# LED_DISPLAY_SCHE.net
KiCad netlist of a schematic drawn in Altium Designer
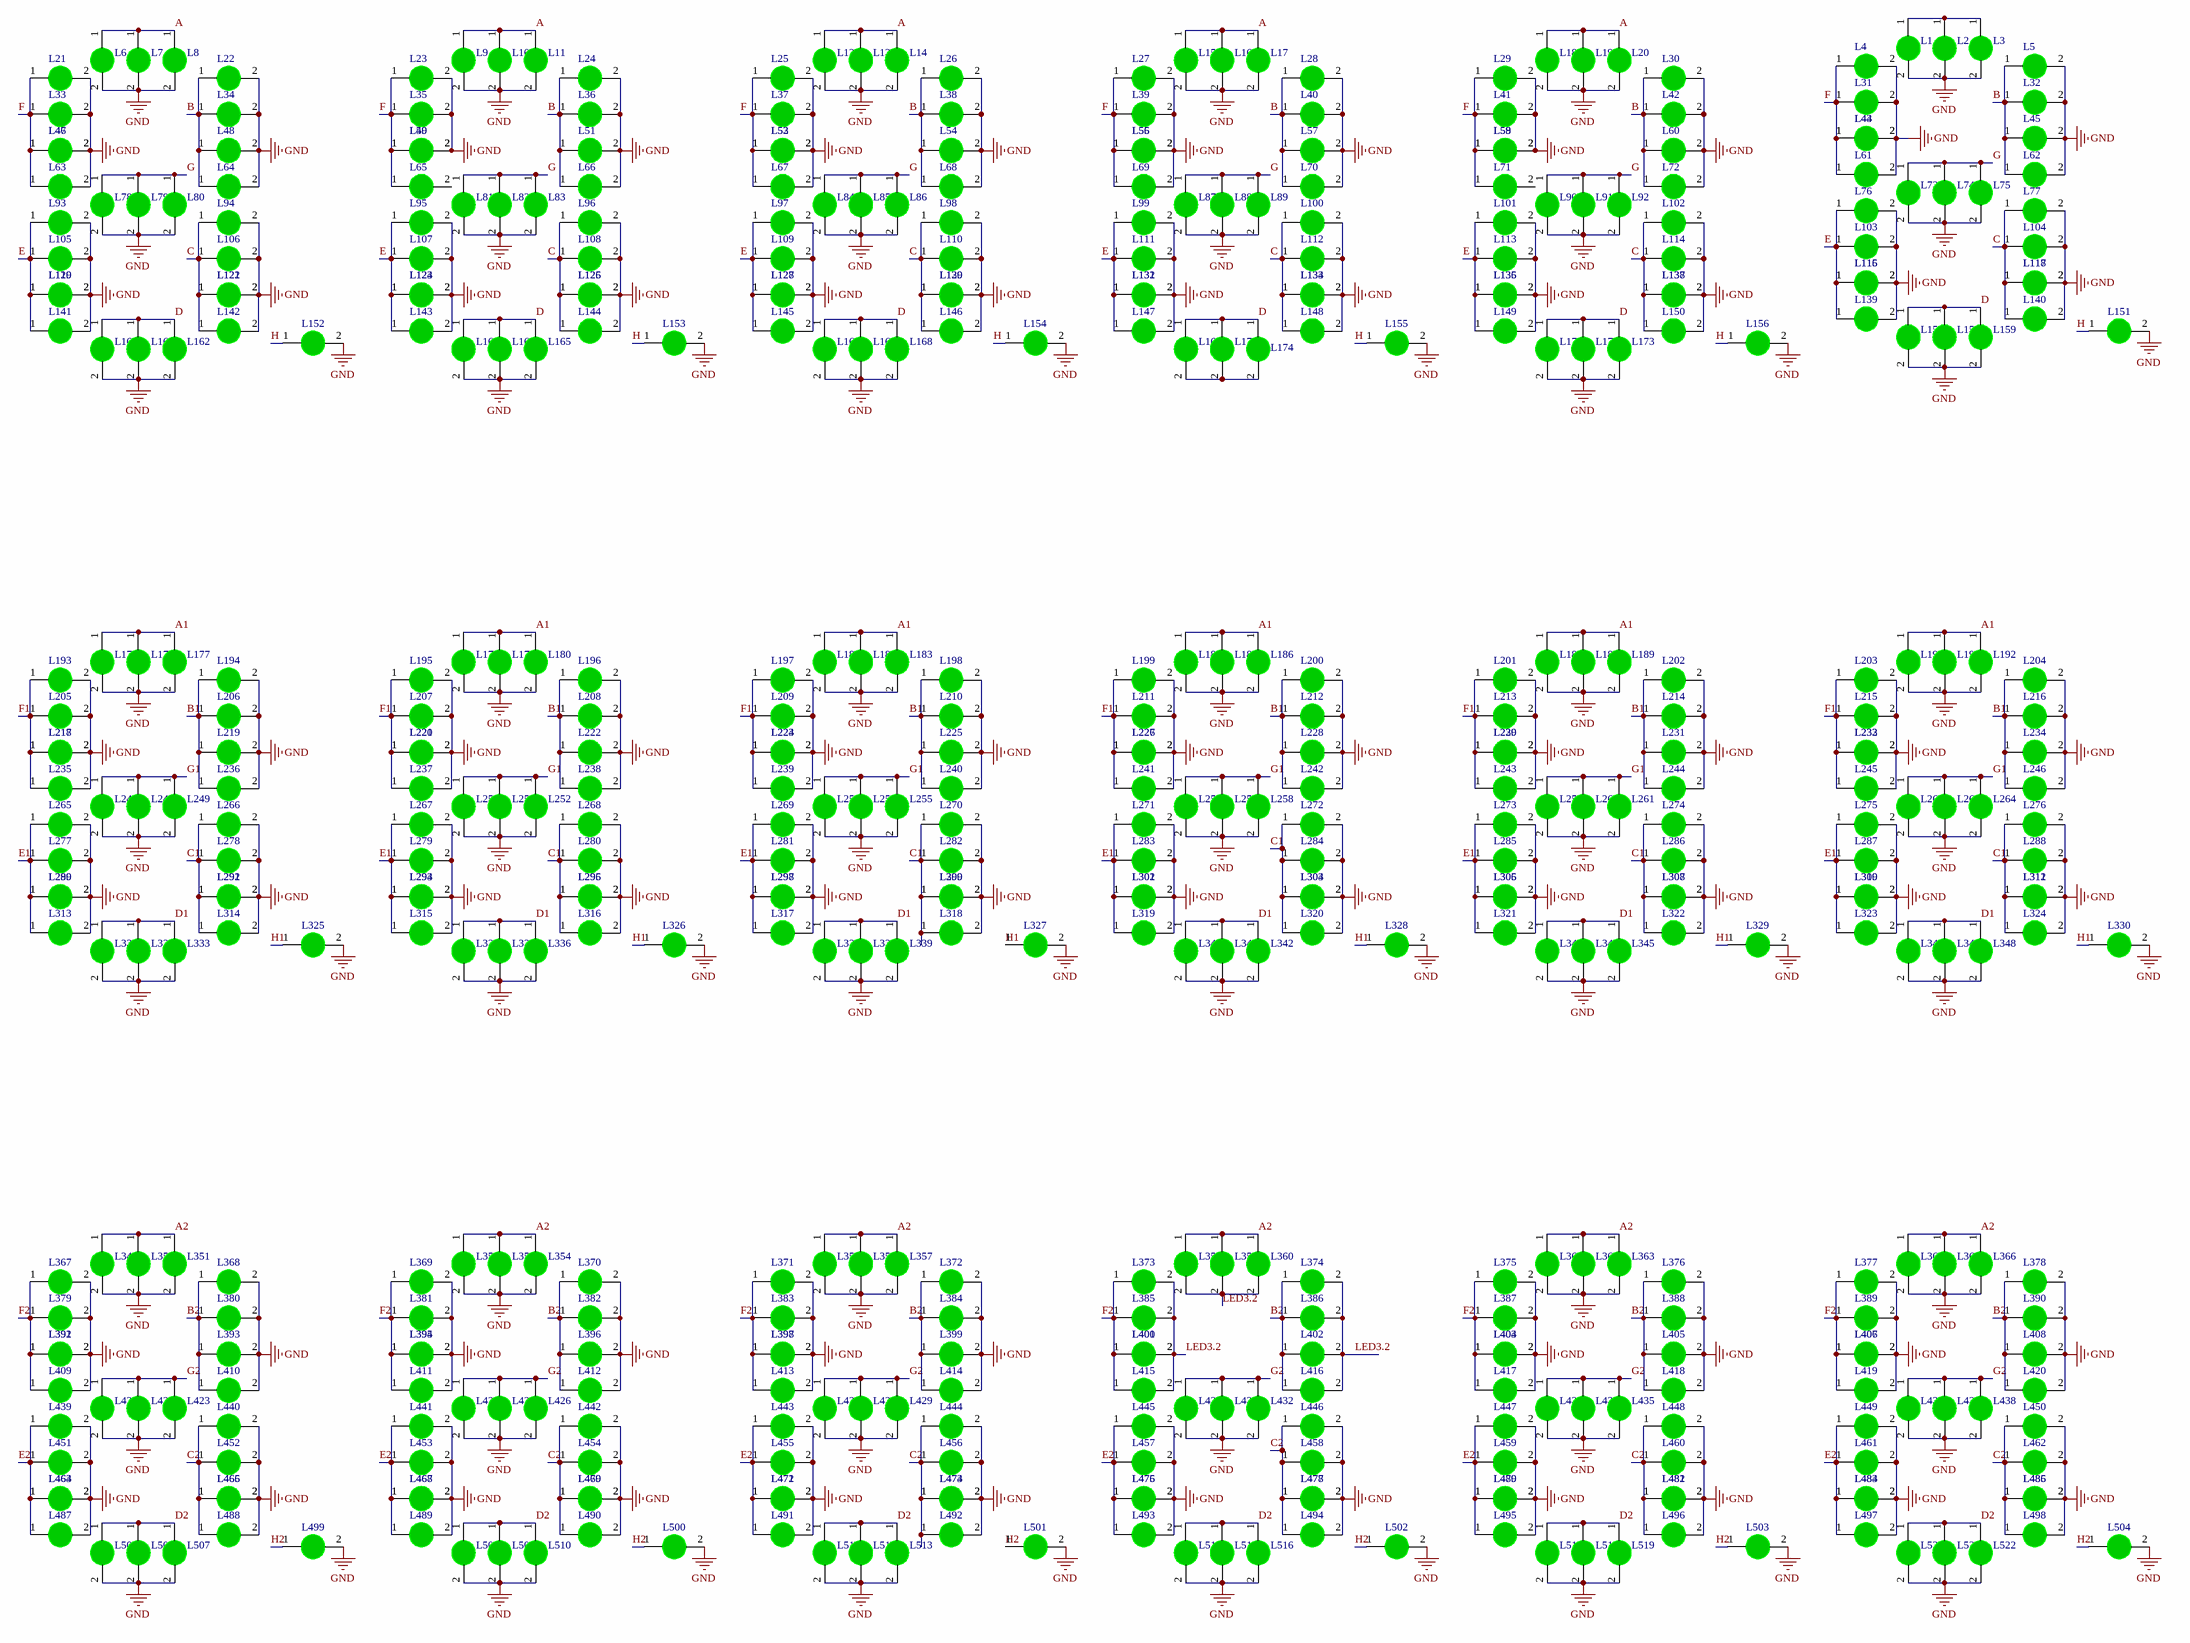
[diagram p0: LED_DISPLAY_SCHE.SchDoc]

(export (version "E")
  (design (tool "Eeschema 10.0.6"))
  (components
    (comp (ref "L1")
      (value "LED 3528")
      (footprint "LED-3528-GREEN")
      (description "Dán")
      (libsource (lib "Altium_Lib_by_KhueNguyenCreator") (part "LED 3528 Xanh La"))
    )
    (comp (ref "L2")
      (value "LED 3528")
      (footprint "LED-3528-GREEN")
      (description "Dán")
      (libsource (lib "Altium_Lib_by_KhueNguyenCreator") (part "LED 3528 Xanh La"))
    )
    (comp (ref "L3")
      (value "LED 3528")
      (footprint "LED-3528-GREEN")
      (description "Dán")
      (libsource (lib "Altium_Lib_by_KhueNguyenCreator") (part "LED 3528 Xanh La"))
    )
    (comp (ref "L4")
      (value "LED 3528")
      (footprint "LED-3528-GREEN")
      (description "Dán")
      (libsource (lib "Altium_Lib_by_KhueNguyenCreator") (part "LED 3528 Xanh La"))
    )
    (comp (ref "L5")
      (value "LED 3528")
      (footprint "LED-3528-GREEN")
      (description "Dán")
      (libsource (lib "Altium_Lib_by_KhueNguyenCreator") (part "LED 3528 Xanh La"))
    )
    (comp (ref "L6")
      (value "LED 3528")
      (footprint "LED-3528-GREEN")
      (description "Dán")
      (libsource (lib "Altium_Lib_by_KhueNguyenCreator") (part "LED 3528 Xanh La"))
    )
    (comp (ref "L7")
      (value "LED 3528")
      (footprint "LED-3528-GREEN")
      (description "Dán")
      (libsource (lib "Altium_Lib_by_KhueNguyenCreator") (part "LED 3528 Xanh La"))
    )
    (comp (ref "L8")
      (value "LED 3528")
      (footprint "LED-3528-GREEN")
      (description "Dán")
      (libsource (lib "Altium_Lib_by_KhueNguyenCreator") (part "LED 3528 Xanh La"))
    )
    (comp (ref "L9")
      (value "LED 3528")
      (footprint "LED-3528-GREEN")
      (description "Dán")
      (libsource (lib "Altium_Lib_by_KhueNguyenCreator") (part "LED 3528 Xanh La"))
    )
    (comp (ref "L10")
      (value "LED 3528")
      (footprint "LED-3528-GREEN")
      (description "Dán")
      (libsource (lib "Altium_Lib_by_KhueNguyenCreator") (part "LED 3528 Xanh La"))
    )
    (comp (ref "L11")
      (value "LED 3528")
      (footprint "LED-3528-GREEN")
      (description "Dán")
      (libsource (lib "Altium_Lib_by_KhueNguyenCreator") (part "LED 3528 Xanh La"))
    )
    (comp (ref "L12")
      (value "LED 3528")
      (footprint "LED-3528-GREEN")
      (description "Dán")
      (libsource (lib "Altium_Lib_by_KhueNguyenCreator") (part "LED 3528 Xanh La"))
    )
    (comp (ref "L13")
      (value "LED 3528")
      (footprint "LED-3528-GREEN")
      (description "Dán")
      (libsource (lib "Altium_Lib_by_KhueNguyenCreator") (part "LED 3528 Xanh La"))
    )
    (comp (ref "L14")
      (value "LED 3528")
      (footprint "LED-3528-GREEN")
      (description "Dán")
      (libsource (lib "Altium_Lib_by_KhueNguyenCreator") (part "LED 3528 Xanh La"))
    )
    (comp (ref "L15")
      (value "LED 3528")
      (footprint "LED-3528-GREEN")
      (description "Dán")
      (libsource (lib "Altium_Lib_by_KhueNguyenCreator") (part "LED 3528 Xanh La"))
    )
    (comp (ref "L16")
      (value "LED 3528")
      (footprint "LED-3528-GREEN")
      (description "Dán")
      (libsource (lib "Altium_Lib_by_KhueNguyenCreator") (part "LED 3528 Xanh La"))
    )
    (comp (ref "L17")
      (value "LED 3528")
      (footprint "LED-3528-GREEN")
      (description "Dán")
      (libsource (lib "Altium_Lib_by_KhueNguyenCreator") (part "LED 3528 Xanh La"))
    )
    (comp (ref "L18")
      (value "LED 3528")
      (footprint "LED-3528-GREEN")
      (description "Dán")
      (libsource (lib "Altium_Lib_by_KhueNguyenCreator") (part "LED 3528 Xanh La"))
    )
    (comp (ref "L19")
      (value "LED 3528")
      (footprint "LED-3528-GREEN")
      (description "Dán")
      (libsource (lib "Altium_Lib_by_KhueNguyenCreator") (part "LED 3528 Xanh La"))
    )
    (comp (ref "L20")
      (value "LED 3528")
      (footprint "LED-3528-GREEN")
      (description "Dán")
      (libsource (lib "Altium_Lib_by_KhueNguyenCreator") (part "LED 3528 Xanh La"))
    )
    (comp (ref "L21")
      (value "LED 3528")
      (footprint "LED-3528-GREEN")
      (description "Dán")
      (libsource (lib "Altium_Lib_by_KhueNguyenCreator") (part "LED 3528 Xanh La"))
    )
    (comp (ref "L22")
      (value "LED 3528")
      (footprint "LED-3528-GREEN")
      (description "Dán")
      (libsource (lib "Altium_Lib_by_KhueNguyenCreator") (part "LED 3528 Xanh La"))
    )
    (comp (ref "L23")
      (value "LED 3528")
      (footprint "LED-3528-GREEN")
      (description "Dán")
      (libsource (lib "Altium_Lib_by_KhueNguyenCreator") (part "LED 3528 Xanh La"))
    )
    (comp (ref "L24")
      (value "LED 3528")
      (footprint "LED-3528-GREEN")
      (description "Dán")
      (libsource (lib "Altium_Lib_by_KhueNguyenCreator") (part "LED 3528 Xanh La"))
    )
    (comp (ref "L25")
      (value "LED 3528")
      (footprint "LED-3528-GREEN")
      (description "Dán")
      (libsource (lib "Altium_Lib_by_KhueNguyenCreator") (part "LED 3528 Xanh La"))
    )
    (comp (ref "L26")
      (value "LED 3528")
      (footprint "LED-3528-GREEN")
      (description "Dán")
      (libsource (lib "Altium_Lib_by_KhueNguyenCreator") (part "LED 3528 Xanh La"))
    )
    (comp (ref "L27")
      (value "LED 3528")
      (footprint "LED-3528-GREEN")
      (description "Dán")
      (libsource (lib "Altium_Lib_by_KhueNguyenCreator") (part "LED 3528 Xanh La"))
    )
    (comp (ref "L28")
      (value "LED 3528")
      (footprint "LED-3528-GREEN")
      (description "Dán")
      (libsource (lib "Altium_Lib_by_KhueNguyenCreator") (part "LED 3528 Xanh La"))
    )
    (comp (ref "L29")
      (value "LED 3528")
      (footprint "LED-3528-GREEN")
      (description "Dán")
      (libsource (lib "Altium_Lib_by_KhueNguyenCreator") (part "LED 3528 Xanh La"))
    )
    (comp (ref "L30")
      (value "LED 3528")
      (footprint "LED-3528-GREEN")
      (description "Dán")
      (libsource (lib "Altium_Lib_by_KhueNguyenCreator") (part "LED 3528 Xanh La"))
    )
    (comp (ref "L31")
      (value "LED 3528")
      (footprint "LED-3528-GREEN")
      (description "Dán")
      (libsource (lib "Altium_Lib_by_KhueNguyenCreator") (part "LED 3528 Xanh La"))
    )
    (comp (ref "L32")
      (value "LED 3528")
      (footprint "LED-3528-GREEN")
      (description "Dán")
      (libsource (lib "Altium_Lib_by_KhueNguyenCreator") (part "LED 3528 Xanh La"))
    )
    (comp (ref "L33")
      (value "LED 3528")
      (footprint "LED-3528-GREEN")
      (description "Dán")
      (libsource (lib "Altium_Lib_by_KhueNguyenCreator") (part "LED 3528 Xanh La"))
    )
    (comp (ref "L34")
      (value "LED 3528")
      (footprint "LED-3528-GREEN")
      (description "Dán")
      (libsource (lib "Altium_Lib_by_KhueNguyenCreator") (part "LED 3528 Xanh La"))
    )
    (comp (ref "L35")
      (value "LED 3528")
      (footprint "LED-3528-GREEN")
      (description "Dán")
      (libsource (lib "Altium_Lib_by_KhueNguyenCreator") (part "LED 3528 Xanh La"))
    )
    (comp (ref "L36")
      (value "LED 3528")
      (footprint "LED-3528-GREEN")
      (description "Dán")
      (libsource (lib "Altium_Lib_by_KhueNguyenCreator") (part "LED 3528 Xanh La"))
    )
    (comp (ref "L37")
      (value "LED 3528")
      (footprint "LED-3528-GREEN")
      (description "Dán")
      (libsource (lib "Altium_Lib_by_KhueNguyenCreator") (part "LED 3528 Xanh La"))
    )
    (comp (ref "L38")
      (value "LED 3528")
      (footprint "LED-3528-GREEN")
      (description "Dán")
      (libsource (lib "Altium_Lib_by_KhueNguyenCreator") (part "LED 3528 Xanh La"))
    )
    (comp (ref "L39")
      (value "LED 3528")
      (footprint "LED-3528-GREEN")
      (description "Dán")
      (libsource (lib "Altium_Lib_by_KhueNguyenCreator") (part "LED 3528 Xanh La"))
    )
    (comp (ref "L40")
      (value "LED 3528")
      (footprint "LED-3528-GREEN")
      (description "Dán")
      (libsource (lib "Altium_Lib_by_KhueNguyenCreator") (part "LED 3528 Xanh La"))
    )
    (comp (ref "L41")
      (value "LED 3528")
      (footprint "LED-3528-GREEN")
      (description "Dán")
      (libsource (lib "Altium_Lib_by_KhueNguyenCreator") (part "LED 3528 Xanh La"))
    )
    (comp (ref "L42")
      (value "LED 3528")
      (footprint "LED-3528-GREEN")
      (description "Dán")
      (libsource (lib "Altium_Lib_by_KhueNguyenCreator") (part "LED 3528 Xanh La"))
    )
    (comp (ref "L43")
      (value "LED 3528")
      (footprint "LED-3528-GREEN")
      (description "Dán")
      (libsource (lib "Altium_Lib_by_KhueNguyenCreator") (part "LED 3528 Xanh La"))
    )
    (comp (ref "L44")
      (value "LED 3528")
      (footprint "LED-3528-GREEN")
      (description "Dán")
      (libsource (lib "Altium_Lib_by_KhueNguyenCreator") (part "LED 3528 Xanh La"))
    )
    (comp (ref "L45")
      (value "LED 3528")
      (footprint "LED-3528-GREEN")
      (description "Dán")
      (libsource (lib "Altium_Lib_by_KhueNguyenCreator") (part "LED 3528 Xanh La"))
    )
    (comp (ref "L46")
      (value "LED 3528")
      (footprint "LED-3528-GREEN")
      (description "Dán")
      (libsource (lib "Altium_Lib_by_KhueNguyenCreator") (part "LED 3528 Xanh La"))
    )
    (comp (ref "L47")
      (value "LED 3528")
      (footprint "LED-3528-GREEN")
      (description "Dán")
      (libsource (lib "Altium_Lib_by_KhueNguyenCreator") (part "LED 3528 Xanh La"))
    )
    (comp (ref "L48")
      (value "LED 3528")
      (footprint "LED-3528-GREEN")
      (description "Dán")
      (libsource (lib "Altium_Lib_by_KhueNguyenCreator") (part "LED 3528 Xanh La"))
    )
    (comp (ref "L49")
      (value "LED 3528")
      (footprint "LED-3528-GREEN")
      (description "Dán")
      (libsource (lib "Altium_Lib_by_KhueNguyenCreator") (part "LED 3528 Xanh La"))
    )
    (comp (ref "L50")
      (value "LED 3528")
      (footprint "LED-3528-GREEN")
      (description "Dán")
      (libsource (lib "Altium_Lib_by_KhueNguyenCreator") (part "LED 3528 Xanh La"))
    )
    (comp (ref "L51")
      (value "LED 3528")
      (footprint "LED-3528-GREEN")
      (description "Dán")
      (libsource (lib "Altium_Lib_by_KhueNguyenCreator") (part "LED 3528 Xanh La"))
    )
    (comp (ref "L52")
      (value "LED 3528")
      (footprint "LED-3528-GREEN")
      (description "Dán")
      (libsource (lib "Altium_Lib_by_KhueNguyenCreator") (part "LED 3528 Xanh La"))
    )
    (comp (ref "L53")
      (value "LED 3528")
      (footprint "LED-3528-GREEN")
      (description "Dán")
      (libsource (lib "Altium_Lib_by_KhueNguyenCreator") (part "LED 3528 Xanh La"))
    )
    (comp (ref "L54")
      (value "LED 3528")
      (footprint "LED-3528-GREEN")
      (description "Dán")
      (libsource (lib "Altium_Lib_by_KhueNguyenCreator") (part "LED 3528 Xanh La"))
    )
    (comp (ref "L55")
      (value "LED 3528")
      (footprint "LED-3528-GREEN")
      (description "Dán")
      (libsource (lib "Altium_Lib_by_KhueNguyenCreator") (part "LED 3528 Xanh La"))
    )
    (comp (ref "L56")
      (value "LED 3528")
      (footprint "LED-3528-GREEN")
      (description "Dán")
      (libsource (lib "Altium_Lib_by_KhueNguyenCreator") (part "LED 3528 Xanh La"))
    )
    (comp (ref "L57")
      (value "LED 3528")
      (footprint "LED-3528-GREEN")
      (description "Dán")
      (libsource (lib "Altium_Lib_by_KhueNguyenCreator") (part "LED 3528 Xanh La"))
    )
    (comp (ref "L58")
      (value "LED 3528")
      (footprint "LED-3528-GREEN")
      (description "Dán")
      (libsource (lib "Altium_Lib_by_KhueNguyenCreator") (part "LED 3528 Xanh La"))
    )
    (comp (ref "L59")
      (value "LED 3528")
      (footprint "LED-3528-GREEN")
      (description "Dán")
      (libsource (lib "Altium_Lib_by_KhueNguyenCreator") (part "LED 3528 Xanh La"))
    )
    (comp (ref "L60")
      (value "LED 3528")
      (footprint "LED-3528-GREEN")
      (description "Dán")
      (libsource (lib "Altium_Lib_by_KhueNguyenCreator") (part "LED 3528 Xanh La"))
    )
    (comp (ref "L61")
      (value "LED 3528")
      (footprint "LED-3528-GREEN")
      (description "Dán")
      (libsource (lib "Altium_Lib_by_KhueNguyenCreator") (part "LED 3528 Xanh La"))
    )
    (comp (ref "L62")
      (value "LED 3528")
      (footprint "LED-3528-GREEN")
      (description "Dán")
      (libsource (lib "Altium_Lib_by_KhueNguyenCreator") (part "LED 3528 Xanh La"))
    )
    (comp (ref "L63")
      (value "LED 3528")
      (footprint "LED-3528-GREEN")
      (description "Dán")
      (libsource (lib "Altium_Lib_by_KhueNguyenCreator") (part "LED 3528 Xanh La"))
    )
    (comp (ref "L64")
      (value "LED 3528")
      (footprint "LED-3528-GREEN")
      (description "Dán")
      (libsource (lib "Altium_Lib_by_KhueNguyenCreator") (part "LED 3528 Xanh La"))
    )
    (comp (ref "L65")
      (value "LED 3528")
      (footprint "LED-3528-GREEN")
      (description "Dán")
      (libsource (lib "Altium_Lib_by_KhueNguyenCreator") (part "LED 3528 Xanh La"))
    )
    (comp (ref "L66")
      (value "LED 3528")
      (footprint "LED-3528-GREEN")
      (description "Dán")
      (libsource (lib "Altium_Lib_by_KhueNguyenCreator") (part "LED 3528 Xanh La"))
    )
    (comp (ref "L67")
      (value "LED 3528")
      (footprint "LED-3528-GREEN")
      (description "Dán")
      (libsource (lib "Altium_Lib_by_KhueNguyenCreator") (part "LED 3528 Xanh La"))
    )
    (comp (ref "L68")
      (value "LED 3528")
      (footprint "LED-3528-GREEN")
      (description "Dán")
      (libsource (lib "Altium_Lib_by_KhueNguyenCreator") (part "LED 3528 Xanh La"))
    )
    (comp (ref "L69")
      (value "LED 3528")
      (footprint "LED-3528-GREEN")
      (description "Dán")
      (libsource (lib "Altium_Lib_by_KhueNguyenCreator") (part "LED 3528 Xanh La"))
    )
    (comp (ref "L70")
      (value "LED 3528")
      (footprint "LED-3528-GREEN")
      (description "Dán")
      (libsource (lib "Altium_Lib_by_KhueNguyenCreator") (part "LED 3528 Xanh La"))
    )
    (comp (ref "L71")
      (value "LED 3528")
      (footprint "LED-3528-GREEN")
      (description "Dán")
      (libsource (lib "Altium_Lib_by_KhueNguyenCreator") (part "LED 3528 Xanh La"))
    )
    (comp (ref "L72")
      (value "LED 3528")
      (footprint "LED-3528-GREEN")
      (description "Dán")
      (libsource (lib "Altium_Lib_by_KhueNguyenCreator") (part "LED 3528 Xanh La"))
    )
    (comp (ref "L73")
      (value "LED 3528")
      (footprint "LED-3528-GREEN")
      (description "Dán")
      (libsource (lib "Altium_Lib_by_KhueNguyenCreator") (part "LED 3528 Xanh La"))
    )
    (comp (ref "L74")
      (value "LED 3528")
      (footprint "LED-3528-GREEN")
      (description "Dán")
      (libsource (lib "Altium_Lib_by_KhueNguyenCreator") (part "LED 3528 Xanh La"))
    )
    (comp (ref "L75")
      (value "LED 3528")
      (footprint "LED-3528-GREEN")
      (description "Dán")
      (libsource (lib "Altium_Lib_by_KhueNguyenCreator") (part "LED 3528 Xanh La"))
    )
    (comp (ref "L76")
      (value "LED 3528")
      (footprint "LED-3528-GREEN")
      (description "Dán")
      (libsource (lib "Altium_Lib_by_KhueNguyenCreator") (part "LED 3528 Xanh La"))
    )
    (comp (ref "L77")
      (value "LED 3528")
      (footprint "LED-3528-GREEN")
      (description "Dán")
      (libsource (lib "Altium_Lib_by_KhueNguyenCreator") (part "LED 3528 Xanh La"))
    )
    (comp (ref "L78")
      (value "LED 3528")
      (footprint "LED-3528-GREEN")
      (description "Dán")
      (libsource (lib "Altium_Lib_by_KhueNguyenCreator") (part "LED 3528 Xanh La"))
    )
    (comp (ref "L79")
      (value "LED 3528")
      (footprint "LED-3528-GREEN")
      (description "Dán")
      (libsource (lib "Altium_Lib_by_KhueNguyenCreator") (part "LED 3528 Xanh La"))
    )
    (comp (ref "L80")
      (value "LED 3528")
      (footprint "LED-3528-GREEN")
      (description "Dán")
      (libsource (lib "Altium_Lib_by_KhueNguyenCreator") (part "LED 3528 Xanh La"))
    )
    (comp (ref "L81")
      (value "LED 3528")
      (footprint "LED-3528-GREEN")
      (description "Dán")
      (libsource (lib "Altium_Lib_by_KhueNguyenCreator") (part "LED 3528 Xanh La"))
    )
    (comp (ref "L82")
      (value "LED 3528")
      (footprint "LED-3528-GREEN")
      (description "Dán")
      (libsource (lib "Altium_Lib_by_KhueNguyenCreator") (part "LED 3528 Xanh La"))
    )
    (comp (ref "L83")
      (value "LED 3528")
      (footprint "LED-3528-GREEN")
      (description "Dán")
      (libsource (lib "Altium_Lib_by_KhueNguyenCreator") (part "LED 3528 Xanh La"))
    )
    (comp (ref "L84")
      (value "LED 3528")
      (footprint "LED-3528-GREEN")
      (description "Dán")
      (libsource (lib "Altium_Lib_by_KhueNguyenCreator") (part "LED 3528 Xanh La"))
    )
    (comp (ref "L85")
      (value "LED 3528")
      (footprint "LED-3528-GREEN")
      (description "Dán")
      (libsource (lib "Altium_Lib_by_KhueNguyenCreator") (part "LED 3528 Xanh La"))
    )
    (comp (ref "L86")
      (value "LED 3528")
      (footprint "LED-3528-GREEN")
      (description "Dán")
      (libsource (lib "Altium_Lib_by_KhueNguyenCreator") (part "LED 3528 Xanh La"))
    )
    (comp (ref "L87")
      (value "LED 3528")
      (footprint "LED-3528-GREEN")
      (description "Dán")
      (libsource (lib "Altium_Lib_by_KhueNguyenCreator") (part "LED 3528 Xanh La"))
    )
    (comp (ref "L88")
      (value "LED 3528")
      (footprint "LED-3528-GREEN")
      (description "Dán")
      (libsource (lib "Altium_Lib_by_KhueNguyenCreator") (part "LED 3528 Xanh La"))
    )
    (comp (ref "L89")
      (value "LED 3528")
      (footprint "LED-3528-GREEN")
      (description "Dán")
      (libsource (lib "Altium_Lib_by_KhueNguyenCreator") (part "LED 3528 Xanh La"))
    )
    (comp (ref "L90")
      (value "LED 3528")
      (footprint "LED-3528-GREEN")
      (description "Dán")
      (libsource (lib "Altium_Lib_by_KhueNguyenCreator") (part "LED 3528 Xanh La"))
    )
    (comp (ref "L91")
      (value "LED 3528")
      (footprint "LED-3528-GREEN")
      (description "Dán")
      (libsource (lib "Altium_Lib_by_KhueNguyenCreator") (part "LED 3528 Xanh La"))
    )
    (comp (ref "L92")
      (value "LED 3528")
      (footprint "LED-3528-GREEN")
      (description "Dán")
      (libsource (lib "Altium_Lib_by_KhueNguyenCreator") (part "LED 3528 Xanh La"))
    )
    (comp (ref "L93")
      (value "LED 3528")
      (footprint "LED-3528-GREEN")
      (description "Dán")
      (libsource (lib "Altium_Lib_by_KhueNguyenCreator") (part "LED 3528 Xanh La"))
    )
    (comp (ref "L94")
      (value "LED 3528")
      (footprint "LED-3528-GREEN")
      (description "Dán")
      (libsource (lib "Altium_Lib_by_KhueNguyenCreator") (part "LED 3528 Xanh La"))
    )
    (comp (ref "L95")
      (value "LED 3528")
      (footprint "LED-3528-GREEN")
      (description "Dán")
      (libsource (lib "Altium_Lib_by_KhueNguyenCreator") (part "LED 3528 Xanh La"))
    )
    (comp (ref "L96")
      (value "LED 3528")
      (footprint "LED-3528-GREEN")
      (description "Dán")
      (libsource (lib "Altium_Lib_by_KhueNguyenCreator") (part "LED 3528 Xanh La"))
    )
    (comp (ref "L97")
      (value "LED 3528")
      (footprint "LED-3528-GREEN")
      (description "Dán")
      (libsource (lib "Altium_Lib_by_KhueNguyenCreator") (part "LED 3528 Xanh La"))
    )
    (comp (ref "L98")
      (value "LED 3528")
      (footprint "LED-3528-GREEN")
      (description "Dán")
      (libsource (lib "Altium_Lib_by_KhueNguyenCreator") (part "LED 3528 Xanh La"))
    )
    (comp (ref "L99")
      (value "LED 3528")
      (footprint "LED-3528-GREEN")
      (description "Dán")
      (libsource (lib "Altium_Lib_by_KhueNguyenCreator") (part "LED 3528 Xanh La"))
    )
    (comp (ref "L100")
      (value "LED 3528")
      (footprint "LED-3528-GREEN")
      (description "Dán")
      (libsource (lib "Altium_Lib_by_KhueNguyenCreator") (part "LED 3528 Xanh La"))
    )
    (comp (ref "L101")
      (value "LED 3528")
      (footprint "LED-3528-GREEN")
      (description "Dán")
      (libsource (lib "Altium_Lib_by_KhueNguyenCreator") (part "LED 3528 Xanh La"))
    )
    (comp (ref "L102")
      (value "LED 3528")
      (footprint "LED-3528-GREEN")
      (description "Dán")
      (libsource (lib "Altium_Lib_by_KhueNguyenCreator") (part "LED 3528 Xanh La"))
    )
    (comp (ref "L103")
      (value "LED 3528")
      (footprint "LED-3528-GREEN")
      (description "Dán")
      (libsource (lib "Altium_Lib_by_KhueNguyenCreator") (part "LED 3528 Xanh La"))
    )
    (comp (ref "L104")
      (value "LED 3528")
      (footprint "LED-3528-GREEN")
      (description "Dán")
      (libsource (lib "Altium_Lib_by_KhueNguyenCreator") (part "LED 3528 Xanh La"))
    )
    (comp (ref "L105")
      (value "LED 3528")
      (footprint "LED-3528-GREEN")
      (description "Dán")
      (libsource (lib "Altium_Lib_by_KhueNguyenCreator") (part "LED 3528 Xanh La"))
    )
    (comp (ref "L106")
      (value "LED 3528")
      (footprint "LED-3528-GREEN")
      (description "Dán")
      (libsource (lib "Altium_Lib_by_KhueNguyenCreator") (part "LED 3528 Xanh La"))
    )
    (comp (ref "L107")
      (value "LED 3528")
      (footprint "LED-3528-GREEN")
      (description "Dán")
      (libsource (lib "Altium_Lib_by_KhueNguyenCreator") (part "LED 3528 Xanh La"))
    )
    (comp (ref "L108")
      (value "LED 3528")
      (footprint "LED-3528-GREEN")
      (description "Dán")
      (libsource (lib "Altium_Lib_by_KhueNguyenCreator") (part "LED 3528 Xanh La"))
    )
    (comp (ref "L109")
      (value "LED 3528")
      (footprint "LED-3528-GREEN")
      (description "Dán")
      (libsource (lib "Altium_Lib_by_KhueNguyenCreator") (part "LED 3528 Xanh La"))
    )
    (comp (ref "L110")
      (value "LED 3528")
      (footprint "LED-3528-GREEN")
      (description "Dán")
      (libsource (lib "Altium_Lib_by_KhueNguyenCreator") (part "LED 3528 Xanh La"))
    )
    (comp (ref "L111")
      (value "LED 3528")
      (footprint "LED-3528-GREEN")
      (description "Dán")
      (libsource (lib "Altium_Lib_by_KhueNguyenCreator") (part "LED 3528 Xanh La"))
    )
    (comp (ref "L112")
      (value "LED 3528")
      (footprint "LED-3528-GREEN")
      (description "Dán")
      (libsource (lib "Altium_Lib_by_KhueNguyenCreator") (part "LED 3528 Xanh La"))
    )
    (comp (ref "L113")
      (value "LED 3528")
      (footprint "LED-3528-GREEN")
      (description "Dán")
      (libsource (lib "Altium_Lib_by_KhueNguyenCreator") (part "LED 3528 Xanh La"))
    )
    (comp (ref "L114")
      (value "LED 3528")
      (footprint "LED-3528-GREEN")
      (description "Dán")
      (libsource (lib "Altium_Lib_by_KhueNguyenCreator") (part "LED 3528 Xanh La"))
    )
    (comp (ref "L115")
      (value "LED 3528")
      (footprint "LED-3528-GREEN")
      (description "Dán")
      (libsource (lib "Altium_Lib_by_KhueNguyenCreator") (part "LED 3528 Xanh La"))
    )
    (comp (ref "L116")
      (value "LED 3528")
      (footprint "LED-3528-GREEN")
      (description "Dán")
      (libsource (lib "Altium_Lib_by_KhueNguyenCreator") (part "LED 3528 Xanh La"))
    )
    (comp (ref "L117")
      (value "LED 3528")
      (footprint "LED-3528-GREEN")
      (description "Dán")
      (libsource (lib "Altium_Lib_by_KhueNguyenCreator") (part "LED 3528 Xanh La"))
    )
    (comp (ref "L118")
      (value "LED 3528")
      (footprint "LED-3528-GREEN")
      (description "Dán")
      (libsource (lib "Altium_Lib_by_KhueNguyenCreator") (part "LED 3528 Xanh La"))
    )
    (comp (ref "L119")
      (value "LED 3528")
      (footprint "LED-3528-GREEN")
      (description "Dán")
      (libsource (lib "Altium_Lib_by_KhueNguyenCreator") (part "LED 3528 Xanh La"))
    )
    (comp (ref "L120")
      (value "LED 3528")
      (footprint "LED-3528-GREEN")
      (description "Dán")
      (libsource (lib "Altium_Lib_by_KhueNguyenCreator") (part "LED 3528 Xanh La"))
    )
    (comp (ref "L121")
      (value "LED 3528")
      (footprint "LED-3528-GREEN")
      (description "Dán")
      (libsource (lib "Altium_Lib_by_KhueNguyenCreator") (part "LED 3528 Xanh La"))
    )
    (comp (ref "L122")
      (value "LED 3528")
      (footprint "LED-3528-GREEN")
      (description "Dán")
      (libsource (lib "Altium_Lib_by_KhueNguyenCreator") (part "LED 3528 Xanh La"))
    )
    (comp (ref "L123")
      (value "LED 3528")
      (footprint "LED-3528-GREEN")
      (description "Dán")
      (libsource (lib "Altium_Lib_by_KhueNguyenCreator") (part "LED 3528 Xanh La"))
    )
    (comp (ref "L124")
      (value "LED 3528")
      (footprint "LED-3528-GREEN")
      (description "Dán")
      (libsource (lib "Altium_Lib_by_KhueNguyenCreator") (part "LED 3528 Xanh La"))
    )
    (comp (ref "L125")
      (value "LED 3528")
      (footprint "LED-3528-GREEN")
      (description "Dán")
      (libsource (lib "Altium_Lib_by_KhueNguyenCreator") (part "LED 3528 Xanh La"))
    )
    (comp (ref "L126")
      (value "LED 3528")
      (footprint "LED-3528-GREEN")
      (description "Dán")
      (libsource (lib "Altium_Lib_by_KhueNguyenCreator") (part "LED 3528 Xanh La"))
    )
    (comp (ref "L127")
      (value "LED 3528")
      (footprint "LED-3528-GREEN")
      (description "Dán")
      (libsource (lib "Altium_Lib_by_KhueNguyenCreator") (part "LED 3528 Xanh La"))
    )
    (comp (ref "L128")
      (value "LED 3528")
      (footprint "LED-3528-GREEN")
      (description "Dán")
      (libsource (lib "Altium_Lib_by_KhueNguyenCreator") (part "LED 3528 Xanh La"))
    )
    (comp (ref "L129")
      (value "LED 3528")
      (footprint "LED-3528-GREEN")
      (description "Dán")
      (libsource (lib "Altium_Lib_by_KhueNguyenCreator") (part "LED 3528 Xanh La"))
    )
    (comp (ref "L130")
      (value "LED 3528")
      (footprint "LED-3528-GREEN")
      (description "Dán")
      (libsource (lib "Altium_Lib_by_KhueNguyenCreator") (part "LED 3528 Xanh La"))
    )
    (comp (ref "L131")
      (value "LED 3528")
      (footprint "LED-3528-GREEN")
      (description "Dán")
      (libsource (lib "Altium_Lib_by_KhueNguyenCreator") (part "LED 3528 Xanh La"))
    )
    (comp (ref "L132")
      (value "LED 3528")
      (footprint "LED-3528-GREEN")
      (description "Dán")
      (libsource (lib "Altium_Lib_by_KhueNguyenCreator") (part "LED 3528 Xanh La"))
    )
    (comp (ref "L133")
      (value "LED 3528")
      (footprint "LED-3528-GREEN")
      (description "Dán")
      (libsource (lib "Altium_Lib_by_KhueNguyenCreator") (part "LED 3528 Xanh La"))
    )
    (comp (ref "L134")
      (value "LED 3528")
      (footprint "LED-3528-GREEN")
      (description "Dán")
      (libsource (lib "Altium_Lib_by_KhueNguyenCreator") (part "LED 3528 Xanh La"))
    )
    (comp (ref "L135")
      (value "LED 3528")
      (footprint "LED-3528-GREEN")
      (description "Dán")
      (libsource (lib "Altium_Lib_by_KhueNguyenCreator") (part "LED 3528 Xanh La"))
    )
    (comp (ref "L136")
      (value "LED 3528")
      (footprint "LED-3528-GREEN")
      (description "Dán")
      (libsource (lib "Altium_Lib_by_KhueNguyenCreator") (part "LED 3528 Xanh La"))
    )
    (comp (ref "L137")
      (value "LED 3528")
      (footprint "LED-3528-GREEN")
      (description "Dán")
      (libsource (lib "Altium_Lib_by_KhueNguyenCreator") (part "LED 3528 Xanh La"))
    )
    (comp (ref "L138")
      (value "LED 3528")
      (footprint "LED-3528-GREEN")
      (description "Dán")
      (libsource (lib "Altium_Lib_by_KhueNguyenCreator") (part "LED 3528 Xanh La"))
    )
    (comp (ref "L139")
      (value "LED 3528")
      (footprint "LED-3528-GREEN")
      (description "Dán")
      (libsource (lib "Altium_Lib_by_KhueNguyenCreator") (part "LED 3528 Xanh La"))
    )
    (comp (ref "L140")
      (value "LED 3528")
      (footprint "LED-3528-GREEN")
      (description "Dán")
      (libsource (lib "Altium_Lib_by_KhueNguyenCreator") (part "LED 3528 Xanh La"))
    )
    (comp (ref "L141")
      (value "LED 3528")
      (footprint "LED-3528-GREEN")
      (description "Dán")
      (libsource (lib "Altium_Lib_by_KhueNguyenCreator") (part "LED 3528 Xanh La"))
    )
    (comp (ref "L142")
      (value "LED 3528")
      (footprint "LED-3528-GREEN")
      (description "Dán")
      (libsource (lib "Altium_Lib_by_KhueNguyenCreator") (part "LED 3528 Xanh La"))
    )
    (comp (ref "L143")
      (value "LED 3528")
      (footprint "LED-3528-GREEN")
      (description "Dán")
      (libsource (lib "Altium_Lib_by_KhueNguyenCreator") (part "LED 3528 Xanh La"))
    )
    (comp (ref "L144")
      (value "LED 3528")
      (footprint "LED-3528-GREEN")
      (description "Dán")
      (libsource (lib "Altium_Lib_by_KhueNguyenCreator") (part "LED 3528 Xanh La"))
    )
    (comp (ref "L145")
      (value "LED 3528")
      (footprint "LED-3528-GREEN")
      (description "Dán")
      (libsource (lib "Altium_Lib_by_KhueNguyenCreator") (part "LED 3528 Xanh La"))
    )
    (comp (ref "L146")
      (value "LED 3528")
      (footprint "LED-3528-GREEN")
      (description "Dán")
      (libsource (lib "Altium_Lib_by_KhueNguyenCreator") (part "LED 3528 Xanh La"))
    )
    (comp (ref "L147")
      (value "LED 3528")
      (footprint "LED-3528-GREEN")
      (description "Dán")
      (libsource (lib "Altium_Lib_by_KhueNguyenCreator") (part "LED 3528 Xanh La"))
    )
    (comp (ref "L148")
      (value "LED 3528")
      (footprint "LED-3528-GREEN")
      (description "Dán")
      (libsource (lib "Altium_Lib_by_KhueNguyenCreator") (part "LED 3528 Xanh La"))
    )
    (comp (ref "L149")
      (value "LED 3528")
      (footprint "LED-3528-GREEN")
      (description "Dán")
      (libsource (lib "Altium_Lib_by_KhueNguyenCreator") (part "LED 3528 Xanh La"))
    )
    (comp (ref "L150")
      (value "LED 3528")
      (footprint "LED-3528-GREEN")
      (description "Dán")
      (libsource (lib "Altium_Lib_by_KhueNguyenCreator") (part "LED 3528 Xanh La"))
    )
    (comp (ref "L151")
      (value "LED 3528")
      (footprint "LED-3528-GREEN")
      (description "Dán")
      (libsource (lib "Altium_Lib_by_KhueNguyenCreator") (part "LED 3528 Xanh La"))
    )
    (comp (ref "L152")
      (value "LED 3528")
      (footprint "LED-3528-GREEN")
      (description "Dán")
      (libsource (lib "Altium_Lib_by_KhueNguyenCreator") (part "LED 3528 Xanh La"))
    )
    (comp (ref "L153")
      (value "LED 3528")
      (footprint "LED-3528-GREEN")
      (description "Dán")
      (libsource (lib "Altium_Lib_by_KhueNguyenCreator") (part "LED 3528 Xanh La"))
    )
    (comp (ref "L154")
      (value "LED 3528")
      (footprint "LED-3528-GREEN")
      (description "Dán")
      (libsource (lib "Altium_Lib_by_KhueNguyenCreator") (part "LED 3528 Xanh La"))
    )
    (comp (ref "L155")
      (value "LED 3528")
      (footprint "LED-3528-GREEN")
      (description "Dán")
      (libsource (lib "Altium_Lib_by_KhueNguyenCreator") (part "LED 3528 Xanh La"))
    )
    (comp (ref "L156")
      (value "LED 3528")
      (footprint "LED-3528-GREEN")
      (description "Dán")
      (libsource (lib "Altium_Lib_by_KhueNguyenCreator") (part "LED 3528 Xanh La"))
    )
    (comp (ref "L157")
      (value "LED 3528")
      (footprint "LED-3528-GREEN")
      (description "Dán")
      (libsource (lib "Altium_Lib_by_KhueNguyenCreator") (part "LED 3528 Xanh La"))
    )
    (comp (ref "L158")
      (value "LED 3528")
      (footprint "LED-3528-GREEN")
      (description "Dán")
      (libsource (lib "Altium_Lib_by_KhueNguyenCreator") (part "LED 3528 Xanh La"))
    )
    (comp (ref "L159")
      (value "LED 3528")
      (footprint "LED-3528-GREEN")
      (description "Dán")
      (libsource (lib "Altium_Lib_by_KhueNguyenCreator") (part "LED 3528 Xanh La"))
    )
    (comp (ref "L160")
      (value "LED 3528")
      (footprint "LED-3528-GREEN")
      (description "Dán")
      (libsource (lib "Altium_Lib_by_KhueNguyenCreator") (part "LED 3528 Xanh La"))
    )
    (comp (ref "L161")
      (value "LED 3528")
      (footprint "LED-3528-GREEN")
      (description "Dán")
      (libsource (lib "Altium_Lib_by_KhueNguyenCreator") (part "LED 3528 Xanh La"))
    )
    (comp (ref "L162")
      (value "LED 3528")
      (footprint "LED-3528-GREEN")
      (description "Dán")
      (libsource (lib "Altium_Lib_by_KhueNguyenCreator") (part "LED 3528 Xanh La"))
    )
    (comp (ref "L163")
      (value "LED 3528")
      (footprint "LED-3528-GREEN")
      (description "Dán")
      (libsource (lib "Altium_Lib_by_KhueNguyenCreator") (part "LED 3528 Xanh La"))
    )
    (comp (ref "L164")
      (value "LED 3528")
      (footprint "LED-3528-GREEN")
      (description "Dán")
      (libsource (lib "Altium_Lib_by_KhueNguyenCreator") (part "LED 3528 Xanh La"))
    )
    (comp (ref "L165")
      (value "LED 3528")
      (footprint "LED-3528-GREEN")
      (description "Dán")
      (libsource (lib "Altium_Lib_by_KhueNguyenCreator") (part "LED 3528 Xanh La"))
    )
    (comp (ref "L166")
      (value "LED 3528")
      (footprint "LED-3528-GREEN")
      (description "Dán")
      (libsource (lib "Altium_Lib_by_KhueNguyenCreator") (part "LED 3528 Xanh La"))
    )
    (comp (ref "L167")
      (value "LED 3528")
      (footprint "LED-3528-GREEN")
      (description "Dán")
      (libsource (lib "Altium_Lib_by_KhueNguyenCreator") (part "LED 3528 Xanh La"))
    )
    (comp (ref "L168")
      (value "LED 3528")
      (footprint "LED-3528-GREEN")
      (description "Dán")
      (libsource (lib "Altium_Lib_by_KhueNguyenCreator") (part "LED 3528 Xanh La"))
    )
    (comp (ref "L169")
      (value "LED 3528")
      (footprint "LED-3528-GREEN")
      (description "Dán")
      (libsource (lib "Altium_Lib_by_KhueNguyenCreator") (part "LED 3528 Xanh La"))
    )
    (comp (ref "L170")
      (value "LED 3528")
      (footprint "LED-3528-GREEN")
      (description "Dán")
      (libsource (lib "Altium_Lib_by_KhueNguyenCreator") (part "LED 3528 Xanh La"))
    )
    (comp (ref "L171")
      (value "LED 3528")
      (footprint "LED-3528-GREEN")
      (description "Dán")
      (libsource (lib "Altium_Lib_by_KhueNguyenCreator") (part "LED 3528 Xanh La"))
    )
    (comp (ref "L172")
      (value "LED 3528")
      (footprint "LED-3528-GREEN")
      (description "Dán")
      (libsource (lib "Altium_Lib_by_KhueNguyenCreator") (part "LED 3528 Xanh La"))
    )
    (comp (ref "L173")
      (value "LED 3528")
      (footprint "LED-3528-GREEN")
      (description "Dán")
      (libsource (lib "Altium_Lib_by_KhueNguyenCreator") (part "LED 3528 Xanh La"))
    )
    (comp (ref "L174")
      (value "LED 3528")
      (footprint "LED-3528-GREEN")
      (description "Dán")
      (libsource (lib "Altium_Lib_by_KhueNguyenCreator") (part "LED 3528 Xanh La"))
    )
    (comp (ref "L175")
      (value "LED 3528")
      (footprint "LED-3528-GREEN")
      (description "Dán")
      (libsource (lib "Altium_Lib_by_KhueNguyenCreator") (part "LED 3528 Xanh La"))
    )
    (comp (ref "L176")
      (value "LED 3528")
      (footprint "LED-3528-GREEN")
      (description "Dán")
      (libsource (lib "Altium_Lib_by_KhueNguyenCreator") (part "LED 3528 Xanh La"))
    )
    (comp (ref "L177")
      (value "LED 3528")
      (footprint "LED-3528-GREEN")
      (description "Dán")
      (libsource (lib "Altium_Lib_by_KhueNguyenCreator") (part "LED 3528 Xanh La"))
    )
    (comp (ref "L178")
      (value "LED 3528")
      (footprint "LED-3528-GREEN")
      (description "Dán")
      (libsource (lib "Altium_Lib_by_KhueNguyenCreator") (part "LED 3528 Xanh La"))
    )
    (comp (ref "L179")
      (value "LED 3528")
      (footprint "LED-3528-GREEN")
      (description "Dán")
      (libsource (lib "Altium_Lib_by_KhueNguyenCreator") (part "LED 3528 Xanh La"))
    )
    (comp (ref "L180")
      (value "LED 3528")
      (footprint "LED-3528-GREEN")
      (description "Dán")
      (libsource (lib "Altium_Lib_by_KhueNguyenCreator") (part "LED 3528 Xanh La"))
    )
    (comp (ref "L181")
      (value "LED 3528")
      (footprint "LED-3528-GREEN")
      (description "Dán")
      (libsource (lib "Altium_Lib_by_KhueNguyenCreator") (part "LED 3528 Xanh La"))
    )
    (comp (ref "L182")
      (value "LED 3528")
      (footprint "LED-3528-GREEN")
      (description "Dán")
      (libsource (lib "Altium_Lib_by_KhueNguyenCreator") (part "LED 3528 Xanh La"))
    )
    (comp (ref "L183")
      (value "LED 3528")
      (footprint "LED-3528-GREEN")
      (description "Dán")
      (libsource (lib "Altium_Lib_by_KhueNguyenCreator") (part "LED 3528 Xanh La"))
    )
    (comp (ref "L184")
      (value "LED 3528")
      (footprint "LED-3528-GREEN")
      (description "Dán")
      (libsource (lib "Altium_Lib_by_KhueNguyenCreator") (part "LED 3528 Xanh La"))
    )
    (comp (ref "L185")
      (value "LED 3528")
      (footprint "LED-3528-GREEN")
      (description "Dán")
      (libsource (lib "Altium_Lib_by_KhueNguyenCreator") (part "LED 3528 Xanh La"))
    )
    (comp (ref "L186")
      (value "LED 3528")
      (footprint "LED-3528-GREEN")
      (description "Dán")
      (libsource (lib "Altium_Lib_by_KhueNguyenCreator") (part "LED 3528 Xanh La"))
    )
    (comp (ref "L187")
      (value "LED 3528")
      (footprint "LED-3528-GREEN")
      (description "Dán")
      (libsource (lib "Altium_Lib_by_KhueNguyenCreator") (part "LED 3528 Xanh La"))
    )
    (comp (ref "L188")
      (value "LED 3528")
      (footprint "LED-3528-GREEN")
      (description "Dán")
      (libsource (lib "Altium_Lib_by_KhueNguyenCreator") (part "LED 3528 Xanh La"))
    )
    (comp (ref "L189")
      (value "LED 3528")
      (footprint "LED-3528-GREEN")
      (description "Dán")
      (libsource (lib "Altium_Lib_by_KhueNguyenCreator") (part "LED 3528 Xanh La"))
    )
    (comp (ref "L190")
      (value "LED 3528")
      (footprint "LED-3528-GREEN")
      (description "Dán")
      (libsource (lib "Altium_Lib_by_KhueNguyenCreator") (part "LED 3528 Xanh La"))
    )
    (comp (ref "L191")
      (value "LED 3528")
      (footprint "LED-3528-GREEN")
      (description "Dán")
      (libsource (lib "Altium_Lib_by_KhueNguyenCreator") (part "LED 3528 Xanh La"))
    )
    (comp (ref "L192")
      (value "LED 3528")
      (footprint "LED-3528-GREEN")
      (description "Dán")
      (libsource (lib "Altium_Lib_by_KhueNguyenCreator") (part "LED 3528 Xanh La"))
    )
    (comp (ref "L193")
      (value "LED 3528")
      (footprint "LED-3528-GREEN")
      (description "Dán")
      (libsource (lib "Altium_Lib_by_KhueNguyenCreator") (part "LED 3528 Xanh La"))
    )
    (comp (ref "L194")
      (value "LED 3528")
      (footprint "LED-3528-GREEN")
      (description "Dán")
      (libsource (lib "Altium_Lib_by_KhueNguyenCreator") (part "LED 3528 Xanh La"))
    )
    (comp (ref "L195")
      (value "LED 3528")
      (footprint "LED-3528-GREEN")
      (description "Dán")
      (libsource (lib "Altium_Lib_by_KhueNguyenCreator") (part "LED 3528 Xanh La"))
    )
    (comp (ref "L196")
      (value "LED 3528")
      (footprint "LED-3528-GREEN")
      (description "Dán")
      (libsource (lib "Altium_Lib_by_KhueNguyenCreator") (part "LED 3528 Xanh La"))
    )
    (comp (ref "L197")
      (value "LED 3528")
      (footprint "LED-3528-GREEN")
      (description "Dán")
      (libsource (lib "Altium_Lib_by_KhueNguyenCreator") (part "LED 3528 Xanh La"))
    )
    (comp (ref "L198")
      (value "LED 3528")
      (footprint "LED-3528-GREEN")
      (description "Dán")
      (libsource (lib "Altium_Lib_by_KhueNguyenCreator") (part "LED 3528 Xanh La"))
    )
    (comp (ref "L199")
      (value "LED 3528")
      (footprint "LED-3528-GREEN")
      (description "Dán")
      (libsource (lib "Altium_Lib_by_KhueNguyenCreator") (part "LED 3528 Xanh La"))
    )
    (comp (ref "L200")
      (value "LED 3528")
      (footprint "LED-3528-GREEN")
      (description "Dán")
      (libsource (lib "Altium_Lib_by_KhueNguyenCreator") (part "LED 3528 Xanh La"))
    )
    (comp (ref "L201")
      (value "LED 3528")
      (footprint "LED-3528-GREEN")
      (description "Dán")
      (libsource (lib "Altium_Lib_by_KhueNguyenCreator") (part "LED 3528 Xanh La"))
    )
    (comp (ref "L202")
      (value "LED 3528")
      (footprint "LED-3528-GREEN")
      (description "Dán")
      (libsource (lib "Altium_Lib_by_KhueNguyenCreator") (part "LED 3528 Xanh La"))
    )
    (comp (ref "L203")
      (value "LED 3528")
      (footprint "LED-3528-GREEN")
      (description "Dán")
      (libsource (lib "Altium_Lib_by_KhueNguyenCreator") (part "LED 3528 Xanh La"))
    )
    (comp (ref "L204")
      (value "LED 3528")
      (footprint "LED-3528-GREEN")
      (description "Dán")
      (libsource (lib "Altium_Lib_by_KhueNguyenCreator") (part "LED 3528 Xanh La"))
    )
    (comp (ref "L205")
      (value "LED 3528")
      (footprint "LED-3528-GREEN")
      (description "Dán")
      (libsource (lib "Altium_Lib_by_KhueNguyenCreator") (part "LED 3528 Xanh La"))
    )
    (comp (ref "L206")
      (value "LED 3528")
      (footprint "LED-3528-GREEN")
      (description "Dán")
      (libsource (lib "Altium_Lib_by_KhueNguyenCreator") (part "LED 3528 Xanh La"))
    )
    (comp (ref "L207")
      (value "LED 3528")
      (footprint "LED-3528-GREEN")
      (description "Dán")
      (libsource (lib "Altium_Lib_by_KhueNguyenCreator") (part "LED 3528 Xanh La"))
    )
    (comp (ref "L208")
      (value "LED 3528")
      (footprint "LED-3528-GREEN")
      (description "Dán")
      (libsource (lib "Altium_Lib_by_KhueNguyenCreator") (part "LED 3528 Xanh La"))
    )
    (comp (ref "L209")
      (value "LED 3528")
      (footprint "LED-3528-GREEN")
      (description "Dán")
      (libsource (lib "Altium_Lib_by_KhueNguyenCreator") (part "LED 3528 Xanh La"))
    )
    (comp (ref "L210")
      (value "LED 3528")
      (footprint "LED-3528-GREEN")
      (description "Dán")
      (libsource (lib "Altium_Lib_by_KhueNguyenCreator") (part "LED 3528 Xanh La"))
    )
    (comp (ref "L211")
      (value "LED 3528")
      (footprint "LED-3528-GREEN")
      (description "Dán")
      (libsource (lib "Altium_Lib_by_KhueNguyenCreator") (part "LED 3528 Xanh La"))
    )
    (comp (ref "L212")
      (value "LED 3528")
      (footprint "LED-3528-GREEN")
      (description "Dán")
      (libsource (lib "Altium_Lib_by_KhueNguyenCreator") (part "LED 3528 Xanh La"))
    )
    (comp (ref "L213")
      (value "LED 3528")
      (footprint "LED-3528-GREEN")
      (description "Dán")
      (libsource (lib "Altium_Lib_by_KhueNguyenCreator") (part "LED 3528 Xanh La"))
    )
    (comp (ref "L214")
      (value "LED 3528")
      (footprint "LED-3528-GREEN")
      (description "Dán")
      (libsource (lib "Altium_Lib_by_KhueNguyenCreator") (part "LED 3528 Xanh La"))
    )
    (comp (ref "L215")
      (value "LED 3528")
      (footprint "LED-3528-GREEN")
      (description "Dán")
      (libsource (lib "Altium_Lib_by_KhueNguyenCreator") (part "LED 3528 Xanh La"))
    )
    (comp (ref "L216")
      (value "LED 3528")
      (footprint "LED-3528-GREEN")
      (description "Dán")
      (libsource (lib "Altium_Lib_by_KhueNguyenCreator") (part "LED 3528 Xanh La"))
    )
    (comp (ref "L217")
      (value "LED 3528")
      (footprint "LED-3528-GREEN")
      (description "Dán")
      (libsource (lib "Altium_Lib_by_KhueNguyenCreator") (part "LED 3528 Xanh La"))
    )
    (comp (ref "L218")
      (value "LED 3528")
      (footprint "LED-3528-GREEN")
      (description "Dán")
      (libsource (lib "Altium_Lib_by_KhueNguyenCreator") (part "LED 3528 Xanh La"))
    )
    (comp (ref "L219")
      (value "LED 3528")
      (footprint "LED-3528-GREEN")
      (description "Dán")
      (libsource (lib "Altium_Lib_by_KhueNguyenCreator") (part "LED 3528 Xanh La"))
    )
    (comp (ref "L220")
      (value "LED 3528")
      (footprint "LED-3528-GREEN")
      (description "Dán")
      (libsource (lib "Altium_Lib_by_KhueNguyenCreator") (part "LED 3528 Xanh La"))
    )
    (comp (ref "L221")
      (value "LED 3528")
      (footprint "LED-3528-GREEN")
      (description "Dán")
      (libsource (lib "Altium_Lib_by_KhueNguyenCreator") (part "LED 3528 Xanh La"))
    )
    (comp (ref "L222")
      (value "LED 3528")
      (footprint "LED-3528-GREEN")
      (description "Dán")
      (libsource (lib "Altium_Lib_by_KhueNguyenCreator") (part "LED 3528 Xanh La"))
    )
    (comp (ref "L223")
      (value "LED 3528")
      (footprint "LED-3528-GREEN")
      (description "Dán")
      (libsource (lib "Altium_Lib_by_KhueNguyenCreator") (part "LED 3528 Xanh La"))
    )
    (comp (ref "L224")
      (value "LED 3528")
      (footprint "LED-3528-GREEN")
      (description "Dán")
      (libsource (lib "Altium_Lib_by_KhueNguyenCreator") (part "LED 3528 Xanh La"))
    )
    (comp (ref "L225")
      (value "LED 3528")
      (footprint "LED-3528-GREEN")
      (description "Dán")
      (libsource (lib "Altium_Lib_by_KhueNguyenCreator") (part "LED 3528 Xanh La"))
    )
    (comp (ref "L226")
      (value "LED 3528")
      (footprint "LED-3528-GREEN")
      (description "Dán")
      (libsource (lib "Altium_Lib_by_KhueNguyenCreator") (part "LED 3528 Xanh La"))
    )
    (comp (ref "L227")
      (value "LED 3528")
      (footprint "LED-3528-GREEN")
      (description "Dán")
      (libsource (lib "Altium_Lib_by_KhueNguyenCreator") (part "LED 3528 Xanh La"))
    )
    (comp (ref "L228")
      (value "LED 3528")
      (footprint "LED-3528-GREEN")
      (description "Dán")
      (libsource (lib "Altium_Lib_by_KhueNguyenCreator") (part "LED 3528 Xanh La"))
    )
    (comp (ref "L229")
      (value "LED 3528")
      (footprint "LED-3528-GREEN")
      (description "Dán")
      (libsource (lib "Altium_Lib_by_KhueNguyenCreator") (part "LED 3528 Xanh La"))
    )
    (comp (ref "L230")
      (value "LED 3528")
      (footprint "LED-3528-GREEN")
      (description "Dán")
      (libsource (lib "Altium_Lib_by_KhueNguyenCreator") (part "LED 3528 Xanh La"))
    )
    (comp (ref "L231")
      (value "LED 3528")
      (footprint "LED-3528-GREEN")
      (description "Dán")
      (libsource (lib "Altium_Lib_by_KhueNguyenCreator") (part "LED 3528 Xanh La"))
    )
    (comp (ref "L232")
      (value "LED 3528")
      (footprint "LED-3528-GREEN")
      (description "Dán")
      (libsource (lib "Altium_Lib_by_KhueNguyenCreator") (part "LED 3528 Xanh La"))
    )
    (comp (ref "L233")
      (value "LED 3528")
      (footprint "LED-3528-GREEN")
      (description "Dán")
      (libsource (lib "Altium_Lib_by_KhueNguyenCreator") (part "LED 3528 Xanh La"))
    )
    (comp (ref "L234")
      (value "LED 3528")
      (footprint "LED-3528-GREEN")
      (description "Dán")
      (libsource (lib "Altium_Lib_by_KhueNguyenCreator") (part "LED 3528 Xanh La"))
    )
    (comp (ref "L235")
      (value "LED 3528")
      (footprint "LED-3528-GREEN")
      (description "Dán")
      (libsource (lib "Altium_Lib_by_KhueNguyenCreator") (part "LED 3528 Xanh La"))
    )
    (comp (ref "L236")
      (value "LED 3528")
      (footprint "LED-3528-GREEN")
      (description "Dán")
      (libsource (lib "Altium_Lib_by_KhueNguyenCreator") (part "LED 3528 Xanh La"))
    )
    (comp (ref "L237")
      (value "LED 3528")
      (footprint "LED-3528-GREEN")
      (description "Dán")
      (libsource (lib "Altium_Lib_by_KhueNguyenCreator") (part "LED 3528 Xanh La"))
    )
    (comp (ref "L238")
      (value "LED 3528")
      (footprint "LED-3528-GREEN")
      (description "Dán")
      (libsource (lib "Altium_Lib_by_KhueNguyenCreator") (part "LED 3528 Xanh La"))
    )
    (comp (ref "L239")
      (value "LED 3528")
      (footprint "LED-3528-GREEN")
      (description "Dán")
      (libsource (lib "Altium_Lib_by_KhueNguyenCreator") (part "LED 3528 Xanh La"))
    )
    (comp (ref "L240")
      (value "LED 3528")
      (footprint "LED-3528-GREEN")
      (description "Dán")
      (libsource (lib "Altium_Lib_by_KhueNguyenCreator") (part "LED 3528 Xanh La"))
    )
    (comp (ref "L241")
      (value "LED 3528")
      (footprint "LED-3528-GREEN")
      (description "Dán")
      (libsource (lib "Altium_Lib_by_KhueNguyenCreator") (part "LED 3528 Xanh La"))
    )
    (comp (ref "L242")
      (value "LED 3528")
      (footprint "LED-3528-GREEN")
      (description "Dán")
      (libsource (lib "Altium_Lib_by_KhueNguyenCreator") (part "LED 3528 Xanh La"))
    )
    (comp (ref "L243")
      (value "LED 3528")
      (footprint "LED-3528-GREEN")
      (description "Dán")
      (libsource (lib "Altium_Lib_by_KhueNguyenCreator") (part "LED 3528 Xanh La"))
    )
    (comp (ref "L244")
      (value "LED 3528")
      (footprint "LED-3528-GREEN")
      (description "Dán")
      (libsource (lib "Altium_Lib_by_KhueNguyenCreator") (part "LED 3528 Xanh La"))
    )
    (comp (ref "L245")
      (value "LED 3528")
      (footprint "LED-3528-GREEN")
      (description "Dán")
      (libsource (lib "Altium_Lib_by_KhueNguyenCreator") (part "LED 3528 Xanh La"))
    )
    (comp (ref "L246")
      (value "LED 3528")
      (footprint "LED-3528-GREEN")
      (description "Dán")
      (libsource (lib "Altium_Lib_by_KhueNguyenCreator") (part "LED 3528 Xanh La"))
    )
    (comp (ref "L247")
      (value "LED 3528")
      (footprint "LED-3528-GREEN")
      (description "Dán")
      (libsource (lib "Altium_Lib_by_KhueNguyenCreator") (part "LED 3528 Xanh La"))
    )
    (comp (ref "L248")
      (value "LED 3528")
      (footprint "LED-3528-GREEN")
      (description "Dán")
      (libsource (lib "Altium_Lib_by_KhueNguyenCreator") (part "LED 3528 Xanh La"))
    )
    (comp (ref "L249")
      (value "LED 3528")
      (footprint "LED-3528-GREEN")
      (description "Dán")
      (libsource (lib "Altium_Lib_by_KhueNguyenCreator") (part "LED 3528 Xanh La"))
    )
    (comp (ref "L250")
      (value "LED 3528")
      (footprint "LED-3528-GREEN")
      (description "Dán")
      (libsource (lib "Altium_Lib_by_KhueNguyenCreator") (part "LED 3528 Xanh La"))
    )
    (comp (ref "L251")
      (value "LED 3528")
      (footprint "LED-3528-GREEN")
      (description "Dán")
      (libsource (lib "Altium_Lib_by_KhueNguyenCreator") (part "LED 3528 Xanh La"))
    )
    (comp (ref "L252")
      (value "LED 3528")
      (footprint "LED-3528-GREEN")
      (description "Dán")
      (libsource (lib "Altium_Lib_by_KhueNguyenCreator") (part "LED 3528 Xanh La"))
    )
    (comp (ref "L253")
      (value "LED 3528")
      (footprint "LED-3528-GREEN")
      (description "Dán")
      (libsource (lib "Altium_Lib_by_KhueNguyenCreator") (part "LED 3528 Xanh La"))
    )
    (comp (ref "L254")
      (value "LED 3528")
      (footprint "LED-3528-GREEN")
      (description "Dán")
      (libsource (lib "Altium_Lib_by_KhueNguyenCreator") (part "LED 3528 Xanh La"))
    )
    (comp (ref "L255")
      (value "LED 3528")
      (footprint "LED-3528-GREEN")
      (description "Dán")
      (libsource (lib "Altium_Lib_by_KhueNguyenCreator") (part "LED 3528 Xanh La"))
    )
    (comp (ref "L256")
      (value "LED 3528")
      (footprint "LED-3528-GREEN")
      (description "Dán")
      (libsource (lib "Altium_Lib_by_KhueNguyenCreator") (part "LED 3528 Xanh La"))
    )
    (comp (ref "L257")
      (value "LED 3528")
      (footprint "LED-3528-GREEN")
      (description "Dán")
      (libsource (lib "Altium_Lib_by_KhueNguyenCreator") (part "LED 3528 Xanh La"))
    )
    (comp (ref "L258")
      (value "LED 3528")
      (footprint "LED-3528-GREEN")
      (description "Dán")
      (libsource (lib "Altium_Lib_by_KhueNguyenCreator") (part "LED 3528 Xanh La"))
    )
    (comp (ref "L259")
      (value "LED 3528")
      (footprint "LED-3528-GREEN")
      (description "Dán")
      (libsource (lib "Altium_Lib_by_KhueNguyenCreator") (part "LED 3528 Xanh La"))
    )
    (comp (ref "L260")
      (value "LED 3528")
      (footprint "LED-3528-GREEN")
      (description "Dán")
      (libsource (lib "Altium_Lib_by_KhueNguyenCreator") (part "LED 3528 Xanh La"))
    )
    (comp (ref "L261")
      (value "LED 3528")
      (footprint "LED-3528-GREEN")
      (description "Dán")
      (libsource (lib "Altium_Lib_by_KhueNguyenCreator") (part "LED 3528 Xanh La"))
    )
    (comp (ref "L262")
      (value "LED 3528")
      (footprint "LED-3528-GREEN")
      (description "Dán")
      (libsource (lib "Altium_Lib_by_KhueNguyenCreator") (part "LED 3528 Xanh La"))
    )
    (comp (ref "L263")
      (value "LED 3528")
      (footprint "LED-3528-GREEN")
      (description "Dán")
      (libsource (lib "Altium_Lib_by_KhueNguyenCreator") (part "LED 3528 Xanh La"))
    )
    (comp (ref "L264")
      (value "LED 3528")
      (footprint "LED-3528-GREEN")
      (description "Dán")
      (libsource (lib "Altium_Lib_by_KhueNguyenCreator") (part "LED 3528 Xanh La"))
    )
    (comp (ref "L265")
      (value "LED 3528")
      (footprint "LED-3528-GREEN")
      (description "Dán")
      (libsource (lib "Altium_Lib_by_KhueNguyenCreator") (part "LED 3528 Xanh La"))
    )
    (comp (ref "L266")
      (value "LED 3528")
      (footprint "LED-3528-GREEN")
      (description "Dán")
      (libsource (lib "Altium_Lib_by_KhueNguyenCreator") (part "LED 3528 Xanh La"))
    )
    (comp (ref "L267")
      (value "LED 3528")
      (footprint "LED-3528-GREEN")
      (description "Dán")
      (libsource (lib "Altium_Lib_by_KhueNguyenCreator") (part "LED 3528 Xanh La"))
    )
    (comp (ref "L268")
      (value "LED 3528")
      (footprint "LED-3528-GREEN")
      (description "Dán")
      (libsource (lib "Altium_Lib_by_KhueNguyenCreator") (part "LED 3528 Xanh La"))
    )
    (comp (ref "L269")
      (value "LED 3528")
      (footprint "LED-3528-GREEN")
      (description "Dán")
      (libsource (lib "Altium_Lib_by_KhueNguyenCreator") (part "LED 3528 Xanh La"))
    )
    (comp (ref "L270")
      (value "LED 3528")
      (footprint "LED-3528-GREEN")
      (description "Dán")
      (libsource (lib "Altium_Lib_by_KhueNguyenCreator") (part "LED 3528 Xanh La"))
    )
    (comp (ref "L271")
      (value "LED 3528")
      (footprint "LED-3528-GREEN")
      (description "Dán")
      (libsource (lib "Altium_Lib_by_KhueNguyenCreator") (part "LED 3528 Xanh La"))
    )
    (comp (ref "L272")
      (value "LED 3528")
      (footprint "LED-3528-GREEN")
      (description "Dán")
      (libsource (lib "Altium_Lib_by_KhueNguyenCreator") (part "LED 3528 Xanh La"))
    )
    (comp (ref "L273")
      (value "LED 3528")
      (footprint "LED-3528-GREEN")
      (description "Dán")
      (libsource (lib "Altium_Lib_by_KhueNguyenCreator") (part "LED 3528 Xanh La"))
    )
    (comp (ref "L274")
      (value "LED 3528")
      (footprint "LED-3528-GREEN")
      (description "Dán")
      (libsource (lib "Altium_Lib_by_KhueNguyenCreator") (part "LED 3528 Xanh La"))
    )
    (comp (ref "L275")
      (value "LED 3528")
      (footprint "LED-3528-GREEN")
      (description "Dán")
      (libsource (lib "Altium_Lib_by_KhueNguyenCreator") (part "LED 3528 Xanh La"))
    )
    (comp (ref "L276")
      (value "LED 3528")
      (footprint "LED-3528-GREEN")
      (description "Dán")
      (libsource (lib "Altium_Lib_by_KhueNguyenCreator") (part "LED 3528 Xanh La"))
    )
    (comp (ref "L277")
      (value "LED 3528")
      (footprint "LED-3528-GREEN")
      (description "Dán")
      (libsource (lib "Altium_Lib_by_KhueNguyenCreator") (part "LED 3528 Xanh La"))
    )
    (comp (ref "L278")
      (value "LED 3528")
      (footprint "LED-3528-GREEN")
      (description "Dán")
      (libsource (lib "Altium_Lib_by_KhueNguyenCreator") (part "LED 3528 Xanh La"))
    )
    (comp (ref "L279")
      (value "LED 3528")
      (footprint "LED-3528-GREEN")
      (description "Dán")
      (libsource (lib "Altium_Lib_by_KhueNguyenCreator") (part "LED 3528 Xanh La"))
    )
    (comp (ref "L280")
      (value "LED 3528")
      (footprint "LED-3528-GREEN")
      (description "Dán")
      (libsource (lib "Altium_Lib_by_KhueNguyenCreator") (part "LED 3528 Xanh La"))
    )
    (comp (ref "L281")
      (value "LED 3528")
      (footprint "LED-3528-GREEN")
      (description "Dán")
      (libsource (lib "Altium_Lib_by_KhueNguyenCreator") (part "LED 3528 Xanh La"))
    )
    (comp (ref "L282")
      (value "LED 3528")
      (footprint "LED-3528-GREEN")
      (description "Dán")
      (libsource (lib "Altium_Lib_by_KhueNguyenCreator") (part "LED 3528 Xanh La"))
    )
    (comp (ref "L283")
      (value "LED 3528")
      (footprint "LED-3528-GREEN")
      (description "Dán")
      (libsource (lib "Altium_Lib_by_KhueNguyenCreator") (part "LED 3528 Xanh La"))
    )
    (comp (ref "L284")
      (value "LED 3528")
      (footprint "LED-3528-GREEN")
      (description "Dán")
      (libsource (lib "Altium_Lib_by_KhueNguyenCreator") (part "LED 3528 Xanh La"))
    )
    (comp (ref "L285")
      (value "LED 3528")
      (footprint "LED-3528-GREEN")
      (description "Dán")
      (libsource (lib "Altium_Lib_by_KhueNguyenCreator") (part "LED 3528 Xanh La"))
    )
    (comp (ref "L286")
      (value "LED 3528")
      (footprint "LED-3528-GREEN")
      (description "Dán")
      (libsource (lib "Altium_Lib_by_KhueNguyenCreator") (part "LED 3528 Xanh La"))
    )
    (comp (ref "L287")
      (value "LED 3528")
      (footprint "LED-3528-GREEN")
      (description "Dán")
      (libsource (lib "Altium_Lib_by_KhueNguyenCreator") (part "LED 3528 Xanh La"))
    )
    (comp (ref "L288")
      (value "LED 3528")
      (footprint "LED-3528-GREEN")
      (description "Dán")
      (libsource (lib "Altium_Lib_by_KhueNguyenCreator") (part "LED 3528 Xanh La"))
    )
    (comp (ref "L289")
      (value "LED 3528")
      (footprint "LED-3528-GREEN")
      (description "Dán")
      (libsource (lib "Altium_Lib_by_KhueNguyenCreator") (part "LED 3528 Xanh La"))
    )
    (comp (ref "L290")
      (value "LED 3528")
      (footprint "LED-3528-GREEN")
      (description "Dán")
      (libsource (lib "Altium_Lib_by_KhueNguyenCreator") (part "LED 3528 Xanh La"))
    )
    (comp (ref "L291")
      (value "LED 3528")
      (footprint "LED-3528-GREEN")
      (description "Dán")
      (libsource (lib "Altium_Lib_by_KhueNguyenCreator") (part "LED 3528 Xanh La"))
    )
    (comp (ref "L292")
      (value "LED 3528")
      (footprint "LED-3528-GREEN")
      (description "Dán")
      (libsource (lib "Altium_Lib_by_KhueNguyenCreator") (part "LED 3528 Xanh La"))
    )
    (comp (ref "L293")
      (value "LED 3528")
      (footprint "LED-3528-GREEN")
      (description "Dán")
      (libsource (lib "Altium_Lib_by_KhueNguyenCreator") (part "LED 3528 Xanh La"))
    )
    (comp (ref "L294")
      (value "LED 3528")
      (footprint "LED-3528-GREEN")
      (description "Dán")
      (libsource (lib "Altium_Lib_by_KhueNguyenCreator") (part "LED 3528 Xanh La"))
    )
    (comp (ref "L295")
      (value "LED 3528")
      (footprint "LED-3528-GREEN")
      (description "Dán")
      (libsource (lib "Altium_Lib_by_KhueNguyenCreator") (part "LED 3528 Xanh La"))
    )
    (comp (ref "L296")
      (value "LED 3528")
      (footprint "LED-3528-GREEN")
      (description "Dán")
      (libsource (lib "Altium_Lib_by_KhueNguyenCreator") (part "LED 3528 Xanh La"))
    )
    (comp (ref "L297")
      (value "LED 3528")
      (footprint "LED-3528-GREEN")
      (description "Dán")
      (libsource (lib "Altium_Lib_by_KhueNguyenCreator") (part "LED 3528 Xanh La"))
    )
    (comp (ref "L298")
      (value "LED 3528")
      (footprint "LED-3528-GREEN")
      (description "Dán")
      (libsource (lib "Altium_Lib_by_KhueNguyenCreator") (part "LED 3528 Xanh La"))
    )
    (comp (ref "L299")
      (value "LED 3528")
      (footprint "LED-3528-GREEN")
      (description "Dán")
      (libsource (lib "Altium_Lib_by_KhueNguyenCreator") (part "LED 3528 Xanh La"))
    )
    (comp (ref "L300")
      (value "LED 3528")
      (footprint "LED-3528-GREEN")
      (description "Dán")
      (libsource (lib "Altium_Lib_by_KhueNguyenCreator") (part "LED 3528 Xanh La"))
    )
    (comp (ref "L301")
      (value "LED 3528")
      (footprint "LED-3528-GREEN")
      (description "Dán")
      (libsource (lib "Altium_Lib_by_KhueNguyenCreator") (part "LED 3528 Xanh La"))
    )
    (comp (ref "L302")
      (value "LED 3528")
      (footprint "LED-3528-GREEN")
      (description "Dán")
      (libsource (lib "Altium_Lib_by_KhueNguyenCreator") (part "LED 3528 Xanh La"))
    )
    (comp (ref "L303")
      (value "LED 3528")
      (footprint "LED-3528-GREEN")
      (description "Dán")
      (libsource (lib "Altium_Lib_by_KhueNguyenCreator") (part "LED 3528 Xanh La"))
    )
    (comp (ref "L304")
      (value "LED 3528")
      (footprint "LED-3528-GREEN")
      (description "Dán")
      (libsource (lib "Altium_Lib_by_KhueNguyenCreator") (part "LED 3528 Xanh La"))
    )
    (comp (ref "L305")
      (value "LED 3528")
      (footprint "LED-3528-GREEN")
      (description "Dán")
      (libsource (lib "Altium_Lib_by_KhueNguyenCreator") (part "LED 3528 Xanh La"))
    )
    (comp (ref "L306")
      (value "LED 3528")
      (footprint "LED-3528-GREEN")
      (description "Dán")
      (libsource (lib "Altium_Lib_by_KhueNguyenCreator") (part "LED 3528 Xanh La"))
    )
    (comp (ref "L307")
      (value "LED 3528")
      (footprint "LED-3528-GREEN")
      (description "Dán")
      (libsource (lib "Altium_Lib_by_KhueNguyenCreator") (part "LED 3528 Xanh La"))
    )
    (comp (ref "L308")
      (value "LED 3528")
      (footprint "LED-3528-GREEN")
      (description "Dán")
      (libsource (lib "Altium_Lib_by_KhueNguyenCreator") (part "LED 3528 Xanh La"))
    )
    (comp (ref "L309")
      (value "LED 3528")
      (footprint "LED-3528-GREEN")
      (description "Dán")
      (libsource (lib "Altium_Lib_by_KhueNguyenCreator") (part "LED 3528 Xanh La"))
    )
    (comp (ref "L310")
      (value "LED 3528")
      (footprint "LED-3528-GREEN")
      (description "Dán")
      (libsource (lib "Altium_Lib_by_KhueNguyenCreator") (part "LED 3528 Xanh La"))
    )
    (comp (ref "L311")
      (value "LED 3528")
      (footprint "LED-3528-GREEN")
      (description "Dán")
      (libsource (lib "Altium_Lib_by_KhueNguyenCreator") (part "LED 3528 Xanh La"))
    )
    (comp (ref "L312")
      (value "LED 3528")
      (footprint "LED-3528-GREEN")
      (description "Dán")
      (libsource (lib "Altium_Lib_by_KhueNguyenCreator") (part "LED 3528 Xanh La"))
    )
    (comp (ref "L313")
      (value "LED 3528")
      (footprint "LED-3528-GREEN")
      (description "Dán")
      (libsource (lib "Altium_Lib_by_KhueNguyenCreator") (part "LED 3528 Xanh La"))
    )
    (comp (ref "L314")
      (value "LED 3528")
      (footprint "LED-3528-GREEN")
      (description "Dán")
      (libsource (lib "Altium_Lib_by_KhueNguyenCreator") (part "LED 3528 Xanh La"))
    )
    (comp (ref "L315")
      (value "LED 3528")
      (footprint "LED-3528-GREEN")
      (description "Dán")
      (libsource (lib "Altium_Lib_by_KhueNguyenCreator") (part "LED 3528 Xanh La"))
    )
    (comp (ref "L316")
      (value "LED 3528")
      (footprint "LED-3528-GREEN")
      (description "Dán")
      (libsource (lib "Altium_Lib_by_KhueNguyenCreator") (part "LED 3528 Xanh La"))
    )
    (comp (ref "L317")
      (value "LED 3528")
      (footprint "LED-3528-GREEN")
      (description "Dán")
      (libsource (lib "Altium_Lib_by_KhueNguyenCreator") (part "LED 3528 Xanh La"))
    )
    (comp (ref "L318")
      (value "LED 3528")
      (footprint "LED-3528-GREEN")
      (description "Dán")
      (libsource (lib "Altium_Lib_by_KhueNguyenCreator") (part "LED 3528 Xanh La"))
    )
    (comp (ref "L319")
      (value "LED 3528")
      (footprint "LED-3528-GREEN")
      (description "Dán")
      (libsource (lib "Altium_Lib_by_KhueNguyenCreator") (part "LED 3528 Xanh La"))
    )
    (comp (ref "L320")
      (value "LED 3528")
      (footprint "LED-3528-GREEN")
      (description "Dán")
      (libsource (lib "Altium_Lib_by_KhueNguyenCreator") (part "LED 3528 Xanh La"))
    )
    (comp (ref "L321")
      (value "LED 3528")
      (footprint "LED-3528-GREEN")
      (description "Dán")
      (libsource (lib "Altium_Lib_by_KhueNguyenCreator") (part "LED 3528 Xanh La"))
    )
    (comp (ref "L322")
      (value "LED 3528")
      (footprint "LED-3528-GREEN")
      (description "Dán")
      (libsource (lib "Altium_Lib_by_KhueNguyenCreator") (part "LED 3528 Xanh La"))
    )
    (comp (ref "L323")
      (value "LED 3528")
      (footprint "LED-3528-GREEN")
      (description "Dán")
      (libsource (lib "Altium_Lib_by_KhueNguyenCreator") (part "LED 3528 Xanh La"))
    )
    (comp (ref "L324")
      (value "LED 3528")
      (footprint "LED-3528-GREEN")
      (description "Dán")
      (libsource (lib "Altium_Lib_by_KhueNguyenCreator") (part "LED 3528 Xanh La"))
    )
    (comp (ref "L325")
      (value "LED 3528")
      (footprint "LED-3528-GREEN")
      (description "Dán")
      (libsource (lib "Altium_Lib_by_KhueNguyenCreator") (part "LED 3528 Xanh La"))
    )
    (comp (ref "L326")
      (value "LED 3528")
      (footprint "LED-3528-GREEN")
      (description "Dán")
      (libsource (lib "Altium_Lib_by_KhueNguyenCreator") (part "LED 3528 Xanh La"))
    )
    (comp (ref "L327")
      (value "LED 3528")
      (footprint "LED-3528-GREEN")
      (description "Dán")
      (libsource (lib "Altium_Lib_by_KhueNguyenCreator") (part "LED 3528 Xanh La"))
    )
    (comp (ref "L328")
      (value "LED 3528")
      (footprint "LED-3528-GREEN")
      (description "Dán")
      (libsource (lib "Altium_Lib_by_KhueNguyenCreator") (part "LED 3528 Xanh La"))
    )
    (comp (ref "L329")
      (value "LED 3528")
      (footprint "LED-3528-GREEN")
      (description "Dán")
      (libsource (lib "Altium_Lib_by_KhueNguyenCreator") (part "LED 3528 Xanh La"))
    )
    (comp (ref "L330")
      (value "LED 3528")
      (footprint "LED-3528-GREEN")
      (description "Dán")
      (libsource (lib "Altium_Lib_by_KhueNguyenCreator") (part "LED 3528 Xanh La"))
    )
    (comp (ref "L331")
      (value "LED 3528")
      (footprint "LED-3528-GREEN")
      (description "Dán")
      (libsource (lib "Altium_Lib_by_KhueNguyenCreator") (part "LED 3528 Xanh La"))
    )
    (comp (ref "L332")
      (value "LED 3528")
      (footprint "LED-3528-GREEN")
      (description "Dán")
      (libsource (lib "Altium_Lib_by_KhueNguyenCreator") (part "LED 3528 Xanh La"))
    )
    (comp (ref "L333")
      (value "LED 3528")
      (footprint "LED-3528-GREEN")
      (description "Dán")
      (libsource (lib "Altium_Lib_by_KhueNguyenCreator") (part "LED 3528 Xanh La"))
    )
    (comp (ref "L334")
      (value "LED 3528")
      (footprint "LED-3528-GREEN")
      (description "Dán")
      (libsource (lib "Altium_Lib_by_KhueNguyenCreator") (part "LED 3528 Xanh La"))
    )
    (comp (ref "L335")
      (value "LED 3528")
      (footprint "LED-3528-GREEN")
      (description "Dán")
      (libsource (lib "Altium_Lib_by_KhueNguyenCreator") (part "LED 3528 Xanh La"))
    )
    (comp (ref "L336")
      (value "LED 3528")
      (footprint "LED-3528-GREEN")
      (description "Dán")
      (libsource (lib "Altium_Lib_by_KhueNguyenCreator") (part "LED 3528 Xanh La"))
    )
    (comp (ref "L337")
      (value "LED 3528")
      (footprint "LED-3528-GREEN")
      (description "Dán")
      (libsource (lib "Altium_Lib_by_KhueNguyenCreator") (part "LED 3528 Xanh La"))
    )
    (comp (ref "L338")
      (value "LED 3528")
      (footprint "LED-3528-GREEN")
      (description "Dán")
      (libsource (lib "Altium_Lib_by_KhueNguyenCreator") (part "LED 3528 Xanh La"))
    )
    (comp (ref "L339")
      (value "LED 3528")
      (footprint "LED-3528-GREEN")
      (description "Dán")
      (libsource (lib "Altium_Lib_by_KhueNguyenCreator") (part "LED 3528 Xanh La"))
    )
    (comp (ref "L340")
      (value "LED 3528")
      (footprint "LED-3528-GREEN")
      (description "Dán")
      (libsource (lib "Altium_Lib_by_KhueNguyenCreator") (part "LED 3528 Xanh La"))
    )
    (comp (ref "L341")
      (value "LED 3528")
      (footprint "LED-3528-GREEN")
      (description "Dán")
      (libsource (lib "Altium_Lib_by_KhueNguyenCreator") (part "LED 3528 Xanh La"))
    )
    (comp (ref "L342")
      (value "LED 3528")
      (footprint "LED-3528-GREEN")
      (description "Dán")
      (libsource (lib "Altium_Lib_by_KhueNguyenCreator") (part "LED 3528 Xanh La"))
    )
    (comp (ref "L343")
      (value "LED 3528")
      (footprint "LED-3528-GREEN")
      (description "Dán")
      (libsource (lib "Altium_Lib_by_KhueNguyenCreator") (part "LED 3528 Xanh La"))
    )
    (comp (ref "L344")
      (value "LED 3528")
      (footprint "LED-3528-GREEN")
      (description "Dán")
      (libsource (lib "Altium_Lib_by_KhueNguyenCreator") (part "LED 3528 Xanh La"))
    )
    (comp (ref "L345")
      (value "LED 3528")
      (footprint "LED-3528-GREEN")
      (description "Dán")
      (libsource (lib "Altium_Lib_by_KhueNguyenCreator") (part "LED 3528 Xanh La"))
    )
    (comp (ref "L346")
      (value "LED 3528")
      (footprint "LED-3528-GREEN")
      (description "Dán")
      (libsource (lib "Altium_Lib_by_KhueNguyenCreator") (part "LED 3528 Xanh La"))
    )
    (comp (ref "L347")
      (value "LED 3528")
      (footprint "LED-3528-GREEN")
      (description "Dán")
      (libsource (lib "Altium_Lib_by_KhueNguyenCreator") (part "LED 3528 Xanh La"))
    )
    (comp (ref "L348")
      (value "LED 3528")
      (footprint "LED-3528-GREEN")
      (description "Dán")
      (libsource (lib "Altium_Lib_by_KhueNguyenCreator") (part "LED 3528 Xanh La"))
    )
    (comp (ref "L349")
      (value "LED 3528")
      (footprint "LED-3528-GREEN")
      (description "Dán")
      (libsource (lib "Altium_Lib_by_KhueNguyenCreator") (part "LED 3528 Xanh La"))
    )
    (comp (ref "L350")
      (value "LED 3528")
      (footprint "LED-3528-GREEN")
      (description "Dán")
      (libsource (lib "Altium_Lib_by_KhueNguyenCreator") (part "LED 3528 Xanh La"))
    )
    (comp (ref "L351")
      (value "LED 3528")
      (footprint "LED-3528-GREEN")
      (description "Dán")
      (libsource (lib "Altium_Lib_by_KhueNguyenCreator") (part "LED 3528 Xanh La"))
    )
    (comp (ref "L352")
      (value "LED 3528")
      (footprint "LED-3528-GREEN")
      (description "Dán")
      (libsource (lib "Altium_Lib_by_KhueNguyenCreator") (part "LED 3528 Xanh La"))
    )
    (comp (ref "L353")
      (value "LED 3528")
      (footprint "LED-3528-GREEN")
      (description "Dán")
      (libsource (lib "Altium_Lib_by_KhueNguyenCreator") (part "LED 3528 Xanh La"))
    )
    (comp (ref "L354")
      (value "LED 3528")
      (footprint "LED-3528-GREEN")
      (description "Dán")
      (libsource (lib "Altium_Lib_by_KhueNguyenCreator") (part "LED 3528 Xanh La"))
    )
    (comp (ref "L355")
      (value "LED 3528")
      (footprint "LED-3528-GREEN")
      (description "Dán")
      (libsource (lib "Altium_Lib_by_KhueNguyenCreator") (part "LED 3528 Xanh La"))
    )
    (comp (ref "L356")
      (value "LED 3528")
      (footprint "LED-3528-GREEN")
      (description "Dán")
      (libsource (lib "Altium_Lib_by_KhueNguyenCreator") (part "LED 3528 Xanh La"))
    )
    (comp (ref "L357")
      (value "LED 3528")
      (footprint "LED-3528-GREEN")
      (description "Dán")
      (libsource (lib "Altium_Lib_by_KhueNguyenCreator") (part "LED 3528 Xanh La"))
    )
    (comp (ref "L358")
      (value "LED 3528")
      (footprint "LED-3528-GREEN")
      (description "Dán")
      (libsource (lib "Altium_Lib_by_KhueNguyenCreator") (part "LED 3528 Xanh La"))
    )
    (comp (ref "L359")
      (value "LED 3528")
      (footprint "LED-3528-GREEN")
      (description "Dán")
      (libsource (lib "Altium_Lib_by_KhueNguyenCreator") (part "LED 3528 Xanh La"))
    )
    (comp (ref "L360")
      (value "LED 3528")
      (footprint "LED-3528-GREEN")
      (description "Dán")
      (libsource (lib "Altium_Lib_by_KhueNguyenCreator") (part "LED 3528 Xanh La"))
    )
    (comp (ref "L361")
      (value "LED 3528")
      (footprint "LED-3528-GREEN")
      (description "Dán")
      (libsource (lib "Altium_Lib_by_KhueNguyenCreator") (part "LED 3528 Xanh La"))
    )
    (comp (ref "L362")
      (value "LED 3528")
      (footprint "LED-3528-GREEN")
      (description "Dán")
      (libsource (lib "Altium_Lib_by_KhueNguyenCreator") (part "LED 3528 Xanh La"))
    )
    (comp (ref "L363")
      (value "LED 3528")
      (footprint "LED-3528-GREEN")
      (description "Dán")
      (libsource (lib "Altium_Lib_by_KhueNguyenCreator") (part "LED 3528 Xanh La"))
    )
    (comp (ref "L364")
      (value "LED 3528")
      (footprint "LED-3528-GREEN")
      (description "Dán")
      (libsource (lib "Altium_Lib_by_KhueNguyenCreator") (part "LED 3528 Xanh La"))
    )
    (comp (ref "L365")
      (value "LED 3528")
      (footprint "LED-3528-GREEN")
      (description "Dán")
      (libsource (lib "Altium_Lib_by_KhueNguyenCreator") (part "LED 3528 Xanh La"))
    )
    (comp (ref "L366")
      (value "LED 3528")
      (footprint "LED-3528-GREEN")
      (description "Dán")
      (libsource (lib "Altium_Lib_by_KhueNguyenCreator") (part "LED 3528 Xanh La"))
    )
    (comp (ref "L367")
      (value "LED 3528")
      (footprint "LED-3528-GREEN")
      (description "Dán")
      (libsource (lib "Altium_Lib_by_KhueNguyenCreator") (part "LED 3528 Xanh La"))
    )
    (comp (ref "L368")
      (value "LED 3528")
      (footprint "LED-3528-GREEN")
      (description "Dán")
      (libsource (lib "Altium_Lib_by_KhueNguyenCreator") (part "LED 3528 Xanh La"))
    )
    (comp (ref "L369")
      (value "LED 3528")
      (footprint "LED-3528-GREEN")
      (description "Dán")
      (libsource (lib "Altium_Lib_by_KhueNguyenCreator") (part "LED 3528 Xanh La"))
    )
    (comp (ref "L370")
      (value "LED 3528")
      (footprint "LED-3528-GREEN")
      (description "Dán")
      (libsource (lib "Altium_Lib_by_KhueNguyenCreator") (part "LED 3528 Xanh La"))
    )
    (comp (ref "L371")
      (value "LED 3528")
      (footprint "LED-3528-GREEN")
      (description "Dán")
      (libsource (lib "Altium_Lib_by_KhueNguyenCreator") (part "LED 3528 Xanh La"))
    )
    (comp (ref "L372")
      (value "LED 3528")
      (footprint "LED-3528-GREEN")
      (description "Dán")
      (libsource (lib "Altium_Lib_by_KhueNguyenCreator") (part "LED 3528 Xanh La"))
    )
    (comp (ref "L373")
      (value "LED 3528")
      (footprint "LED-3528-GREEN")
      (description "Dán")
      (libsource (lib "Altium_Lib_by_KhueNguyenCreator") (part "LED 3528 Xanh La"))
    )
    (comp (ref "L374")
      (value "LED 3528")
      (footprint "LED-3528-GREEN")
      (description "Dán")
      (libsource (lib "Altium_Lib_by_KhueNguyenCreator") (part "LED 3528 Xanh La"))
    )
    (comp (ref "L375")
      (value "LED 3528")
      (footprint "LED-3528-GREEN")
      (description "Dán")
      (libsource (lib "Altium_Lib_by_KhueNguyenCreator") (part "LED 3528 Xanh La"))
    )
    (comp (ref "L376")
      (value "LED 3528")
      (footprint "LED-3528-GREEN")
      (description "Dán")
      (libsource (lib "Altium_Lib_by_KhueNguyenCreator") (part "LED 3528 Xanh La"))
    )
    (comp (ref "L377")
      (value "LED 3528")
      (footprint "LED-3528-GREEN")
      (description "Dán")
      (libsource (lib "Altium_Lib_by_KhueNguyenCreator") (part "LED 3528 Xanh La"))
    )
    (comp (ref "L378")
      (value "LED 3528")
      (footprint "LED-3528-GREEN")
      (description "Dán")
      (libsource (lib "Altium_Lib_by_KhueNguyenCreator") (part "LED 3528 Xanh La"))
    )
    (comp (ref "L379")
      (value "LED 3528")
      (footprint "LED-3528-GREEN")
      (description "Dán")
      (libsource (lib "Altium_Lib_by_KhueNguyenCreator") (part "LED 3528 Xanh La"))
    )
    (comp (ref "L380")
      (value "LED 3528")
      (footprint "LED-3528-GREEN")
      (description "Dán")
      (libsource (lib "Altium_Lib_by_KhueNguyenCreator") (part "LED 3528 Xanh La"))
    )
    (comp (ref "L381")
      (value "LED 3528")
      (footprint "LED-3528-GREEN")
      (description "Dán")
      (libsource (lib "Altium_Lib_by_KhueNguyenCreator") (part "LED 3528 Xanh La"))
    )
    (comp (ref "L382")
      (value "LED 3528")
      (footprint "LED-3528-GREEN")
      (description "Dán")
      (libsource (lib "Altium_Lib_by_KhueNguyenCreator") (part "LED 3528 Xanh La"))
    )
    (comp (ref "L383")
      (value "LED 3528")
      (footprint "LED-3528-GREEN")
      (description "Dán")
      (libsource (lib "Altium_Lib_by_KhueNguyenCreator") (part "LED 3528 Xanh La"))
    )
    (comp (ref "L384")
      (value "LED 3528")
      (footprint "LED-3528-GREEN")
      (description "Dán")
      (libsource (lib "Altium_Lib_by_KhueNguyenCreator") (part "LED 3528 Xanh La"))
    )
    (comp (ref "L385")
      (value "LED 3528")
      (footprint "LED-3528-GREEN")
      (description "Dán")
      (libsource (lib "Altium_Lib_by_KhueNguyenCreator") (part "LED 3528 Xanh La"))
    )
    (comp (ref "L386")
      (value "LED 3528")
      (footprint "LED-3528-GREEN")
      (description "Dán")
      (libsource (lib "Altium_Lib_by_KhueNguyenCreator") (part "LED 3528 Xanh La"))
    )
    (comp (ref "L387")
      (value "LED 3528")
      (footprint "LED-3528-GREEN")
      (description "Dán")
      (libsource (lib "Altium_Lib_by_KhueNguyenCreator") (part "LED 3528 Xanh La"))
    )
    (comp (ref "L388")
      (value "LED 3528")
      (footprint "LED-3528-GREEN")
      (description "Dán")
      (libsource (lib "Altium_Lib_by_KhueNguyenCreator") (part "LED 3528 Xanh La"))
    )
    (comp (ref "L389")
      (value "LED 3528")
      (footprint "LED-3528-GREEN")
      (description "Dán")
      (libsource (lib "Altium_Lib_by_KhueNguyenCreator") (part "LED 3528 Xanh La"))
    )
    (comp (ref "L390")
      (value "LED 3528")
      (footprint "LED-3528-GREEN")
      (description "Dán")
      (libsource (lib "Altium_Lib_by_KhueNguyenCreator") (part "LED 3528 Xanh La"))
    )
    (comp (ref "L391")
      (value "LED 3528")
      (footprint "LED-3528-GREEN")
      (description "Dán")
      (libsource (lib "Altium_Lib_by_KhueNguyenCreator") (part "LED 3528 Xanh La"))
    )
    (comp (ref "L392")
      (value "LED 3528")
      (footprint "LED-3528-GREEN")
      (description "Dán")
      (libsource (lib "Altium_Lib_by_KhueNguyenCreator") (part "LED 3528 Xanh La"))
    )
    (comp (ref "L393")
      (value "LED 3528")
      (footprint "LED-3528-GREEN")
      (description "Dán")
      (libsource (lib "Altium_Lib_by_KhueNguyenCreator") (part "LED 3528 Xanh La"))
    )
    (comp (ref "L394")
      (value "LED 3528")
      (footprint "LED-3528-GREEN")
      (description "Dán")
      (libsource (lib "Altium_Lib_by_KhueNguyenCreator") (part "LED 3528 Xanh La"))
    )
    (comp (ref "L395")
      (value "LED 3528")
      (footprint "LED-3528-GREEN")
      (description "Dán")
      (libsource (lib "Altium_Lib_by_KhueNguyenCreator") (part "LED 3528 Xanh La"))
    )
    (comp (ref "L396")
      (value "LED 3528")
      (footprint "LED-3528-GREEN")
      (description "Dán")
      (libsource (lib "Altium_Lib_by_KhueNguyenCreator") (part "LED 3528 Xanh La"))
    )
    (comp (ref "L397")
      (value "LED 3528")
      (footprint "LED-3528-GREEN")
      (description "Dán")
      (libsource (lib "Altium_Lib_by_KhueNguyenCreator") (part "LED 3528 Xanh La"))
    )
    (comp (ref "L398")
      (value "LED 3528")
      (footprint "LED-3528-GREEN")
      (description "Dán")
      (libsource (lib "Altium_Lib_by_KhueNguyenCreator") (part "LED 3528 Xanh La"))
    )
    (comp (ref "L399")
      (value "LED 3528")
      (footprint "LED-3528-GREEN")
      (description "Dán")
      (libsource (lib "Altium_Lib_by_KhueNguyenCreator") (part "LED 3528 Xanh La"))
    )
    (comp (ref "L400")
      (value "LED 3528")
      (footprint "LED-3528-GREEN")
      (description "Dán")
      (libsource (lib "Altium_Lib_by_KhueNguyenCreator") (part "LED 3528 Xanh La"))
    )
    (comp (ref "L401")
      (value "LED 3528")
      (footprint "LED-3528-GREEN")
      (description "Dán")
      (libsource (lib "Altium_Lib_by_KhueNguyenCreator") (part "LED 3528 Xanh La"))
    )
    (comp (ref "L402")
      (value "LED 3528")
      (footprint "LED-3528-GREEN")
      (description "Dán")
      (libsource (lib "Altium_Lib_by_KhueNguyenCreator") (part "LED 3528 Xanh La"))
    )
    (comp (ref "L403")
      (value "LED 3528")
      (footprint "LED-3528-GREEN")
      (description "Dán")
      (libsource (lib "Altium_Lib_by_KhueNguyenCreator") (part "LED 3528 Xanh La"))
    )
    (comp (ref "L404")
      (value "LED 3528")
      (footprint "LED-3528-GREEN")
      (description "Dán")
      (libsource (lib "Altium_Lib_by_KhueNguyenCreator") (part "LED 3528 Xanh La"))
    )
    (comp (ref "L405")
      (value "LED 3528")
      (footprint "LED-3528-GREEN")
      (description "Dán")
      (libsource (lib "Altium_Lib_by_KhueNguyenCreator") (part "LED 3528 Xanh La"))
    )
    (comp (ref "L406")
      (value "LED 3528")
      (footprint "LED-3528-GREEN")
      (description "Dán")
      (libsource (lib "Altium_Lib_by_KhueNguyenCreator") (part "LED 3528 Xanh La"))
    )
    (comp (ref "L407")
      (value "LED 3528")
      (footprint "LED-3528-GREEN")
      (description "Dán")
      (libsource (lib "Altium_Lib_by_KhueNguyenCreator") (part "LED 3528 Xanh La"))
    )
    (comp (ref "L408")
      (value "LED 3528")
      (footprint "LED-3528-GREEN")
      (description "Dán")
      (libsource (lib "Altium_Lib_by_KhueNguyenCreator") (part "LED 3528 Xanh La"))
    )
    (comp (ref "L409")
      (value "LED 3528")
      (footprint "LED-3528-GREEN")
      (description "Dán")
      (libsource (lib "Altium_Lib_by_KhueNguyenCreator") (part "LED 3528 Xanh La"))
    )
    (comp (ref "L410")
      (value "LED 3528")
      (footprint "LED-3528-GREEN")
      (description "Dán")
      (libsource (lib "Altium_Lib_by_KhueNguyenCreator") (part "LED 3528 Xanh La"))
    )
    (comp (ref "L411")
      (value "LED 3528")
      (footprint "LED-3528-GREEN")
      (description "Dán")
      (libsource (lib "Altium_Lib_by_KhueNguyenCreator") (part "LED 3528 Xanh La"))
    )
    (comp (ref "L412")
      (value "LED 3528")
      (footprint "LED-3528-GREEN")
      (description "Dán")
      (libsource (lib "Altium_Lib_by_KhueNguyenCreator") (part "LED 3528 Xanh La"))
    )
    (comp (ref "L413")
      (value "LED 3528")
      (footprint "LED-3528-GREEN")
      (description "Dán")
      (libsource (lib "Altium_Lib_by_KhueNguyenCreator") (part "LED 3528 Xanh La"))
    )
    (comp (ref "L414")
      (value "LED 3528")
      (footprint "LED-3528-GREEN")
      (description "Dán")
      (libsource (lib "Altium_Lib_by_KhueNguyenCreator") (part "LED 3528 Xanh La"))
    )
    (comp (ref "L415")
      (value "LED 3528")
      (footprint "LED-3528-GREEN")
      (description "Dán")
      (libsource (lib "Altium_Lib_by_KhueNguyenCreator") (part "LED 3528 Xanh La"))
    )
    (comp (ref "L416")
      (value "LED 3528")
      (footprint "LED-3528-GREEN")
      (description "Dán")
      (libsource (lib "Altium_Lib_by_KhueNguyenCreator") (part "LED 3528 Xanh La"))
    )
    (comp (ref "L417")
      (value "LED 3528")
      (footprint "LED-3528-GREEN")
      (description "Dán")
      (libsource (lib "Altium_Lib_by_KhueNguyenCreator") (part "LED 3528 Xanh La"))
    )
    (comp (ref "L418")
      (value "LED 3528")
      (footprint "LED-3528-GREEN")
      (description "Dán")
      (libsource (lib "Altium_Lib_by_KhueNguyenCreator") (part "LED 3528 Xanh La"))
    )
    (comp (ref "L419")
      (value "LED 3528")
      (footprint "LED-3528-GREEN")
      (description "Dán")
      (libsource (lib "Altium_Lib_by_KhueNguyenCreator") (part "LED 3528 Xanh La"))
    )
    (comp (ref "L420")
      (value "LED 3528")
      (footprint "LED-3528-GREEN")
      (description "Dán")
      (libsource (lib "Altium_Lib_by_KhueNguyenCreator") (part "LED 3528 Xanh La"))
    )
    (comp (ref "L421")
      (value "LED 3528")
      (footprint "LED-3528-GREEN")
      (description "Dán")
      (libsource (lib "Altium_Lib_by_KhueNguyenCreator") (part "LED 3528 Xanh La"))
    )
    (comp (ref "L422")
      (value "LED 3528")
      (footprint "LED-3528-GREEN")
      (description "Dán")
      (libsource (lib "Altium_Lib_by_KhueNguyenCreator") (part "LED 3528 Xanh La"))
    )
    (comp (ref "L423")
      (value "LED 3528")
      (footprint "LED-3528-GREEN")
      (description "Dán")
      (libsource (lib "Altium_Lib_by_KhueNguyenCreator") (part "LED 3528 Xanh La"))
    )
    (comp (ref "L424")
      (value "LED 3528")
      (footprint "LED-3528-GREEN")
      (description "Dán")
      (libsource (lib "Altium_Lib_by_KhueNguyenCreator") (part "LED 3528 Xanh La"))
    )
    (comp (ref "L425")
      (value "LED 3528")
      (footprint "LED-3528-GREEN")
      (description "Dán")
      (libsource (lib "Altium_Lib_by_KhueNguyenCreator") (part "LED 3528 Xanh La"))
    )
    (comp (ref "L426")
      (value "LED 3528")
      (footprint "LED-3528-GREEN")
      (description "Dán")
      (libsource (lib "Altium_Lib_by_KhueNguyenCreator") (part "LED 3528 Xanh La"))
    )
    (comp (ref "L427")
      (value "LED 3528")
      (footprint "LED-3528-GREEN")
      (description "Dán")
      (libsource (lib "Altium_Lib_by_KhueNguyenCreator") (part "LED 3528 Xanh La"))
    )
    (comp (ref "L428")
      (value "LED 3528")
      (footprint "LED-3528-GREEN")
      (description "Dán")
      (libsource (lib "Altium_Lib_by_KhueNguyenCreator") (part "LED 3528 Xanh La"))
    )
    (comp (ref "L429")
      (value "LED 3528")
      (footprint "LED-3528-GREEN")
      (description "Dán")
      (libsource (lib "Altium_Lib_by_KhueNguyenCreator") (part "LED 3528 Xanh La"))
    )
    (comp (ref "L430")
      (value "LED 3528")
      (footprint "LED-3528-GREEN")
      (description "Dán")
      (libsource (lib "Altium_Lib_by_KhueNguyenCreator") (part "LED 3528 Xanh La"))
    )
    (comp (ref "L431")
      (value "LED 3528")
      (footprint "LED-3528-GREEN")
      (description "Dán")
      (libsource (lib "Altium_Lib_by_KhueNguyenCreator") (part "LED 3528 Xanh La"))
    )
    (comp (ref "L432")
      (value "LED 3528")
      (footprint "LED-3528-GREEN")
      (description "Dán")
      (libsource (lib "Altium_Lib_by_KhueNguyenCreator") (part "LED 3528 Xanh La"))
    )
    (comp (ref "L433")
      (value "LED 3528")
      (footprint "LED-3528-GREEN")
      (description "Dán")
      (libsource (lib "Altium_Lib_by_KhueNguyenCreator") (part "LED 3528 Xanh La"))
    )
    (comp (ref "L434")
      (value "LED 3528")
      (footprint "LED-3528-GREEN")
      (description "Dán")
      (libsource (lib "Altium_Lib_by_KhueNguyenCreator") (part "LED 3528 Xanh La"))
    )
    (comp (ref "L435")
      (value "LED 3528")
      (footprint "LED-3528-GREEN")
      (description "Dán")
      (libsource (lib "Altium_Lib_by_KhueNguyenCreator") (part "LED 3528 Xanh La"))
    )
    (comp (ref "L436")
      (value "LED 3528")
      (footprint "LED-3528-GREEN")
      (description "Dán")
      (libsource (lib "Altium_Lib_by_KhueNguyenCreator") (part "LED 3528 Xanh La"))
    )
    (comp (ref "L437")
      (value "LED 3528")
      (footprint "LED-3528-GREEN")
      (description "Dán")
      (libsource (lib "Altium_Lib_by_KhueNguyenCreator") (part "LED 3528 Xanh La"))
    )
    (comp (ref "L438")
      (value "LED 3528")
      (footprint "LED-3528-GREEN")
      (description "Dán")
      (libsource (lib "Altium_Lib_by_KhueNguyenCreator") (part "LED 3528 Xanh La"))
    )
    (comp (ref "L439")
      (value "LED 3528")
      (footprint "LED-3528-GREEN")
      (description "Dán")
      (libsource (lib "Altium_Lib_by_KhueNguyenCreator") (part "LED 3528 Xanh La"))
    )
    (comp (ref "L440")
      (value "LED 3528")
      (footprint "LED-3528-GREEN")
      (description "Dán")
      (libsource (lib "Altium_Lib_by_KhueNguyenCreator") (part "LED 3528 Xanh La"))
    )
    (comp (ref "L441")
      (value "LED 3528")
      (footprint "LED-3528-GREEN")
      (description "Dán")
      (libsource (lib "Altium_Lib_by_KhueNguyenCreator") (part "LED 3528 Xanh La"))
    )
    (comp (ref "L442")
      (value "LED 3528")
      (footprint "LED-3528-GREEN")
      (description "Dán")
      (libsource (lib "Altium_Lib_by_KhueNguyenCreator") (part "LED 3528 Xanh La"))
    )
    (comp (ref "L443")
      (value "LED 3528")
      (footprint "LED-3528-GREEN")
      (description "Dán")
      (libsource (lib "Altium_Lib_by_KhueNguyenCreator") (part "LED 3528 Xanh La"))
    )
    (comp (ref "L444")
      (value "LED 3528")
      (footprint "LED-3528-GREEN")
      (description "Dán")
      (libsource (lib "Altium_Lib_by_KhueNguyenCreator") (part "LED 3528 Xanh La"))
    )
    (comp (ref "L445")
      (value "LED 3528")
      (footprint "LED-3528-GREEN")
      (description "Dán")
      (libsource (lib "Altium_Lib_by_KhueNguyenCreator") (part "LED 3528 Xanh La"))
    )
    (comp (ref "L446")
      (value "LED 3528")
      (footprint "LED-3528-GREEN")
      (description "Dán")
      (libsource (lib "Altium_Lib_by_KhueNguyenCreator") (part "LED 3528 Xanh La"))
    )
    (comp (ref "L447")
      (value "LED 3528")
      (footprint "LED-3528-GREEN")
      (description "Dán")
      (libsource (lib "Altium_Lib_by_KhueNguyenCreator") (part "LED 3528 Xanh La"))
    )
    (comp (ref "L448")
      (value "LED 3528")
      (footprint "LED-3528-GREEN")
      (description "Dán")
      (libsource (lib "Altium_Lib_by_KhueNguyenCreator") (part "LED 3528 Xanh La"))
    )
    (comp (ref "L449")
      (value "LED 3528")
      (footprint "LED-3528-GREEN")
      (description "Dán")
      (libsource (lib "Altium_Lib_by_KhueNguyenCreator") (part "LED 3528 Xanh La"))
    )
    (comp (ref "L450")
      (value "LED 3528")
      (footprint "LED-3528-GREEN")
      (description "Dán")
      (libsource (lib "Altium_Lib_by_KhueNguyenCreator") (part "LED 3528 Xanh La"))
    )
    (comp (ref "L451")
      (value "LED 3528")
      (footprint "LED-3528-GREEN")
      (description "Dán")
      (libsource (lib "Altium_Lib_by_KhueNguyenCreator") (part "LED 3528 Xanh La"))
    )
    (comp (ref "L452")
      (value "LED 3528")
      (footprint "LED-3528-GREEN")
      (description "Dán")
      (libsource (lib "Altium_Lib_by_KhueNguyenCreator") (part "LED 3528 Xanh La"))
    )
    (comp (ref "L453")
      (value "LED 3528")
      (footprint "LED-3528-GREEN")
      (description "Dán")
      (libsource (lib "Altium_Lib_by_KhueNguyenCreator") (part "LED 3528 Xanh La"))
    )
    (comp (ref "L454")
      (value "LED 3528")
      (footprint "LED-3528-GREEN")
      (description "Dán")
      (libsource (lib "Altium_Lib_by_KhueNguyenCreator") (part "LED 3528 Xanh La"))
    )
    (comp (ref "L455")
      (value "LED 3528")
      (footprint "LED-3528-GREEN")
      (description "Dán")
      (libsource (lib "Altium_Lib_by_KhueNguyenCreator") (part "LED 3528 Xanh La"))
    )
    (comp (ref "L456")
      (value "LED 3528")
      (footprint "LED-3528-GREEN")
      (description "Dán")
      (libsource (lib "Altium_Lib_by_KhueNguyenCreator") (part "LED 3528 Xanh La"))
    )
    (comp (ref "L457")
      (value "LED 3528")
      (footprint "LED-3528-GREEN")
      (description "Dán")
      (libsource (lib "Altium_Lib_by_KhueNguyenCreator") (part "LED 3528 Xanh La"))
    )
    (comp (ref "L458")
      (value "LED 3528")
      (footprint "LED-3528-GREEN")
      (description "Dán")
      (libsource (lib "Altium_Lib_by_KhueNguyenCreator") (part "LED 3528 Xanh La"))
    )
    (comp (ref "L459")
      (value "LED 3528")
      (footprint "LED-3528-GREEN")
      (description "Dán")
      (libsource (lib "Altium_Lib_by_KhueNguyenCreator") (part "LED 3528 Xanh La"))
    )
    (comp (ref "L460")
      (value "LED 3528")
      (footprint "LED-3528-GREEN")
      (description "Dán")
      (libsource (lib "Altium_Lib_by_KhueNguyenCreator") (part "LED 3528 Xanh La"))
    )
    (comp (ref "L461")
      (value "LED 3528")
      (footprint "LED-3528-GREEN")
      (description "Dán")
      (libsource (lib "Altium_Lib_by_KhueNguyenCreator") (part "LED 3528 Xanh La"))
    )
    (comp (ref "L462")
      (value "LED 3528")
      (footprint "LED-3528-GREEN")
      (description "Dán")
      (libsource (lib "Altium_Lib_by_KhueNguyenCreator") (part "LED 3528 Xanh La"))
    )
    (comp (ref "L463")
      (value "LED 3528")
      (footprint "LED-3528-GREEN")
      (description "Dán")
      (libsource (lib "Altium_Lib_by_KhueNguyenCreator") (part "LED 3528 Xanh La"))
    )
    (comp (ref "L464")
      (value "LED 3528")
      (footprint "LED-3528-GREEN")
      (description "Dán")
      (libsource (lib "Altium_Lib_by_KhueNguyenCreator") (part "LED 3528 Xanh La"))
    )
    (comp (ref "L465")
      (value "LED 3528")
      (footprint "LED-3528-GREEN")
      (description "Dán")
      (libsource (lib "Altium_Lib_by_KhueNguyenCreator") (part "LED 3528 Xanh La"))
    )
    (comp (ref "L466")
      (value "LED 3528")
      (footprint "LED-3528-GREEN")
      (description "Dán")
      (libsource (lib "Altium_Lib_by_KhueNguyenCreator") (part "LED 3528 Xanh La"))
    )
    (comp (ref "L467")
      (value "LED 3528")
      (footprint "LED-3528-GREEN")
      (description "Dán")
      (libsource (lib "Altium_Lib_by_KhueNguyenCreator") (part "LED 3528 Xanh La"))
    )
    (comp (ref "L468")
      (value "LED 3528")
      (footprint "LED-3528-GREEN")
      (description "Dán")
      (libsource (lib "Altium_Lib_by_KhueNguyenCreator") (part "LED 3528 Xanh La"))
    )
    (comp (ref "L469")
      (value "LED 3528")
      (footprint "LED-3528-GREEN")
      (description "Dán")
      (libsource (lib "Altium_Lib_by_KhueNguyenCreator") (part "LED 3528 Xanh La"))
    )
    (comp (ref "L470")
      (value "LED 3528")
      (footprint "LED-3528-GREEN")
      (description "Dán")
      (libsource (lib "Altium_Lib_by_KhueNguyenCreator") (part "LED 3528 Xanh La"))
    )
    (comp (ref "L471")
      (value "LED 3528")
      (footprint "LED-3528-GREEN")
      (description "Dán")
      (libsource (lib "Altium_Lib_by_KhueNguyenCreator") (part "LED 3528 Xanh La"))
    )
    (comp (ref "L472")
      (value "LED 3528")
      (footprint "LED-3528-GREEN")
      (description "Dán")
      (libsource (lib "Altium_Lib_by_KhueNguyenCreator") (part "LED 3528 Xanh La"))
    )
    (comp (ref "L473")
      (value "LED 3528")
      (footprint "LED-3528-GREEN")
      (description "Dán")
      (libsource (lib "Altium_Lib_by_KhueNguyenCreator") (part "LED 3528 Xanh La"))
    )
    (comp (ref "L474")
      (value "LED 3528")
      (footprint "LED-3528-GREEN")
      (description "Dán")
      (libsource (lib "Altium_Lib_by_KhueNguyenCreator") (part "LED 3528 Xanh La"))
    )
    (comp (ref "L475")
      (value "LED 3528")
      (footprint "LED-3528-GREEN")
      (description "Dán")
      (libsource (lib "Altium_Lib_by_KhueNguyenCreator") (part "LED 3528 Xanh La"))
    )
    (comp (ref "L476")
      (value "LED 3528")
      (footprint "LED-3528-GREEN")
      (description "Dán")
      (libsource (lib "Altium_Lib_by_KhueNguyenCreator") (part "LED 3528 Xanh La"))
    )
    (comp (ref "L477")
      (value "LED 3528")
      (footprint "LED-3528-GREEN")
      (description "Dán")
      (libsource (lib "Altium_Lib_by_KhueNguyenCreator") (part "LED 3528 Xanh La"))
    )
    (comp (ref "L478")
      (value "LED 3528")
      (footprint "LED-3528-GREEN")
      (description "Dán")
      (libsource (lib "Altium_Lib_by_KhueNguyenCreator") (part "LED 3528 Xanh La"))
    )
    (comp (ref "L479")
      (value "LED 3528")
      (footprint "LED-3528-GREEN")
      (description "Dán")
      (libsource (lib "Altium_Lib_by_KhueNguyenCreator") (part "LED 3528 Xanh La"))
    )
    (comp (ref "L480")
      (value "LED 3528")
      (footprint "LED-3528-GREEN")
      (description "Dán")
      (libsource (lib "Altium_Lib_by_KhueNguyenCreator") (part "LED 3528 Xanh La"))
    )
    (comp (ref "L481")
      (value "LED 3528")
      (footprint "LED-3528-GREEN")
      (description "Dán")
      (libsource (lib "Altium_Lib_by_KhueNguyenCreator") (part "LED 3528 Xanh La"))
    )
    (comp (ref "L482")
      (value "LED 3528")
      (footprint "LED-3528-GREEN")
      (description "Dán")
      (libsource (lib "Altium_Lib_by_KhueNguyenCreator") (part "LED 3528 Xanh La"))
    )
    (comp (ref "L483")
      (value "LED 3528")
      (footprint "LED-3528-GREEN")
      (description "Dán")
      (libsource (lib "Altium_Lib_by_KhueNguyenCreator") (part "LED 3528 Xanh La"))
    )
    (comp (ref "L484")
      (value "LED 3528")
      (footprint "LED-3528-GREEN")
      (description "Dán")
      (libsource (lib "Altium_Lib_by_KhueNguyenCreator") (part "LED 3528 Xanh La"))
    )
    (comp (ref "L485")
      (value "LED 3528")
      (footprint "LED-3528-GREEN")
      (description "Dán")
      (libsource (lib "Altium_Lib_by_KhueNguyenCreator") (part "LED 3528 Xanh La"))
    )
    (comp (ref "L486")
      (value "LED 3528")
      (footprint "LED-3528-GREEN")
      (description "Dán")
      (libsource (lib "Altium_Lib_by_KhueNguyenCreator") (part "LED 3528 Xanh La"))
    )
    (comp (ref "L487")
      (value "LED 3528")
      (footprint "LED-3528-GREEN")
      (description "Dán")
      (libsource (lib "Altium_Lib_by_KhueNguyenCreator") (part "LED 3528 Xanh La"))
    )
    (comp (ref "L488")
      (value "LED 3528")
      (footprint "LED-3528-GREEN")
      (description "Dán")
      (libsource (lib "Altium_Lib_by_KhueNguyenCreator") (part "LED 3528 Xanh La"))
    )
    (comp (ref "L489")
      (value "LED 3528")
      (footprint "LED-3528-GREEN")
      (description "Dán")
      (libsource (lib "Altium_Lib_by_KhueNguyenCreator") (part "LED 3528 Xanh La"))
    )
    (comp (ref "L490")
      (value "LED 3528")
      (footprint "LED-3528-GREEN")
      (description "Dán")
      (libsource (lib "Altium_Lib_by_KhueNguyenCreator") (part "LED 3528 Xanh La"))
    )
    (comp (ref "L491")
      (value "LED 3528")
      (footprint "LED-3528-GREEN")
      (description "Dán")
      (libsource (lib "Altium_Lib_by_KhueNguyenCreator") (part "LED 3528 Xanh La"))
    )
    (comp (ref "L492")
      (value "LED 3528")
      (footprint "LED-3528-GREEN")
      (description "Dán")
      (libsource (lib "Altium_Lib_by_KhueNguyenCreator") (part "LED 3528 Xanh La"))
    )
    (comp (ref "L493")
      (value "LED 3528")
      (footprint "LED-3528-GREEN")
      (description "Dán")
      (libsource (lib "Altium_Lib_by_KhueNguyenCreator") (part "LED 3528 Xanh La"))
    )
    (comp (ref "L494")
      (value "LED 3528")
      (footprint "LED-3528-GREEN")
      (description "Dán")
      (libsource (lib "Altium_Lib_by_KhueNguyenCreator") (part "LED 3528 Xanh La"))
    )
    (comp (ref "L495")
      (value "LED 3528")
      (footprint "LED-3528-GREEN")
      (description "Dán")
      (libsource (lib "Altium_Lib_by_KhueNguyenCreator") (part "LED 3528 Xanh La"))
    )
    (comp (ref "L496")
      (value "LED 3528")
      (footprint "LED-3528-GREEN")
      (description "Dán")
      (libsource (lib "Altium_Lib_by_KhueNguyenCreator") (part "LED 3528 Xanh La"))
    )
    (comp (ref "L497")
      (value "LED 3528")
      (footprint "LED-3528-GREEN")
      (description "Dán")
      (libsource (lib "Altium_Lib_by_KhueNguyenCreator") (part "LED 3528 Xanh La"))
    )
    (comp (ref "L498")
      (value "LED 3528")
      (footprint "LED-3528-GREEN")
      (description "Dán")
      (libsource (lib "Altium_Lib_by_KhueNguyenCreator") (part "LED 3528 Xanh La"))
    )
    (comp (ref "L499")
      (value "LED 3528")
      (footprint "LED-3528-GREEN")
      (description "Dán")
      (libsource (lib "Altium_Lib_by_KhueNguyenCreator") (part "LED 3528 Xanh La"))
    )
    (comp (ref "L500")
      (value "LED 3528")
      (footprint "LED-3528-GREEN")
      (description "Dán")
      (libsource (lib "Altium_Lib_by_KhueNguyenCreator") (part "LED 3528 Xanh La"))
    )
    (comp (ref "L501")
      (value "LED 3528")
      (footprint "LED-3528-GREEN")
      (description "Dán")
      (libsource (lib "Altium_Lib_by_KhueNguyenCreator") (part "LED 3528 Xanh La"))
    )
    (comp (ref "L502")
      (value "LED 3528")
      (footprint "LED-3528-GREEN")
      (description "Dán")
      (libsource (lib "Altium_Lib_by_KhueNguyenCreator") (part "LED 3528 Xanh La"))
    )
    (comp (ref "L503")
      (value "LED 3528")
      (footprint "LED-3528-GREEN")
      (description "Dán")
      (libsource (lib "Altium_Lib_by_KhueNguyenCreator") (part "LED 3528 Xanh La"))
    )
    (comp (ref "L504")
      (value "LED 3528")
      (footprint "LED-3528-GREEN")
      (description "Dán")
      (libsource (lib "Altium_Lib_by_KhueNguyenCreator") (part "LED 3528 Xanh La"))
    )
    (comp (ref "L505")
      (value "LED 3528")
      (footprint "LED-3528-GREEN")
      (description "Dán")
      (libsource (lib "Altium_Lib_by_KhueNguyenCreator") (part "LED 3528 Xanh La"))
    )
    (comp (ref "L506")
      (value "LED 3528")
      (footprint "LED-3528-GREEN")
      (description "Dán")
      (libsource (lib "Altium_Lib_by_KhueNguyenCreator") (part "LED 3528 Xanh La"))
    )
    (comp (ref "L507")
      (value "LED 3528")
      (footprint "LED-3528-GREEN")
      (description "Dán")
      (libsource (lib "Altium_Lib_by_KhueNguyenCreator") (part "LED 3528 Xanh La"))
    )
    (comp (ref "L508")
      (value "LED 3528")
      (footprint "LED-3528-GREEN")
      (description "Dán")
      (libsource (lib "Altium_Lib_by_KhueNguyenCreator") (part "LED 3528 Xanh La"))
    )
    (comp (ref "L509")
      (value "LED 3528")
      (footprint "LED-3528-GREEN")
      (description "Dán")
      (libsource (lib "Altium_Lib_by_KhueNguyenCreator") (part "LED 3528 Xanh La"))
    )
    (comp (ref "L510")
      (value "LED 3528")
      (footprint "LED-3528-GREEN")
      (description "Dán")
      (libsource (lib "Altium_Lib_by_KhueNguyenCreator") (part "LED 3528 Xanh La"))
    )
    (comp (ref "L511")
      (value "LED 3528")
      (footprint "LED-3528-GREEN")
      (description "Dán")
      (libsource (lib "Altium_Lib_by_KhueNguyenCreator") (part "LED 3528 Xanh La"))
    )
    (comp (ref "L512")
      (value "LED 3528")
      (footprint "LED-3528-GREEN")
      (description "Dán")
      (libsource (lib "Altium_Lib_by_KhueNguyenCreator") (part "LED 3528 Xanh La"))
    )
    (comp (ref "L513")
      (value "LED 3528")
      (footprint "LED-3528-GREEN")
      (description "Dán")
      (libsource (lib "Altium_Lib_by_KhueNguyenCreator") (part "LED 3528 Xanh La"))
    )
    (comp (ref "L514")
      (value "LED 3528")
      (footprint "LED-3528-GREEN")
      (description "Dán")
      (libsource (lib "Altium_Lib_by_KhueNguyenCreator") (part "LED 3528 Xanh La"))
    )
    (comp (ref "L515")
      (value "LED 3528")
      (footprint "LED-3528-GREEN")
      (description "Dán")
      (libsource (lib "Altium_Lib_by_KhueNguyenCreator") (part "LED 3528 Xanh La"))
    )
    (comp (ref "L516")
      (value "LED 3528")
      (footprint "LED-3528-GREEN")
      (description "Dán")
      (libsource (lib "Altium_Lib_by_KhueNguyenCreator") (part "LED 3528 Xanh La"))
    )
    (comp (ref "L517")
      (value "LED 3528")
      (footprint "LED-3528-GREEN")
      (description "Dán")
      (libsource (lib "Altium_Lib_by_KhueNguyenCreator") (part "LED 3528 Xanh La"))
    )
    (comp (ref "L518")
      (value "LED 3528")
      (footprint "LED-3528-GREEN")
      (description "Dán")
      (libsource (lib "Altium_Lib_by_KhueNguyenCreator") (part "LED 3528 Xanh La"))
    )
    (comp (ref "L519")
      (value "LED 3528")
      (footprint "LED-3528-GREEN")
      (description "Dán")
      (libsource (lib "Altium_Lib_by_KhueNguyenCreator") (part "LED 3528 Xanh La"))
    )
    (comp (ref "L520")
      (value "LED 3528")
      (footprint "LED-3528-GREEN")
      (description "Dán")
      (libsource (lib "Altium_Lib_by_KhueNguyenCreator") (part "LED 3528 Xanh La"))
    )
    (comp (ref "L521")
      (value "LED 3528")
      (footprint "LED-3528-GREEN")
      (description "Dán")
      (libsource (lib "Altium_Lib_by_KhueNguyenCreator") (part "LED 3528 Xanh La"))
    )
    (comp (ref "L522")
      (value "LED 3528")
      (footprint "LED-3528-GREEN")
      (description "Dán")
      (libsource (lib "Altium_Lib_by_KhueNguyenCreator") (part "LED 3528 Xanh La"))
    )
  )
  (nets
    (net (code "1") (name "/A") (class "Default")
      (node (ref "L10") (pin "1") (pinfunction "A_1") (pintype "passive"))
      (node (ref "L11") (pin "1") (pinfunction "A_1") (pintype "passive"))
      (node (ref "L12") (pin "1") (pinfunction "A_1") (pintype "passive"))
      (node (ref "L13") (pin "1") (pinfunction "A_1") (pintype "passive"))
      (node (ref "L14") (pin "1") (pinfunction "A_1") (pintype "passive"))
      (node (ref "L15") (pin "1") (pinfunction "A_1") (pintype "passive"))
      (node (ref "L16") (pin "1") (pinfunction "A_1") (pintype "passive"))
      (node (ref "L17") (pin "1") (pinfunction "A_1") (pintype "passive"))
      (node (ref "L18") (pin "1") (pinfunction "A_1") (pintype "passive"))
      (node (ref "L19") (pin "1") (pinfunction "A_1") (pintype "passive"))
      (node (ref "L20") (pin "1") (pinfunction "A_1") (pintype "passive"))
      (node (ref "L6") (pin "1") (pinfunction "A_1") (pintype "passive"))
      (node (ref "L7") (pin "1") (pinfunction "A_1") (pintype "passive"))
      (node (ref "L8") (pin "1") (pinfunction "A_1") (pintype "passive"))
      (node (ref "L9") (pin "1") (pinfunction "A_1") (pintype "passive"))
    )
    (net (code "2") (name "/A1") (class "Default")
      (node (ref "L175") (pin "1") (pinfunction "A_1") (pintype "passive"))
      (node (ref "L176") (pin "1") (pinfunction "A_1") (pintype "passive"))
      (node (ref "L177") (pin "1") (pinfunction "A_1") (pintype "passive"))
      (node (ref "L178") (pin "1") (pinfunction "A_1") (pintype "passive"))
      (node (ref "L179") (pin "1") (pinfunction "A_1") (pintype "passive"))
      (node (ref "L180") (pin "1") (pinfunction "A_1") (pintype "passive"))
      (node (ref "L181") (pin "1") (pinfunction "A_1") (pintype "passive"))
      (node (ref "L182") (pin "1") (pinfunction "A_1") (pintype "passive"))
      (node (ref "L183") (pin "1") (pinfunction "A_1") (pintype "passive"))
      (node (ref "L184") (pin "1") (pinfunction "A_1") (pintype "passive"))
      (node (ref "L185") (pin "1") (pinfunction "A_1") (pintype "passive"))
      (node (ref "L186") (pin "1") (pinfunction "A_1") (pintype "passive"))
      (node (ref "L187") (pin "1") (pinfunction "A_1") (pintype "passive"))
      (node (ref "L188") (pin "1") (pinfunction "A_1") (pintype "passive"))
      (node (ref "L189") (pin "1") (pinfunction "A_1") (pintype "passive"))
      (node (ref "L190") (pin "1") (pinfunction "A_1") (pintype "passive"))
      (node (ref "L191") (pin "1") (pinfunction "A_1") (pintype "passive"))
      (node (ref "L192") (pin "1") (pinfunction "A_1") (pintype "passive"))
    )
    (net (code "3") (name "/A2") (class "Default")
      (node (ref "L349") (pin "1") (pinfunction "A_1") (pintype "passive"))
      (node (ref "L350") (pin "1") (pinfunction "A_1") (pintype "passive"))
      (node (ref "L351") (pin "1") (pinfunction "A_1") (pintype "passive"))
      (node (ref "L352") (pin "1") (pinfunction "A_1") (pintype "passive"))
      (node (ref "L353") (pin "1") (pinfunction "A_1") (pintype "passive"))
      (node (ref "L354") (pin "1") (pinfunction "A_1") (pintype "passive"))
      (node (ref "L355") (pin "1") (pinfunction "A_1") (pintype "passive"))
      (node (ref "L356") (pin "1") (pinfunction "A_1") (pintype "passive"))
      (node (ref "L357") (pin "1") (pinfunction "A_1") (pintype "passive"))
      (node (ref "L358") (pin "1") (pinfunction "A_1") (pintype "passive"))
      (node (ref "L359") (pin "1") (pinfunction "A_1") (pintype "passive"))
      (node (ref "L360") (pin "1") (pinfunction "A_1") (pintype "passive"))
      (node (ref "L361") (pin "1") (pinfunction "A_1") (pintype "passive"))
      (node (ref "L362") (pin "1") (pinfunction "A_1") (pintype "passive"))
      (node (ref "L363") (pin "1") (pinfunction "A_1") (pintype "passive"))
      (node (ref "L364") (pin "1") (pinfunction "A_1") (pintype "passive"))
      (node (ref "L365") (pin "1") (pinfunction "A_1") (pintype "passive"))
      (node (ref "L366") (pin "1") (pinfunction "A_1") (pintype "passive"))
    )
    (net (code "4") (name "/B") (class "Default")
      (node (ref "L22") (pin "1") (pinfunction "A_1") (pintype "passive"))
      (node (ref "L24") (pin "1") (pinfunction "A_1") (pintype "passive"))
      (node (ref "L26") (pin "1") (pinfunction "A_1") (pintype "passive"))
      (node (ref "L28") (pin "1") (pinfunction "A_1") (pintype "passive"))
      (node (ref "L30") (pin "1") (pinfunction "A_1") (pintype "passive"))
      (node (ref "L32") (pin "1") (pinfunction "A_1") (pintype "passive"))
      (node (ref "L34") (pin "1") (pinfunction "A_1") (pintype "passive"))
      (node (ref "L36") (pin "1") (pinfunction "A_1") (pintype "passive"))
      (node (ref "L38") (pin "1") (pinfunction "A_1") (pintype "passive"))
      (node (ref "L40") (pin "1") (pinfunction "A_1") (pintype "passive"))
      (node (ref "L42") (pin "1") (pinfunction "A_1") (pintype "passive"))
      (node (ref "L45") (pin "1") (pinfunction "A_1") (pintype "passive"))
      (node (ref "L48") (pin "1") (pinfunction "A_1") (pintype "passive"))
      (node (ref "L5") (pin "1") (pinfunction "A_1") (pintype "passive"))
      (node (ref "L51") (pin "1") (pinfunction "A_1") (pintype "passive"))
      (node (ref "L54") (pin "1") (pinfunction "A_1") (pintype "passive"))
      (node (ref "L57") (pin "1") (pinfunction "A_1") (pintype "passive"))
      (node (ref "L60") (pin "1") (pinfunction "A_1") (pintype "passive"))
      (node (ref "L62") (pin "1") (pinfunction "A_1") (pintype "passive"))
      (node (ref "L64") (pin "1") (pinfunction "A_1") (pintype "passive"))
      (node (ref "L66") (pin "1") (pinfunction "A_1") (pintype "passive"))
      (node (ref "L68") (pin "1") (pinfunction "A_1") (pintype "passive"))
      (node (ref "L70") (pin "1") (pinfunction "A_1") (pintype "passive"))
      (node (ref "L72") (pin "1") (pinfunction "A_1") (pintype "passive"))
    )
    (net (code "5") (name "/B1") (class "Default")
      (node (ref "L194") (pin "1") (pinfunction "A_1") (pintype "passive"))
      (node (ref "L196") (pin "1") (pinfunction "A_1") (pintype "passive"))
      (node (ref "L198") (pin "1") (pinfunction "A_1") (pintype "passive"))
      (node (ref "L200") (pin "1") (pinfunction "A_1") (pintype "passive"))
      (node (ref "L202") (pin "1") (pinfunction "A_1") (pintype "passive"))
      (node (ref "L204") (pin "1") (pinfunction "A_1") (pintype "passive"))
      (node (ref "L206") (pin "1") (pinfunction "A_1") (pintype "passive"))
      (node (ref "L208") (pin "1") (pinfunction "A_1") (pintype "passive"))
      (node (ref "L210") (pin "1") (pinfunction "A_1") (pintype "passive"))
      (node (ref "L212") (pin "1") (pinfunction "A_1") (pintype "passive"))
      (node (ref "L214") (pin "1") (pinfunction "A_1") (pintype "passive"))
      (node (ref "L216") (pin "1") (pinfunction "A_1") (pintype "passive"))
      (node (ref "L219") (pin "1") (pinfunction "A_1") (pintype "passive"))
      (node (ref "L222") (pin "1") (pinfunction "A_1") (pintype "passive"))
      (node (ref "L225") (pin "1") (pinfunction "A_1") (pintype "passive"))
      (node (ref "L228") (pin "1") (pinfunction "A_1") (pintype "passive"))
      (node (ref "L231") (pin "1") (pinfunction "A_1") (pintype "passive"))
      (node (ref "L234") (pin "1") (pinfunction "A_1") (pintype "passive"))
      (node (ref "L236") (pin "1") (pinfunction "A_1") (pintype "passive"))
      (node (ref "L238") (pin "1") (pinfunction "A_1") (pintype "passive"))
      (node (ref "L240") (pin "1") (pinfunction "A_1") (pintype "passive"))
      (node (ref "L242") (pin "1") (pinfunction "A_1") (pintype "passive"))
      (node (ref "L244") (pin "1") (pinfunction "A_1") (pintype "passive"))
      (node (ref "L246") (pin "1") (pinfunction "A_1") (pintype "passive"))
    )
    (net (code "6") (name "/B2") (class "Default")
      (node (ref "L368") (pin "1") (pinfunction "A_1") (pintype "passive"))
      (node (ref "L370") (pin "1") (pinfunction "A_1") (pintype "passive"))
      (node (ref "L372") (pin "1") (pinfunction "A_1") (pintype "passive"))
      (node (ref "L374") (pin "1") (pinfunction "A_1") (pintype "passive"))
      (node (ref "L376") (pin "1") (pinfunction "A_1") (pintype "passive"))
      (node (ref "L378") (pin "1") (pinfunction "A_1") (pintype "passive"))
      (node (ref "L380") (pin "1") (pinfunction "A_1") (pintype "passive"))
      (node (ref "L382") (pin "1") (pinfunction "A_1") (pintype "passive"))
      (node (ref "L384") (pin "1") (pinfunction "A_1") (pintype "passive"))
      (node (ref "L386") (pin "1") (pinfunction "A_1") (pintype "passive"))
      (node (ref "L388") (pin "1") (pinfunction "A_1") (pintype "passive"))
      (node (ref "L390") (pin "1") (pinfunction "A_1") (pintype "passive"))
      (node (ref "L393") (pin "1") (pinfunction "A_1") (pintype "passive"))
      (node (ref "L396") (pin "1") (pinfunction "A_1") (pintype "passive"))
      (node (ref "L399") (pin "1") (pinfunction "A_1") (pintype "passive"))
      (node (ref "L402") (pin "1") (pinfunction "A_1") (pintype "passive"))
      (node (ref "L405") (pin "1") (pinfunction "A_1") (pintype "passive"))
      (node (ref "L408") (pin "1") (pinfunction "A_1") (pintype "passive"))
      (node (ref "L410") (pin "1") (pinfunction "A_1") (pintype "passive"))
      (node (ref "L412") (pin "1") (pinfunction "A_1") (pintype "passive"))
      (node (ref "L414") (pin "1") (pinfunction "A_1") (pintype "passive"))
      (node (ref "L416") (pin "1") (pinfunction "A_1") (pintype "passive"))
      (node (ref "L418") (pin "1") (pinfunction "A_1") (pintype "passive"))
      (node (ref "L420") (pin "1") (pinfunction "A_1") (pintype "passive"))
    )
    (net (code "7") (name "/C") (class "Default")
      (node (ref "L100") (pin "1") (pinfunction "A_1") (pintype "passive"))
      (node (ref "L102") (pin "1") (pinfunction "A_1") (pintype "passive"))
      (node (ref "L104") (pin "1") (pinfunction "A_1") (pintype "passive"))
      (node (ref "L106") (pin "1") (pinfunction "A_1") (pintype "passive"))
      (node (ref "L108") (pin "1") (pinfunction "A_1") (pintype "passive"))
      (node (ref "L110") (pin "1") (pinfunction "A_1") (pintype "passive"))
      (node (ref "L112") (pin "1") (pinfunction "A_1") (pintype "passive"))
      (node (ref "L114") (pin "1") (pinfunction "A_1") (pintype "passive"))
      (node (ref "L117") (pin "1") (pinfunction "A_1") (pintype "passive"))
      (node (ref "L118") (pin "1") (pinfunction "A_1") (pintype "passive"))
      (node (ref "L121") (pin "1") (pinfunction "A_1") (pintype "passive"))
      (node (ref "L122") (pin "1") (pinfunction "A_1") (pintype "passive"))
      (node (ref "L125") (pin "1") (pinfunction "A_1") (pintype "passive"))
      (node (ref "L126") (pin "1") (pinfunction "A_1") (pintype "passive"))
      (node (ref "L129") (pin "1") (pinfunction "A_1") (pintype "passive"))
      (node (ref "L130") (pin "1") (pinfunction "A_1") (pintype "passive"))
      (node (ref "L133") (pin "1") (pinfunction "A_1") (pintype "passive"))
      (node (ref "L134") (pin "1") (pinfunction "A_1") (pintype "passive"))
      (node (ref "L137") (pin "1") (pinfunction "A_1") (pintype "passive"))
      (node (ref "L138") (pin "1") (pinfunction "A_1") (pintype "passive"))
      (node (ref "L140") (pin "1") (pinfunction "A_1") (pintype "passive"))
      (node (ref "L142") (pin "1") (pinfunction "A_1") (pintype "passive"))
      (node (ref "L144") (pin "1") (pinfunction "A_1") (pintype "passive"))
      (node (ref "L146") (pin "1") (pinfunction "A_1") (pintype "passive"))
      (node (ref "L148") (pin "1") (pinfunction "A_1") (pintype "passive"))
      (node (ref "L150") (pin "1") (pinfunction "A_1") (pintype "passive"))
      (node (ref "L77") (pin "1") (pinfunction "A_1") (pintype "passive"))
      (node (ref "L94") (pin "1") (pinfunction "A_1") (pintype "passive"))
      (node (ref "L96") (pin "1") (pinfunction "A_1") (pintype "passive"))
      (node (ref "L98") (pin "1") (pinfunction "A_1") (pintype "passive"))
    )
    (net (code "8") (name "/C1") (class "Default")
      (node (ref "L266") (pin "1") (pinfunction "A_1") (pintype "passive"))
      (node (ref "L268") (pin "1") (pinfunction "A_1") (pintype "passive"))
      (node (ref "L270") (pin "1") (pinfunction "A_1") (pintype "passive"))
      (node (ref "L272") (pin "1") (pinfunction "A_1") (pintype "passive"))
      (node (ref "L274") (pin "1") (pinfunction "A_1") (pintype "passive"))
      (node (ref "L276") (pin "1") (pinfunction "A_1") (pintype "passive"))
      (node (ref "L278") (pin "1") (pinfunction "A_1") (pintype "passive"))
      (node (ref "L280") (pin "1") (pinfunction "A_1") (pintype "passive"))
      (node (ref "L282") (pin "1") (pinfunction "A_1") (pintype "passive"))
      (node (ref "L284") (pin "1") (pinfunction "A_1") (pintype "passive"))
      (node (ref "L286") (pin "1") (pinfunction "A_1") (pintype "passive"))
      (node (ref "L288") (pin "1") (pinfunction "A_1") (pintype "passive"))
      (node (ref "L291") (pin "1") (pinfunction "A_1") (pintype "passive"))
      (node (ref "L292") (pin "1") (pinfunction "A_1") (pintype "passive"))
      (node (ref "L295") (pin "1") (pinfunction "A_1") (pintype "passive"))
      (node (ref "L296") (pin "1") (pinfunction "A_1") (pintype "passive"))
      (node (ref "L299") (pin "1") (pinfunction "A_1") (pintype "passive"))
      (node (ref "L300") (pin "1") (pinfunction "A_1") (pintype "passive"))
      (node (ref "L303") (pin "1") (pinfunction "A_1") (pintype "passive"))
      (node (ref "L304") (pin "1") (pinfunction "A_1") (pintype "passive"))
      (node (ref "L307") (pin "1") (pinfunction "A_1") (pintype "passive"))
      (node (ref "L308") (pin "1") (pinfunction "A_1") (pintype "passive"))
      (node (ref "L311") (pin "1") (pinfunction "A_1") (pintype "passive"))
      (node (ref "L312") (pin "1") (pinfunction "A_1") (pintype "passive"))
      (node (ref "L314") (pin "1") (pinfunction "A_1") (pintype "passive"))
      (node (ref "L316") (pin "1") (pinfunction "A_1") (pintype "passive"))
      (node (ref "L318") (pin "1") (pinfunction "A_1") (pintype "passive"))
      (node (ref "L320") (pin "1") (pinfunction "A_1") (pintype "passive"))
      (node (ref "L322") (pin "1") (pinfunction "A_1") (pintype "passive"))
      (node (ref "L324") (pin "1") (pinfunction "A_1") (pintype "passive"))
    )
    (net (code "9") (name "/C2") (class "Default")
      (node (ref "L440") (pin "1") (pinfunction "A_1") (pintype "passive"))
      (node (ref "L442") (pin "1") (pinfunction "A_1") (pintype "passive"))
      (node (ref "L444") (pin "1") (pinfunction "A_1") (pintype "passive"))
      (node (ref "L446") (pin "1") (pinfunction "A_1") (pintype "passive"))
      (node (ref "L448") (pin "1") (pinfunction "A_1") (pintype "passive"))
      (node (ref "L450") (pin "1") (pinfunction "A_1") (pintype "passive"))
      (node (ref "L452") (pin "1") (pinfunction "A_1") (pintype "passive"))
      (node (ref "L454") (pin "1") (pinfunction "A_1") (pintype "passive"))
      (node (ref "L456") (pin "1") (pinfunction "A_1") (pintype "passive"))
      (node (ref "L458") (pin "1") (pinfunction "A_1") (pintype "passive"))
      (node (ref "L460") (pin "1") (pinfunction "A_1") (pintype "passive"))
      (node (ref "L462") (pin "1") (pinfunction "A_1") (pintype "passive"))
      (node (ref "L465") (pin "1") (pinfunction "A_1") (pintype "passive"))
      (node (ref "L466") (pin "1") (pinfunction "A_1") (pintype "passive"))
      (node (ref "L469") (pin "1") (pinfunction "A_1") (pintype "passive"))
      (node (ref "L470") (pin "1") (pinfunction "A_1") (pintype "passive"))
      (node (ref "L473") (pin "1") (pinfunction "A_1") (pintype "passive"))
      (node (ref "L474") (pin "1") (pinfunction "A_1") (pintype "passive"))
      (node (ref "L477") (pin "1") (pinfunction "A_1") (pintype "passive"))
      (node (ref "L478") (pin "1") (pinfunction "A_1") (pintype "passive"))
      (node (ref "L481") (pin "1") (pinfunction "A_1") (pintype "passive"))
      (node (ref "L482") (pin "1") (pinfunction "A_1") (pintype "passive"))
      (node (ref "L485") (pin "1") (pinfunction "A_1") (pintype "passive"))
      (node (ref "L486") (pin "1") (pinfunction "A_1") (pintype "passive"))
      (node (ref "L488") (pin "1") (pinfunction "A_1") (pintype "passive"))
      (node (ref "L490") (pin "1") (pinfunction "A_1") (pintype "passive"))
      (node (ref "L492") (pin "1") (pinfunction "A_1") (pintype "passive"))
      (node (ref "L494") (pin "1") (pinfunction "A_1") (pintype "passive"))
      (node (ref "L496") (pin "1") (pinfunction "A_1") (pintype "passive"))
      (node (ref "L498") (pin "1") (pinfunction "A_1") (pintype "passive"))
    )
    (net (code "10") (name "/D") (class "Default")
      (node (ref "L157") (pin "1") (pinfunction "A_1") (pintype "passive"))
      (node (ref "L158") (pin "1") (pinfunction "A_1") (pintype "passive"))
      (node (ref "L159") (pin "1") (pinfunction "A_1") (pintype "passive"))
      (node (ref "L160") (pin "1") (pinfunction "A_1") (pintype "passive"))
      (node (ref "L161") (pin "1") (pinfunction "A_1") (pintype "passive"))
      (node (ref "L162") (pin "1") (pinfunction "A_1") (pintype "passive"))
      (node (ref "L163") (pin "1") (pinfunction "A_1") (pintype "passive"))
      (node (ref "L164") (pin "1") (pinfunction "A_1") (pintype "passive"))
      (node (ref "L165") (pin "1") (pinfunction "A_1") (pintype "passive"))
      (node (ref "L166") (pin "1") (pinfunction "A_1") (pintype "passive"))
      (node (ref "L167") (pin "1") (pinfunction "A_1") (pintype "passive"))
      (node (ref "L168") (pin "1") (pinfunction "A_1") (pintype "passive"))
      (node (ref "L169") (pin "1") (pinfunction "A_1") (pintype "passive"))
      (node (ref "L170") (pin "1") (pinfunction "A_1") (pintype "passive"))
      (node (ref "L171") (pin "1") (pinfunction "A_1") (pintype "passive"))
      (node (ref "L172") (pin "1") (pinfunction "A_1") (pintype "passive"))
      (node (ref "L173") (pin "1") (pinfunction "A_1") (pintype "passive"))
      (node (ref "L174") (pin "1") (pinfunction "A_1") (pintype "passive"))
    )
    (net (code "11") (name "/D1") (class "Default")
      (node (ref "L331") (pin "1") (pinfunction "A_1") (pintype "passive"))
      (node (ref "L332") (pin "1") (pinfunction "A_1") (pintype "passive"))
      (node (ref "L333") (pin "1") (pinfunction "A_1") (pintype "passive"))
      (node (ref "L334") (pin "1") (pinfunction "A_1") (pintype "passive"))
      (node (ref "L335") (pin "1") (pinfunction "A_1") (pintype "passive"))
      (node (ref "L336") (pin "1") (pinfunction "A_1") (pintype "passive"))
      (node (ref "L337") (pin "1") (pinfunction "A_1") (pintype "passive"))
      (node (ref "L338") (pin "1") (pinfunction "A_1") (pintype "passive"))
      (node (ref "L339") (pin "1") (pinfunction "A_1") (pintype "passive"))
      (node (ref "L340") (pin "1") (pinfunction "A_1") (pintype "passive"))
      (node (ref "L341") (pin "1") (pinfunction "A_1") (pintype "passive"))
      (node (ref "L342") (pin "1") (pinfunction "A_1") (pintype "passive"))
      (node (ref "L343") (pin "1") (pinfunction "A_1") (pintype "passive"))
      (node (ref "L344") (pin "1") (pinfunction "A_1") (pintype "passive"))
      (node (ref "L345") (pin "1") (pinfunction "A_1") (pintype "passive"))
      (node (ref "L346") (pin "1") (pinfunction "A_1") (pintype "passive"))
      (node (ref "L347") (pin "1") (pinfunction "A_1") (pintype "passive"))
      (node (ref "L348") (pin "1") (pinfunction "A_1") (pintype "passive"))
    )
    (net (code "12") (name "/D2") (class "Default")
      (node (ref "L505") (pin "1") (pinfunction "A_1") (pintype "passive"))
      (node (ref "L506") (pin "1") (pinfunction "A_1") (pintype "passive"))
      (node (ref "L507") (pin "1") (pinfunction "A_1") (pintype "passive"))
      (node (ref "L508") (pin "1") (pinfunction "A_1") (pintype "passive"))
      (node (ref "L509") (pin "1") (pinfunction "A_1") (pintype "passive"))
      (node (ref "L510") (pin "1") (pinfunction "A_1") (pintype "passive"))
      (node (ref "L511") (pin "1") (pinfunction "A_1") (pintype "passive"))
      (node (ref "L512") (pin "1") (pinfunction "A_1") (pintype "passive"))
      (node (ref "L513") (pin "1") (pinfunction "A_1") (pintype "passive"))
      (node (ref "L514") (pin "1") (pinfunction "A_1") (pintype "passive"))
      (node (ref "L515") (pin "1") (pinfunction "A_1") (pintype "passive"))
      (node (ref "L516") (pin "1") (pinfunction "A_1") (pintype "passive"))
      (node (ref "L517") (pin "1") (pinfunction "A_1") (pintype "passive"))
      (node (ref "L518") (pin "1") (pinfunction "A_1") (pintype "passive"))
      (node (ref "L519") (pin "1") (pinfunction "A_1") (pintype "passive"))
      (node (ref "L520") (pin "1") (pinfunction "A_1") (pintype "passive"))
      (node (ref "L521") (pin "1") (pinfunction "A_1") (pintype "passive"))
      (node (ref "L522") (pin "1") (pinfunction "A_1") (pintype "passive"))
    )
    (net (code "13") (name "/E") (class "Default")
      (node (ref "L101") (pin "1") (pinfunction "A_1") (pintype "passive"))
      (node (ref "L103") (pin "1") (pinfunction "A_1") (pintype "passive"))
      (node (ref "L105") (pin "1") (pinfunction "A_1") (pintype "passive"))
      (node (ref "L107") (pin "1") (pinfunction "A_1") (pintype "passive"))
      (node (ref "L109") (pin "1") (pinfunction "A_1") (pintype "passive"))
      (node (ref "L111") (pin "1") (pinfunction "A_1") (pintype "passive"))
      (node (ref "L113") (pin "1") (pinfunction "A_1") (pintype "passive"))
      (node (ref "L115") (pin "1") (pinfunction "A_1") (pintype "passive"))
      (node (ref "L116") (pin "1") (pinfunction "A_1") (pintype "passive"))
      (node (ref "L119") (pin "1") (pinfunction "A_1") (pintype "passive"))
      (node (ref "L120") (pin "1") (pinfunction "A_1") (pintype "passive"))
      (node (ref "L123") (pin "1") (pinfunction "A_1") (pintype "passive"))
      (node (ref "L124") (pin "1") (pinfunction "A_1") (pintype "passive"))
      (node (ref "L127") (pin "1") (pinfunction "A_1") (pintype "passive"))
      (node (ref "L128") (pin "1") (pinfunction "A_1") (pintype "passive"))
      (node (ref "L131") (pin "1") (pinfunction "A_1") (pintype "passive"))
      (node (ref "L132") (pin "1") (pinfunction "A_1") (pintype "passive"))
      (node (ref "L135") (pin "1") (pinfunction "A_1") (pintype "passive"))
      (node (ref "L136") (pin "1") (pinfunction "A_1") (pintype "passive"))
      (node (ref "L139") (pin "1") (pinfunction "A_1") (pintype "passive"))
      (node (ref "L141") (pin "1") (pinfunction "A_1") (pintype "passive"))
      (node (ref "L143") (pin "1") (pinfunction "A_1") (pintype "passive"))
      (node (ref "L145") (pin "1") (pinfunction "A_1") (pintype "passive"))
      (node (ref "L147") (pin "1") (pinfunction "A_1") (pintype "passive"))
      (node (ref "L149") (pin "1") (pinfunction "A_1") (pintype "passive"))
      (node (ref "L76") (pin "1") (pinfunction "A_1") (pintype "passive"))
      (node (ref "L93") (pin "1") (pinfunction "A_1") (pintype "passive"))
      (node (ref "L95") (pin "1") (pinfunction "A_1") (pintype "passive"))
      (node (ref "L97") (pin "1") (pinfunction "A_1") (pintype "passive"))
      (node (ref "L99") (pin "1") (pinfunction "A_1") (pintype "passive"))
    )
    (net (code "14") (name "/E1") (class "Default")
      (node (ref "L265") (pin "1") (pinfunction "A_1") (pintype "passive"))
      (node (ref "L267") (pin "1") (pinfunction "A_1") (pintype "passive"))
      (node (ref "L269") (pin "1") (pinfunction "A_1") (pintype "passive"))
      (node (ref "L271") (pin "1") (pinfunction "A_1") (pintype "passive"))
      (node (ref "L273") (pin "1") (pinfunction "A_1") (pintype "passive"))
      (node (ref "L275") (pin "1") (pinfunction "A_1") (pintype "passive"))
      (node (ref "L277") (pin "1") (pinfunction "A_1") (pintype "passive"))
      (node (ref "L279") (pin "1") (pinfunction "A_1") (pintype "passive"))
      (node (ref "L281") (pin "1") (pinfunction "A_1") (pintype "passive"))
      (node (ref "L283") (pin "1") (pinfunction "A_1") (pintype "passive"))
      (node (ref "L285") (pin "1") (pinfunction "A_1") (pintype "passive"))
      (node (ref "L287") (pin "1") (pinfunction "A_1") (pintype "passive"))
      (node (ref "L289") (pin "1") (pinfunction "A_1") (pintype "passive"))
      (node (ref "L290") (pin "1") (pinfunction "A_1") (pintype "passive"))
      (node (ref "L293") (pin "1") (pinfunction "A_1") (pintype "passive"))
      (node (ref "L294") (pin "1") (pinfunction "A_1") (pintype "passive"))
      (node (ref "L297") (pin "1") (pinfunction "A_1") (pintype "passive"))
      (node (ref "L298") (pin "1") (pinfunction "A_1") (pintype "passive"))
      (node (ref "L301") (pin "1") (pinfunction "A_1") (pintype "passive"))
      (node (ref "L302") (pin "1") (pinfunction "A_1") (pintype "passive"))
      (node (ref "L305") (pin "1") (pinfunction "A_1") (pintype "passive"))
      (node (ref "L306") (pin "1") (pinfunction "A_1") (pintype "passive"))
      (node (ref "L309") (pin "1") (pinfunction "A_1") (pintype "passive"))
      (node (ref "L310") (pin "1") (pinfunction "A_1") (pintype "passive"))
      (node (ref "L313") (pin "1") (pinfunction "A_1") (pintype "passive"))
      (node (ref "L315") (pin "1") (pinfunction "A_1") (pintype "passive"))
      (node (ref "L317") (pin "1") (pinfunction "A_1") (pintype "passive"))
      (node (ref "L319") (pin "1") (pinfunction "A_1") (pintype "passive"))
      (node (ref "L321") (pin "1") (pinfunction "A_1") (pintype "passive"))
      (node (ref "L323") (pin "1") (pinfunction "A_1") (pintype "passive"))
    )
    (net (code "15") (name "/E2") (class "Default")
      (node (ref "L439") (pin "1") (pinfunction "A_1") (pintype "passive"))
      (node (ref "L441") (pin "1") (pinfunction "A_1") (pintype "passive"))
      (node (ref "L443") (pin "1") (pinfunction "A_1") (pintype "passive"))
      (node (ref "L445") (pin "1") (pinfunction "A_1") (pintype "passive"))
      (node (ref "L447") (pin "1") (pinfunction "A_1") (pintype "passive"))
      (node (ref "L449") (pin "1") (pinfunction "A_1") (pintype "passive"))
      (node (ref "L451") (pin "1") (pinfunction "A_1") (pintype "passive"))
      (node (ref "L453") (pin "1") (pinfunction "A_1") (pintype "passive"))
      (node (ref "L455") (pin "1") (pinfunction "A_1") (pintype "passive"))
      (node (ref "L457") (pin "1") (pinfunction "A_1") (pintype "passive"))
      (node (ref "L459") (pin "1") (pinfunction "A_1") (pintype "passive"))
      (node (ref "L461") (pin "1") (pinfunction "A_1") (pintype "passive"))
      (node (ref "L463") (pin "1") (pinfunction "A_1") (pintype "passive"))
      (node (ref "L464") (pin "1") (pinfunction "A_1") (pintype "passive"))
      (node (ref "L467") (pin "1") (pinfunction "A_1") (pintype "passive"))
      (node (ref "L468") (pin "1") (pinfunction "A_1") (pintype "passive"))
      (node (ref "L471") (pin "1") (pinfunction "A_1") (pintype "passive"))
      (node (ref "L472") (pin "1") (pinfunction "A_1") (pintype "passive"))
      (node (ref "L475") (pin "1") (pinfunction "A_1") (pintype "passive"))
      (node (ref "L476") (pin "1") (pinfunction "A_1") (pintype "passive"))
      (node (ref "L479") (pin "1") (pinfunction "A_1") (pintype "passive"))
      (node (ref "L480") (pin "1") (pinfunction "A_1") (pintype "passive"))
      (node (ref "L483") (pin "1") (pinfunction "A_1") (pintype "passive"))
      (node (ref "L484") (pin "1") (pinfunction "A_1") (pintype "passive"))
      (node (ref "L487") (pin "1") (pinfunction "A_1") (pintype "passive"))
      (node (ref "L489") (pin "1") (pinfunction "A_1") (pintype "passive"))
      (node (ref "L491") (pin "1") (pinfunction "A_1") (pintype "passive"))
      (node (ref "L493") (pin "1") (pinfunction "A_1") (pintype "passive"))
      (node (ref "L495") (pin "1") (pinfunction "A_1") (pintype "passive"))
      (node (ref "L497") (pin "1") (pinfunction "A_1") (pintype "passive"))
    )
    (net (code "16") (name "/F") (class "Default")
      (node (ref "L21") (pin "1") (pinfunction "A_1") (pintype "passive"))
      (node (ref "L23") (pin "1") (pinfunction "A_1") (pintype "passive"))
      (node (ref "L25") (pin "1") (pinfunction "A_1") (pintype "passive"))
      (node (ref "L27") (pin "1") (pinfunction "A_1") (pintype "passive"))
      (node (ref "L29") (pin "1") (pinfunction "A_1") (pintype "passive"))
      (node (ref "L31") (pin "1") (pinfunction "A_1") (pintype "passive"))
      (node (ref "L33") (pin "1") (pinfunction "A_1") (pintype "passive"))
      (node (ref "L35") (pin "1") (pinfunction "A_1") (pintype "passive"))
      (node (ref "L37") (pin "1") (pinfunction "A_1") (pintype "passive"))
      (node (ref "L39") (pin "1") (pinfunction "A_1") (pintype "passive"))
      (node (ref "L4") (pin "1") (pinfunction "A_1") (pintype "passive"))
      (node (ref "L41") (pin "1") (pinfunction "A_1") (pintype "passive"))
      (node (ref "L43") (pin "1") (pinfunction "A_1") (pintype "passive"))
      (node (ref "L44") (pin "1") (pinfunction "A_1") (pintype "passive"))
      (node (ref "L46") (pin "1") (pinfunction "A_1") (pintype "passive"))
      (node (ref "L47") (pin "1") (pinfunction "A_1") (pintype "passive"))
      (node (ref "L49") (pin "1") (pinfunction "A_1") (pintype "passive"))
      (node (ref "L50") (pin "1") (pinfunction "A_1") (pintype "passive"))
      (node (ref "L52") (pin "1") (pinfunction "A_1") (pintype "passive"))
      (node (ref "L53") (pin "1") (pinfunction "A_1") (pintype "passive"))
      (node (ref "L55") (pin "1") (pinfunction "A_1") (pintype "passive"))
      (node (ref "L56") (pin "1") (pinfunction "A_1") (pintype "passive"))
      (node (ref "L58") (pin "1") (pinfunction "A_1") (pintype "passive"))
      (node (ref "L59") (pin "1") (pinfunction "A_1") (pintype "passive"))
      (node (ref "L61") (pin "1") (pinfunction "A_1") (pintype "passive"))
      (node (ref "L63") (pin "1") (pinfunction "A_1") (pintype "passive"))
      (node (ref "L65") (pin "1") (pinfunction "A_1") (pintype "passive"))
      (node (ref "L67") (pin "1") (pinfunction "A_1") (pintype "passive"))
      (node (ref "L69") (pin "1") (pinfunction "A_1") (pintype "passive"))
      (node (ref "L71") (pin "1") (pinfunction "A_1") (pintype "passive"))
    )
    (net (code "17") (name "/F1") (class "Default")
      (node (ref "L193") (pin "1") (pinfunction "A_1") (pintype "passive"))
      (node (ref "L195") (pin "1") (pinfunction "A_1") (pintype "passive"))
      (node (ref "L197") (pin "1") (pinfunction "A_1") (pintype "passive"))
      (node (ref "L199") (pin "1") (pinfunction "A_1") (pintype "passive"))
      (node (ref "L201") (pin "1") (pinfunction "A_1") (pintype "passive"))
      (node (ref "L203") (pin "1") (pinfunction "A_1") (pintype "passive"))
      (node (ref "L205") (pin "1") (pinfunction "A_1") (pintype "passive"))
      (node (ref "L207") (pin "1") (pinfunction "A_1") (pintype "passive"))
      (node (ref "L209") (pin "1") (pinfunction "A_1") (pintype "passive"))
      (node (ref "L211") (pin "1") (pinfunction "A_1") (pintype "passive"))
      (node (ref "L213") (pin "1") (pinfunction "A_1") (pintype "passive"))
      (node (ref "L215") (pin "1") (pinfunction "A_1") (pintype "passive"))
      (node (ref "L217") (pin "1") (pinfunction "A_1") (pintype "passive"))
      (node (ref "L218") (pin "1") (pinfunction "A_1") (pintype "passive"))
      (node (ref "L220") (pin "1") (pinfunction "A_1") (pintype "passive"))
      (node (ref "L221") (pin "1") (pinfunction "A_1") (pintype "passive"))
      (node (ref "L223") (pin "1") (pinfunction "A_1") (pintype "passive"))
      (node (ref "L224") (pin "1") (pinfunction "A_1") (pintype "passive"))
      (node (ref "L226") (pin "1") (pinfunction "A_1") (pintype "passive"))
      (node (ref "L227") (pin "1") (pinfunction "A_1") (pintype "passive"))
      (node (ref "L229") (pin "1") (pinfunction "A_1") (pintype "passive"))
      (node (ref "L230") (pin "1") (pinfunction "A_1") (pintype "passive"))
      (node (ref "L232") (pin "1") (pinfunction "A_1") (pintype "passive"))
      (node (ref "L233") (pin "1") (pinfunction "A_1") (pintype "passive"))
      (node (ref "L235") (pin "1") (pinfunction "A_1") (pintype "passive"))
      (node (ref "L237") (pin "1") (pinfunction "A_1") (pintype "passive"))
      (node (ref "L239") (pin "1") (pinfunction "A_1") (pintype "passive"))
      (node (ref "L241") (pin "1") (pinfunction "A_1") (pintype "passive"))
      (node (ref "L243") (pin "1") (pinfunction "A_1") (pintype "passive"))
      (node (ref "L245") (pin "1") (pinfunction "A_1") (pintype "passive"))
    )
    (net (code "18") (name "/F2") (class "Default")
      (node (ref "L367") (pin "1") (pinfunction "A_1") (pintype "passive"))
      (node (ref "L369") (pin "1") (pinfunction "A_1") (pintype "passive"))
      (node (ref "L371") (pin "1") (pinfunction "A_1") (pintype "passive"))
      (node (ref "L373") (pin "1") (pinfunction "A_1") (pintype "passive"))
      (node (ref "L375") (pin "1") (pinfunction "A_1") (pintype "passive"))
      (node (ref "L377") (pin "1") (pinfunction "A_1") (pintype "passive"))
      (node (ref "L379") (pin "1") (pinfunction "A_1") (pintype "passive"))
      (node (ref "L381") (pin "1") (pinfunction "A_1") (pintype "passive"))
      (node (ref "L383") (pin "1") (pinfunction "A_1") (pintype "passive"))
      (node (ref "L385") (pin "1") (pinfunction "A_1") (pintype "passive"))
      (node (ref "L387") (pin "1") (pinfunction "A_1") (pintype "passive"))
      (node (ref "L389") (pin "1") (pinfunction "A_1") (pintype "passive"))
      (node (ref "L391") (pin "1") (pinfunction "A_1") (pintype "passive"))
      (node (ref "L392") (pin "1") (pinfunction "A_1") (pintype "passive"))
      (node (ref "L394") (pin "1") (pinfunction "A_1") (pintype "passive"))
      (node (ref "L395") (pin "1") (pinfunction "A_1") (pintype "passive"))
      (node (ref "L397") (pin "1") (pinfunction "A_1") (pintype "passive"))
      (node (ref "L398") (pin "1") (pinfunction "A_1") (pintype "passive"))
      (node (ref "L400") (pin "1") (pinfunction "A_1") (pintype "passive"))
      (node (ref "L401") (pin "1") (pinfunction "A_1") (pintype "passive"))
      (node (ref "L403") (pin "1") (pinfunction "A_1") (pintype "passive"))
      (node (ref "L404") (pin "1") (pinfunction "A_1") (pintype "passive"))
      (node (ref "L406") (pin "1") (pinfunction "A_1") (pintype "passive"))
      (node (ref "L407") (pin "1") (pinfunction "A_1") (pintype "passive"))
      (node (ref "L409") (pin "1") (pinfunction "A_1") (pintype "passive"))
      (node (ref "L411") (pin "1") (pinfunction "A_1") (pintype "passive"))
      (node (ref "L413") (pin "1") (pinfunction "A_1") (pintype "passive"))
      (node (ref "L415") (pin "1") (pinfunction "A_1") (pintype "passive"))
      (node (ref "L417") (pin "1") (pinfunction "A_1") (pintype "passive"))
      (node (ref "L419") (pin "1") (pinfunction "A_1") (pintype "passive"))
    )
    (net (code "19") (name "/G") (class "Default")
      (node (ref "L73") (pin "1") (pinfunction "A_1") (pintype "passive"))
      (node (ref "L74") (pin "1") (pinfunction "A_1") (pintype "passive"))
      (node (ref "L75") (pin "1") (pinfunction "A_1") (pintype "passive"))
      (node (ref "L78") (pin "1") (pinfunction "A_1") (pintype "passive"))
      (node (ref "L79") (pin "1") (pinfunction "A_1") (pintype "passive"))
      (node (ref "L80") (pin "1") (pinfunction "A_1") (pintype "passive"))
      (node (ref "L81") (pin "1") (pinfunction "A_1") (pintype "passive"))
      (node (ref "L82") (pin "1") (pinfunction "A_1") (pintype "passive"))
      (node (ref "L83") (pin "1") (pinfunction "A_1") (pintype "passive"))
      (node (ref "L84") (pin "1") (pinfunction "A_1") (pintype "passive"))
      (node (ref "L85") (pin "1") (pinfunction "A_1") (pintype "passive"))
      (node (ref "L86") (pin "1") (pinfunction "A_1") (pintype "passive"))
      (node (ref "L87") (pin "1") (pinfunction "A_1") (pintype "passive"))
      (node (ref "L88") (pin "1") (pinfunction "A_1") (pintype "passive"))
      (node (ref "L89") (pin "1") (pinfunction "A_1") (pintype "passive"))
      (node (ref "L90") (pin "1") (pinfunction "A_1") (pintype "passive"))
      (node (ref "L91") (pin "1") (pinfunction "A_1") (pintype "passive"))
      (node (ref "L92") (pin "1") (pinfunction "A_1") (pintype "passive"))
    )
    (net (code "20") (name "/G1") (class "Default")
      (node (ref "L247") (pin "1") (pinfunction "A_1") (pintype "passive"))
      (node (ref "L248") (pin "1") (pinfunction "A_1") (pintype "passive"))
      (node (ref "L249") (pin "1") (pinfunction "A_1") (pintype "passive"))
      (node (ref "L250") (pin "1") (pinfunction "A_1") (pintype "passive"))
      (node (ref "L251") (pin "1") (pinfunction "A_1") (pintype "passive"))
      (node (ref "L252") (pin "1") (pinfunction "A_1") (pintype "passive"))
      (node (ref "L253") (pin "1") (pinfunction "A_1") (pintype "passive"))
      (node (ref "L254") (pin "1") (pinfunction "A_1") (pintype "passive"))
      (node (ref "L255") (pin "1") (pinfunction "A_1") (pintype "passive"))
      (node (ref "L256") (pin "1") (pinfunction "A_1") (pintype "passive"))
      (node (ref "L257") (pin "1") (pinfunction "A_1") (pintype "passive"))
      (node (ref "L258") (pin "1") (pinfunction "A_1") (pintype "passive"))
      (node (ref "L259") (pin "1") (pinfunction "A_1") (pintype "passive"))
      (node (ref "L260") (pin "1") (pinfunction "A_1") (pintype "passive"))
      (node (ref "L261") (pin "1") (pinfunction "A_1") (pintype "passive"))
      (node (ref "L262") (pin "1") (pinfunction "A_1") (pintype "passive"))
      (node (ref "L263") (pin "1") (pinfunction "A_1") (pintype "passive"))
      (node (ref "L264") (pin "1") (pinfunction "A_1") (pintype "passive"))
    )
    (net (code "21") (name "/G2") (class "Default")
      (node (ref "L421") (pin "1") (pinfunction "A_1") (pintype "passive"))
      (node (ref "L422") (pin "1") (pinfunction "A_1") (pintype "passive"))
      (node (ref "L423") (pin "1") (pinfunction "A_1") (pintype "passive"))
      (node (ref "L424") (pin "1") (pinfunction "A_1") (pintype "passive"))
      (node (ref "L425") (pin "1") (pinfunction "A_1") (pintype "passive"))
      (node (ref "L426") (pin "1") (pinfunction "A_1") (pintype "passive"))
      (node (ref "L427") (pin "1") (pinfunction "A_1") (pintype "passive"))
      (node (ref "L428") (pin "1") (pinfunction "A_1") (pintype "passive"))
      (node (ref "L429") (pin "1") (pinfunction "A_1") (pintype "passive"))
      (node (ref "L430") (pin "1") (pinfunction "A_1") (pintype "passive"))
      (node (ref "L431") (pin "1") (pinfunction "A_1") (pintype "passive"))
      (node (ref "L432") (pin "1") (pinfunction "A_1") (pintype "passive"))
      (node (ref "L433") (pin "1") (pinfunction "A_1") (pintype "passive"))
      (node (ref "L434") (pin "1") (pinfunction "A_1") (pintype "passive"))
      (node (ref "L435") (pin "1") (pinfunction "A_1") (pintype "passive"))
      (node (ref "L436") (pin "1") (pinfunction "A_1") (pintype "passive"))
      (node (ref "L437") (pin "1") (pinfunction "A_1") (pintype "passive"))
      (node (ref "L438") (pin "1") (pinfunction "A_1") (pintype "passive"))
    )
    (net (code "22") (name "/H") (class "Default")
      (node (ref "L151") (pin "1") (pinfunction "A_1") (pintype "passive"))
      (node (ref "L152") (pin "1") (pinfunction "A_1") (pintype "passive"))
      (node (ref "L153") (pin "1") (pinfunction "A_1") (pintype "passive"))
      (node (ref "L154") (pin "1") (pinfunction "A_1") (pintype "passive"))
      (node (ref "L155") (pin "1") (pinfunction "A_1") (pintype "passive"))
      (node (ref "L156") (pin "1") (pinfunction "A_1") (pintype "passive"))
    )
    (net (code "23") (name "/H1") (class "Default")
      (node (ref "L325") (pin "1") (pinfunction "A_1") (pintype "passive"))
      (node (ref "L326") (pin "1") (pinfunction "A_1") (pintype "passive"))
      (node (ref "L327") (pin "1") (pinfunction "A_1") (pintype "passive"))
      (node (ref "L328") (pin "1") (pinfunction "A_1") (pintype "passive"))
      (node (ref "L329") (pin "1") (pinfunction "A_1") (pintype "passive"))
      (node (ref "L330") (pin "1") (pinfunction "A_1") (pintype "passive"))
    )
    (net (code "24") (name "/H2") (class "Default")
      (node (ref "L499") (pin "1") (pinfunction "A_1") (pintype "passive"))
      (node (ref "L500") (pin "1") (pinfunction "A_1") (pintype "passive"))
      (node (ref "L501") (pin "1") (pinfunction "A_1") (pintype "passive"))
      (node (ref "L502") (pin "1") (pinfunction "A_1") (pintype "passive"))
      (node (ref "L503") (pin "1") (pinfunction "A_1") (pintype "passive"))
      (node (ref "L504") (pin "1") (pinfunction "A_1") (pintype "passive"))
    )
    (net (code "25") (name "/LED3.2") (class "Default")
      (node (ref "L358") (pin "2") (pinfunction "K_2") (pintype "passive"))
      (node (ref "L359") (pin "2") (pinfunction "K_2") (pintype "passive"))
      (node (ref "L360") (pin "2") (pinfunction "K_2") (pintype "passive"))
      (node (ref "L373") (pin "2") (pinfunction "K_2") (pintype "passive"))
      (node (ref "L374") (pin "2") (pinfunction "K_2") (pintype "passive"))
      (node (ref "L385") (pin "2") (pinfunction "K_2") (pintype "passive"))
      (node (ref "L386") (pin "2") (pinfunction "K_2") (pintype "passive"))
      (node (ref "L400") (pin "2") (pinfunction "K_2") (pintype "passive"))
      (node (ref "L401") (pin "2") (pinfunction "K_2") (pintype "passive"))
      (node (ref "L402") (pin "2") (pinfunction "K_2") (pintype "passive"))
      (node (ref "L415") (pin "2") (pinfunction "K_2") (pintype "passive"))
      (node (ref "L416") (pin "2") (pinfunction "K_2") (pintype "passive"))
    )
    (net (code "26") (name "GND") (class "Default")
      (node (ref "L1") (pin "2") (pinfunction "K_2") (pintype "passive"))
      (node (ref "L10") (pin "2") (pinfunction "K_2") (pintype "passive"))
      (node (ref "L100") (pin "2") (pinfunction "K_2") (pintype "passive"))
      (node (ref "L101") (pin "2") (pinfunction "K_2") (pintype "passive"))
      (node (ref "L102") (pin "2") (pinfunction "K_2") (pintype "passive"))
      (node (ref "L103") (pin "2") (pinfunction "K_2") (pintype "passive"))
      (node (ref "L104") (pin "2") (pinfunction "K_2") (pintype "passive"))
      (node (ref "L105") (pin "2") (pinfunction "K_2") (pintype "passive"))
      (node (ref "L106") (pin "2") (pinfunction "K_2") (pintype "passive"))
      (node (ref "L107") (pin "2") (pinfunction "K_2") (pintype "passive"))
      (node (ref "L108") (pin "2") (pinfunction "K_2") (pintype "passive"))
      (node (ref "L109") (pin "2") (pinfunction "K_2") (pintype "passive"))
      (node (ref "L11") (pin "2") (pinfunction "K_2") (pintype "passive"))
      (node (ref "L110") (pin "2") (pinfunction "K_2") (pintype "passive"))
      (node (ref "L111") (pin "2") (pinfunction "K_2") (pintype "passive"))
      (node (ref "L112") (pin "2") (pinfunction "K_2") (pintype "passive"))
      (node (ref "L113") (pin "2") (pinfunction "K_2") (pintype "passive"))
      (node (ref "L114") (pin "2") (pinfunction "K_2") (pintype "passive"))
      (node (ref "L115") (pin "2") (pinfunction "K_2") (pintype "passive"))
      (node (ref "L116") (pin "2") (pinfunction "K_2") (pintype "passive"))
      (node (ref "L117") (pin "2") (pinfunction "K_2") (pintype "passive"))
      (node (ref "L118") (pin "2") (pinfunction "K_2") (pintype "passive"))
      (node (ref "L119") (pin "2") (pinfunction "K_2") (pintype "passive"))
      (node (ref "L12") (pin "2") (pinfunction "K_2") (pintype "passive"))
      (node (ref "L120") (pin "2") (pinfunction "K_2") (pintype "passive"))
      (node (ref "L121") (pin "2") (pinfunction "K_2") (pintype "passive"))
      (node (ref "L122") (pin "2") (pinfunction "K_2") (pintype "passive"))
      (node (ref "L123") (pin "2") (pinfunction "K_2") (pintype "passive"))
      (node (ref "L124") (pin "2") (pinfunction "K_2") (pintype "passive"))
      (node (ref "L125") (pin "2") (pinfunction "K_2") (pintype "passive"))
      (node (ref "L126") (pin "2") (pinfunction "K_2") (pintype "passive"))
      (node (ref "L127") (pin "2") (pinfunction "K_2") (pintype "passive"))
      (node (ref "L128") (pin "2") (pinfunction "K_2") (pintype "passive"))
      (node (ref "L129") (pin "2") (pinfunction "K_2") (pintype "passive"))
      (node (ref "L13") (pin "2") (pinfunction "K_2") (pintype "passive"))
      (node (ref "L130") (pin "2") (pinfunction "K_2") (pintype "passive"))
      (node (ref "L131") (pin "2") (pinfunction "K_2") (pintype "passive"))
      (node (ref "L132") (pin "2") (pinfunction "K_2") (pintype "passive"))
      (node (ref "L133") (pin "2") (pinfunction "K_2") (pintype "passive"))
      (node (ref "L134") (pin "2") (pinfunction "K_2") (pintype "passive"))
      (node (ref "L135") (pin "2") (pinfunction "K_2") (pintype "passive"))
      (node (ref "L136") (pin "2") (pinfunction "K_2") (pintype "passive"))
      (node (ref "L137") (pin "2") (pinfunction "K_2") (pintype "passive"))
      (node (ref "L138") (pin "2") (pinfunction "K_2") (pintype "passive"))
      (node (ref "L139") (pin "2") (pinfunction "K_2") (pintype "passive"))
      (node (ref "L14") (pin "2") (pinfunction "K_2") (pintype "passive"))
      (node (ref "L140") (pin "2") (pinfunction "K_2") (pintype "passive"))
      (node (ref "L141") (pin "2") (pinfunction "K_2") (pintype "passive"))
      (node (ref "L142") (pin "2") (pinfunction "K_2") (pintype "passive"))
      (node (ref "L143") (pin "2") (pinfunction "K_2") (pintype "passive"))
      (node (ref "L144") (pin "2") (pinfunction "K_2") (pintype "passive"))
      (node (ref "L145") (pin "2") (pinfunction "K_2") (pintype "passive"))
      (node (ref "L146") (pin "2") (pinfunction "K_2") (pintype "passive"))
      (node (ref "L147") (pin "2") (pinfunction "K_2") (pintype "passive"))
      (node (ref "L148") (pin "2") (pinfunction "K_2") (pintype "passive"))
      (node (ref "L149") (pin "2") (pinfunction "K_2") (pintype "passive"))
      (node (ref "L15") (pin "2") (pinfunction "K_2") (pintype "passive"))
      (node (ref "L150") (pin "2") (pinfunction "K_2") (pintype "passive"))
      (node (ref "L151") (pin "2") (pinfunction "K_2") (pintype "passive"))
      (node (ref "L152") (pin "2") (pinfunction "K_2") (pintype "passive"))
      (node (ref "L153") (pin "2") (pinfunction "K_2") (pintype "passive"))
      (node (ref "L154") (pin "2") (pinfunction "K_2") (pintype "passive"))
      (node (ref "L155") (pin "2") (pinfunction "K_2") (pintype "passive"))
      (node (ref "L156") (pin "2") (pinfunction "K_2") (pintype "passive"))
      (node (ref "L157") (pin "2") (pinfunction "K_2") (pintype "passive"))
      (node (ref "L158") (pin "2") (pinfunction "K_2") (pintype "passive"))
      (node (ref "L159") (pin "2") (pinfunction "K_2") (pintype "passive"))
      (node (ref "L16") (pin "2") (pinfunction "K_2") (pintype "passive"))
      (node (ref "L160") (pin "2") (pinfunction "K_2") (pintype "passive"))
      (node (ref "L161") (pin "2") (pinfunction "K_2") (pintype "passive"))
      (node (ref "L162") (pin "2") (pinfunction "K_2") (pintype "passive"))
      (node (ref "L163") (pin "2") (pinfunction "K_2") (pintype "passive"))
      (node (ref "L164") (pin "2") (pinfunction "K_2") (pintype "passive"))
      (node (ref "L165") (pin "2") (pinfunction "K_2") (pintype "passive"))
      (node (ref "L166") (pin "2") (pinfunction "K_2") (pintype "passive"))
      (node (ref "L167") (pin "2") (pinfunction "K_2") (pintype "passive"))
      (node (ref "L168") (pin "2") (pinfunction "K_2") (pintype "passive"))
      (node (ref "L17") (pin "2") (pinfunction "K_2") (pintype "passive"))
      (node (ref "L171") (pin "2") (pinfunction "K_2") (pintype "passive"))
      (node (ref "L172") (pin "2") (pinfunction "K_2") (pintype "passive"))
      (node (ref "L173") (pin "2") (pinfunction "K_2") (pintype "passive"))
      (node (ref "L175") (pin "2") (pinfunction "K_2") (pintype "passive"))
      (node (ref "L176") (pin "2") (pinfunction "K_2") (pintype "passive"))
      (node (ref "L177") (pin "2") (pinfunction "K_2") (pintype "passive"))
      (node (ref "L178") (pin "2") (pinfunction "K_2") (pintype "passive"))
      (node (ref "L179") (pin "2") (pinfunction "K_2") (pintype "passive"))
      (node (ref "L18") (pin "2") (pinfunction "K_2") (pintype "passive"))
      (node (ref "L180") (pin "2") (pinfunction "K_2") (pintype "passive"))
      (node (ref "L181") (pin "2") (pinfunction "K_2") (pintype "passive"))
      (node (ref "L182") (pin "2") (pinfunction "K_2") (pintype "passive"))
      (node (ref "L183") (pin "2") (pinfunction "K_2") (pintype "passive"))
      (node (ref "L184") (pin "2") (pinfunction "K_2") (pintype "passive"))
      (node (ref "L185") (pin "2") (pinfunction "K_2") (pintype "passive"))
      (node (ref "L186") (pin "2") (pinfunction "K_2") (pintype "passive"))
      (node (ref "L187") (pin "2") (pinfunction "K_2") (pintype "passive"))
      (node (ref "L188") (pin "2") (pinfunction "K_2") (pintype "passive"))
      (node (ref "L189") (pin "2") (pinfunction "K_2") (pintype "passive"))
      (node (ref "L19") (pin "2") (pinfunction "K_2") (pintype "passive"))
      (node (ref "L190") (pin "2") (pinfunction "K_2") (pintype "passive"))
      (node (ref "L191") (pin "2") (pinfunction "K_2") (pintype "passive"))
      (node (ref "L192") (pin "2") (pinfunction "K_2") (pintype "passive"))
      (node (ref "L193") (pin "2") (pinfunction "K_2") (pintype "passive"))
      (node (ref "L194") (pin "2") (pinfunction "K_2") (pintype "passive"))
      (node (ref "L195") (pin "2") (pinfunction "K_2") (pintype "passive"))
      (node (ref "L196") (pin "2") (pinfunction "K_2") (pintype "passive"))
      (node (ref "L197") (pin "2") (pinfunction "K_2") (pintype "passive"))
      (node (ref "L198") (pin "2") (pinfunction "K_2") (pintype "passive"))
      (node (ref "L199") (pin "2") (pinfunction "K_2") (pintype "passive"))
      (node (ref "L2") (pin "2") (pinfunction "K_2") (pintype "passive"))
      (node (ref "L20") (pin "2") (pinfunction "K_2") (pintype "passive"))
      (node (ref "L200") (pin "2") (pinfunction "K_2") (pintype "passive"))
      (node (ref "L201") (pin "2") (pinfunction "K_2") (pintype "passive"))
      (node (ref "L202") (pin "2") (pinfunction "K_2") (pintype "passive"))
      (node (ref "L203") (pin "2") (pinfunction "K_2") (pintype "passive"))
      (node (ref "L204") (pin "2") (pinfunction "K_2") (pintype "passive"))
      (node (ref "L205") (pin "2") (pinfunction "K_2") (pintype "passive"))
      (node (ref "L206") (pin "2") (pinfunction "K_2") (pintype "passive"))
      (node (ref "L207") (pin "2") (pinfunction "K_2") (pintype "passive"))
      (node (ref "L208") (pin "2") (pinfunction "K_2") (pintype "passive"))
      (node (ref "L209") (pin "2") (pinfunction "K_2") (pintype "passive"))
      (node (ref "L21") (pin "2") (pinfunction "K_2") (pintype "passive"))
      (node (ref "L210") (pin "2") (pinfunction "K_2") (pintype "passive"))
      (node (ref "L211") (pin "2") (pinfunction "K_2") (pintype "passive"))
      (node (ref "L212") (pin "2") (pinfunction "K_2") (pintype "passive"))
      (node (ref "L213") (pin "2") (pinfunction "K_2") (pintype "passive"))
      (node (ref "L214") (pin "2") (pinfunction "K_2") (pintype "passive"))
      (node (ref "L215") (pin "2") (pinfunction "K_2") (pintype "passive"))
      (node (ref "L216") (pin "2") (pinfunction "K_2") (pintype "passive"))
      (node (ref "L217") (pin "2") (pinfunction "K_2") (pintype "passive"))
      (node (ref "L218") (pin "2") (pinfunction "K_2") (pintype "passive"))
      (node (ref "L219") (pin "2") (pinfunction "K_2") (pintype "passive"))
      (node (ref "L22") (pin "2") (pinfunction "K_2") (pintype "passive"))
      (node (ref "L220") (pin "2") (pinfunction "K_2") (pintype "passive"))
      (node (ref "L221") (pin "2") (pinfunction "K_2") (pintype "passive"))
      (node (ref "L222") (pin "2") (pinfunction "K_2") (pintype "passive"))
      (node (ref "L223") (pin "2") (pinfunction "K_2") (pintype "passive"))
      (node (ref "L224") (pin "2") (pinfunction "K_2") (pintype "passive"))
      (node (ref "L225") (pin "2") (pinfunction "K_2") (pintype "passive"))
      (node (ref "L226") (pin "2") (pinfunction "K_2") (pintype "passive"))
      (node (ref "L227") (pin "2") (pinfunction "K_2") (pintype "passive"))
      (node (ref "L228") (pin "2") (pinfunction "K_2") (pintype "passive"))
      (node (ref "L229") (pin "2") (pinfunction "K_2") (pintype "passive"))
      (node (ref "L23") (pin "2") (pinfunction "K_2") (pintype "passive"))
      (node (ref "L230") (pin "2") (pinfunction "K_2") (pintype "passive"))
      (node (ref "L231") (pin "2") (pinfunction "K_2") (pintype "passive"))
      (node (ref "L232") (pin "2") (pinfunction "K_2") (pintype "passive"))
      (node (ref "L233") (pin "2") (pinfunction "K_2") (pintype "passive"))
      (node (ref "L234") (pin "2") (pinfunction "K_2") (pintype "passive"))
      (node (ref "L235") (pin "2") (pinfunction "K_2") (pintype "passive"))
      (node (ref "L236") (pin "2") (pinfunction "K_2") (pintype "passive"))
      (node (ref "L237") (pin "2") (pinfunction "K_2") (pintype "passive"))
      (node (ref "L238") (pin "2") (pinfunction "K_2") (pintype "passive"))
      (node (ref "L239") (pin "2") (pinfunction "K_2") (pintype "passive"))
      (node (ref "L24") (pin "2") (pinfunction "K_2") (pintype "passive"))
      (node (ref "L240") (pin "2") (pinfunction "K_2") (pintype "passive"))
      (node (ref "L241") (pin "2") (pinfunction "K_2") (pintype "passive"))
      (node (ref "L242") (pin "2") (pinfunction "K_2") (pintype "passive"))
      (node (ref "L243") (pin "2") (pinfunction "K_2") (pintype "passive"))
      (node (ref "L244") (pin "2") (pinfunction "K_2") (pintype "passive"))
      (node (ref "L245") (pin "2") (pinfunction "K_2") (pintype "passive"))
      (node (ref "L246") (pin "2") (pinfunction "K_2") (pintype "passive"))
      (node (ref "L247") (pin "2") (pinfunction "K_2") (pintype "passive"))
      (node (ref "L248") (pin "2") (pinfunction "K_2") (pintype "passive"))
      (node (ref "L249") (pin "2") (pinfunction "K_2") (pintype "passive"))
      (node (ref "L25") (pin "2") (pinfunction "K_2") (pintype "passive"))
      (node (ref "L250") (pin "2") (pinfunction "K_2") (pintype "passive"))
      (node (ref "L251") (pin "2") (pinfunction "K_2") (pintype "passive"))
      (node (ref "L252") (pin "2") (pinfunction "K_2") (pintype "passive"))
      (node (ref "L253") (pin "2") (pinfunction "K_2") (pintype "passive"))
      (node (ref "L254") (pin "2") (pinfunction "K_2") (pintype "passive"))
      (node (ref "L255") (pin "2") (pinfunction "K_2") (pintype "passive"))
      (node (ref "L256") (pin "2") (pinfunction "K_2") (pintype "passive"))
      (node (ref "L257") (pin "2") (pinfunction "K_2") (pintype "passive"))
      (node (ref "L258") (pin "2") (pinfunction "K_2") (pintype "passive"))
      (node (ref "L259") (pin "2") (pinfunction "K_2") (pintype "passive"))
      (node (ref "L26") (pin "2") (pinfunction "K_2") (pintype "passive"))
      (node (ref "L260") (pin "2") (pinfunction "K_2") (pintype "passive"))
      (node (ref "L261") (pin "2") (pinfunction "K_2") (pintype "passive"))
      (node (ref "L262") (pin "2") (pinfunction "K_2") (pintype "passive"))
      (node (ref "L263") (pin "2") (pinfunction "K_2") (pintype "passive"))
      (node (ref "L264") (pin "2") (pinfunction "K_2") (pintype "passive"))
      (node (ref "L265") (pin "2") (pinfunction "K_2") (pintype "passive"))
      (node (ref "L266") (pin "2") (pinfunction "K_2") (pintype "passive"))
      (node (ref "L267") (pin "2") (pinfunction "K_2") (pintype "passive"))
      (node (ref "L268") (pin "2") (pinfunction "K_2") (pintype "passive"))
      (node (ref "L269") (pin "2") (pinfunction "K_2") (pintype "passive"))
      (node (ref "L27") (pin "2") (pinfunction "K_2") (pintype "passive"))
      (node (ref "L270") (pin "2") (pinfunction "K_2") (pintype "passive"))
      (node (ref "L271") (pin "2") (pinfunction "K_2") (pintype "passive"))
      (node (ref "L272") (pin "2") (pinfunction "K_2") (pintype "passive"))
      (node (ref "L273") (pin "2") (pinfunction "K_2") (pintype "passive"))
      (node (ref "L274") (pin "2") (pinfunction "K_2") (pintype "passive"))
      (node (ref "L275") (pin "2") (pinfunction "K_2") (pintype "passive"))
      (node (ref "L276") (pin "2") (pinfunction "K_2") (pintype "passive"))
      (node (ref "L277") (pin "2") (pinfunction "K_2") (pintype "passive"))
      (node (ref "L278") (pin "2") (pinfunction "K_2") (pintype "passive"))
      (node (ref "L279") (pin "2") (pinfunction "K_2") (pintype "passive"))
      (node (ref "L28") (pin "2") (pinfunction "K_2") (pintype "passive"))
      (node (ref "L280") (pin "2") (pinfunction "K_2") (pintype "passive"))
      (node (ref "L281") (pin "2") (pinfunction "K_2") (pintype "passive"))
      (node (ref "L282") (pin "2") (pinfunction "K_2") (pintype "passive"))
      (node (ref "L283") (pin "2") (pinfunction "K_2") (pintype "passive"))
      (node (ref "L284") (pin "2") (pinfunction "K_2") (pintype "passive"))
      (node (ref "L285") (pin "2") (pinfunction "K_2") (pintype "passive"))
      (node (ref "L286") (pin "2") (pinfunction "K_2") (pintype "passive"))
      (node (ref "L287") (pin "2") (pinfunction "K_2") (pintype "passive"))
      (node (ref "L288") (pin "2") (pinfunction "K_2") (pintype "passive"))
      (node (ref "L289") (pin "2") (pinfunction "K_2") (pintype "passive"))
      (node (ref "L29") (pin "2") (pinfunction "K_2") (pintype "passive"))
      (node (ref "L290") (pin "2") (pinfunction "K_2") (pintype "passive"))
      (node (ref "L291") (pin "2") (pinfunction "K_2") (pintype "passive"))
      (node (ref "L292") (pin "2") (pinfunction "K_2") (pintype "passive"))
      (node (ref "L293") (pin "2") (pinfunction "K_2") (pintype "passive"))
      (node (ref "L294") (pin "2") (pinfunction "K_2") (pintype "passive"))
      (node (ref "L295") (pin "2") (pinfunction "K_2") (pintype "passive"))
      (node (ref "L296") (pin "2") (pinfunction "K_2") (pintype "passive"))
      (node (ref "L297") (pin "2") (pinfunction "K_2") (pintype "passive"))
      (node (ref "L298") (pin "2") (pinfunction "K_2") (pintype "passive"))
      (node (ref "L299") (pin "2") (pinfunction "K_2") (pintype "passive"))
      (node (ref "L3") (pin "2") (pinfunction "K_2") (pintype "passive"))
      (node (ref "L30") (pin "2") (pinfunction "K_2") (pintype "passive"))
      (node (ref "L300") (pin "2") (pinfunction "K_2") (pintype "passive"))
      (node (ref "L301") (pin "2") (pinfunction "K_2") (pintype "passive"))
      (node (ref "L302") (pin "2") (pinfunction "K_2") (pintype "passive"))
      (node (ref "L303") (pin "2") (pinfunction "K_2") (pintype "passive"))
      (node (ref "L304") (pin "2") (pinfunction "K_2") (pintype "passive"))
      (node (ref "L305") (pin "2") (pinfunction "K_2") (pintype "passive"))
      (node (ref "L306") (pin "2") (pinfunction "K_2") (pintype "passive"))
      (node (ref "L307") (pin "2") (pinfunction "K_2") (pintype "passive"))
      (node (ref "L308") (pin "2") (pinfunction "K_2") (pintype "passive"))
      (node (ref "L309") (pin "2") (pinfunction "K_2") (pintype "passive"))
      (node (ref "L31") (pin "2") (pinfunction "K_2") (pintype "passive"))
      (node (ref "L310") (pin "2") (pinfunction "K_2") (pintype "passive"))
      (node (ref "L311") (pin "2") (pinfunction "K_2") (pintype "passive"))
      (node (ref "L312") (pin "2") (pinfunction "K_2") (pintype "passive"))
      (node (ref "L313") (pin "2") (pinfunction "K_2") (pintype "passive"))
      (node (ref "L314") (pin "2") (pinfunction "K_2") (pintype "passive"))
      (node (ref "L315") (pin "2") (pinfunction "K_2") (pintype "passive"))
      (node (ref "L316") (pin "2") (pinfunction "K_2") (pintype "passive"))
      (node (ref "L317") (pin "2") (pinfunction "K_2") (pintype "passive"))
      (node (ref "L318") (pin "2") (pinfunction "K_2") (pintype "passive"))
      (node (ref "L319") (pin "2") (pinfunction "K_2") (pintype "passive"))
      (node (ref "L32") (pin "2") (pinfunction "K_2") (pintype "passive"))
      (node (ref "L320") (pin "2") (pinfunction "K_2") (pintype "passive"))
      (node (ref "L321") (pin "2") (pinfunction "K_2") (pintype "passive"))
      (node (ref "L322") (pin "2") (pinfunction "K_2") (pintype "passive"))
      (node (ref "L323") (pin "2") (pinfunction "K_2") (pintype "passive"))
      (node (ref "L324") (pin "2") (pinfunction "K_2") (pintype "passive"))
      (node (ref "L325") (pin "2") (pinfunction "K_2") (pintype "passive"))
      (node (ref "L326") (pin "2") (pinfunction "K_2") (pintype "passive"))
      (node (ref "L327") (pin "2") (pinfunction "K_2") (pintype "passive"))
      (node (ref "L328") (pin "2") (pinfunction "K_2") (pintype "passive"))
      (node (ref "L329") (pin "2") (pinfunction "K_2") (pintype "passive"))
      (node (ref "L33") (pin "2") (pinfunction "K_2") (pintype "passive"))
      (node (ref "L330") (pin "2") (pinfunction "K_2") (pintype "passive"))
      (node (ref "L331") (pin "2") (pinfunction "K_2") (pintype "passive"))
      (node (ref "L332") (pin "2") (pinfunction "K_2") (pintype "passive"))
      (node (ref "L333") (pin "2") (pinfunction "K_2") (pintype "passive"))
      (node (ref "L334") (pin "2") (pinfunction "K_2") (pintype "passive"))
      (node (ref "L335") (pin "2") (pinfunction "K_2") (pintype "passive"))
      (node (ref "L336") (pin "2") (pinfunction "K_2") (pintype "passive"))
      (node (ref "L337") (pin "2") (pinfunction "K_2") (pintype "passive"))
      (node (ref "L338") (pin "2") (pinfunction "K_2") (pintype "passive"))
      (node (ref "L339") (pin "2") (pinfunction "K_2") (pintype "passive"))
      (node (ref "L34") (pin "2") (pinfunction "K_2") (pintype "passive"))
      (node (ref "L340") (pin "2") (pinfunction "K_2") (pintype "passive"))
      (node (ref "L341") (pin "2") (pinfunction "K_2") (pintype "passive"))
      (node (ref "L342") (pin "2") (pinfunction "K_2") (pintype "passive"))
      (node (ref "L343") (pin "2") (pinfunction "K_2") (pintype "passive"))
      (node (ref "L344") (pin "2") (pinfunction "K_2") (pintype "passive"))
      (node (ref "L345") (pin "2") (pinfunction "K_2") (pintype "passive"))
      (node (ref "L346") (pin "2") (pinfunction "K_2") (pintype "passive"))
      (node (ref "L347") (pin "2") (pinfunction "K_2") (pintype "passive"))
      (node (ref "L348") (pin "2") (pinfunction "K_2") (pintype "passive"))
      (node (ref "L349") (pin "2") (pinfunction "K_2") (pintype "passive"))
      (node (ref "L35") (pin "2") (pinfunction "K_2") (pintype "passive"))
      (node (ref "L350") (pin "2") (pinfunction "K_2") (pintype "passive"))
      (node (ref "L351") (pin "2") (pinfunction "K_2") (pintype "passive"))
      (node (ref "L352") (pin "2") (pinfunction "K_2") (pintype "passive"))
      (node (ref "L353") (pin "2") (pinfunction "K_2") (pintype "passive"))
      (node (ref "L354") (pin "2") (pinfunction "K_2") (pintype "passive"))
      (node (ref "L355") (pin "2") (pinfunction "K_2") (pintype "passive"))
      (node (ref "L356") (pin "2") (pinfunction "K_2") (pintype "passive"))
      (node (ref "L357") (pin "2") (pinfunction "K_2") (pintype "passive"))
      (node (ref "L36") (pin "2") (pinfunction "K_2") (pintype "passive"))
      (node (ref "L361") (pin "2") (pinfunction "K_2") (pintype "passive"))
      (node (ref "L362") (pin "2") (pinfunction "K_2") (pintype "passive"))
      (node (ref "L363") (pin "2") (pinfunction "K_2") (pintype "passive"))
      (node (ref "L364") (pin "2") (pinfunction "K_2") (pintype "passive"))
      (node (ref "L365") (pin "2") (pinfunction "K_2") (pintype "passive"))
      (node (ref "L366") (pin "2") (pinfunction "K_2") (pintype "passive"))
      (node (ref "L367") (pin "2") (pinfunction "K_2") (pintype "passive"))
      (node (ref "L368") (pin "2") (pinfunction "K_2") (pintype "passive"))
      (node (ref "L369") (pin "2") (pinfunction "K_2") (pintype "passive"))
      (node (ref "L37") (pin "2") (pinfunction "K_2") (pintype "passive"))
      (node (ref "L370") (pin "2") (pinfunction "K_2") (pintype "passive"))
      (node (ref "L371") (pin "2") (pinfunction "K_2") (pintype "passive"))
      (node (ref "L372") (pin "2") (pinfunction "K_2") (pintype "passive"))
      (node (ref "L375") (pin "2") (pinfunction "K_2") (pintype "passive"))
      (node (ref "L376") (pin "2") (pinfunction "K_2") (pintype "passive"))
      (node (ref "L377") (pin "2") (pinfunction "K_2") (pintype "passive"))
      (node (ref "L378") (pin "2") (pinfunction "K_2") (pintype "passive"))
      (node (ref "L379") (pin "2") (pinfunction "K_2") (pintype "passive"))
      (node (ref "L38") (pin "2") (pinfunction "K_2") (pintype "passive"))
      (node (ref "L380") (pin "2") (pinfunction "K_2") (pintype "passive"))
      (node (ref "L381") (pin "2") (pinfunction "K_2") (pintype "passive"))
      (node (ref "L382") (pin "2") (pinfunction "K_2") (pintype "passive"))
      (node (ref "L383") (pin "2") (pinfunction "K_2") (pintype "passive"))
      (node (ref "L384") (pin "2") (pinfunction "K_2") (pintype "passive"))
      (node (ref "L387") (pin "2") (pinfunction "K_2") (pintype "passive"))
      (node (ref "L388") (pin "2") (pinfunction "K_2") (pintype "passive"))
      (node (ref "L389") (pin "2") (pinfunction "K_2") (pintype "passive"))
      (node (ref "L39") (pin "2") (pinfunction "K_2") (pintype "passive"))
      (node (ref "L390") (pin "2") (pinfunction "K_2") (pintype "passive"))
      (node (ref "L391") (pin "2") (pinfunction "K_2") (pintype "passive"))
      (node (ref "L392") (pin "2") (pinfunction "K_2") (pintype "passive"))
      (node (ref "L393") (pin "2") (pinfunction "K_2") (pintype "passive"))
      (node (ref "L394") (pin "2") (pinfunction "K_2") (pintype "passive"))
      (node (ref "L395") (pin "2") (pinfunction "K_2") (pintype "passive"))
      (node (ref "L396") (pin "2") (pinfunction "K_2") (pintype "passive"))
      (node (ref "L397") (pin "2") (pinfunction "K_2") (pintype "passive"))
      (node (ref "L398") (pin "2") (pinfunction "K_2") (pintype "passive"))
      (node (ref "L399") (pin "2") (pinfunction "K_2") (pintype "passive"))
      (node (ref "L4") (pin "2") (pinfunction "K_2") (pintype "passive"))
      (node (ref "L40") (pin "2") (pinfunction "K_2") (pintype "passive"))
      (node (ref "L403") (pin "2") (pinfunction "K_2") (pintype "passive"))
      (node (ref "L404") (pin "2") (pinfunction "K_2") (pintype "passive"))
      (node (ref "L405") (pin "2") (pinfunction "K_2") (pintype "passive"))
      (node (ref "L406") (pin "2") (pinfunction "K_2") (pintype "passive"))
      (node (ref "L407") (pin "2") (pinfunction "K_2") (pintype "passive"))
      (node (ref "L408") (pin "2") (pinfunction "K_2") (pintype "passive"))
      (node (ref "L409") (pin "2") (pinfunction "K_2") (pintype "passive"))
      (node (ref "L41") (pin "2") (pinfunction "K_2") (pintype "passive"))
      (node (ref "L410") (pin "2") (pinfunction "K_2") (pintype "passive"))
      (node (ref "L411") (pin "2") (pinfunction "K_2") (pintype "passive"))
      (node (ref "L412") (pin "2") (pinfunction "K_2") (pintype "passive"))
      (node (ref "L413") (pin "2") (pinfunction "K_2") (pintype "passive"))
      (node (ref "L414") (pin "2") (pinfunction "K_2") (pintype "passive"))
      (node (ref "L417") (pin "2") (pinfunction "K_2") (pintype "passive"))
      (node (ref "L418") (pin "2") (pinfunction "K_2") (pintype "passive"))
      (node (ref "L419") (pin "2") (pinfunction "K_2") (pintype "passive"))
      (node (ref "L42") (pin "2") (pinfunction "K_2") (pintype "passive"))
      (node (ref "L420") (pin "2") (pinfunction "K_2") (pintype "passive"))
      (node (ref "L421") (pin "2") (pinfunction "K_2") (pintype "passive"))
      (node (ref "L422") (pin "2") (pinfunction "K_2") (pintype "passive"))
      (node (ref "L423") (pin "2") (pinfunction "K_2") (pintype "passive"))
      (node (ref "L424") (pin "2") (pinfunction "K_2") (pintype "passive"))
      (node (ref "L425") (pin "2") (pinfunction "K_2") (pintype "passive"))
      (node (ref "L426") (pin "2") (pinfunction "K_2") (pintype "passive"))
      (node (ref "L427") (pin "2") (pinfunction "K_2") (pintype "passive"))
      (node (ref "L428") (pin "2") (pinfunction "K_2") (pintype "passive"))
      (node (ref "L429") (pin "2") (pinfunction "K_2") (pintype "passive"))
      (node (ref "L43") (pin "2") (pinfunction "K_2") (pintype "passive"))
      (node (ref "L430") (pin "2") (pinfunction "K_2") (pintype "passive"))
      (node (ref "L431") (pin "2") (pinfunction "K_2") (pintype "passive"))
      (node (ref "L432") (pin "2") (pinfunction "K_2") (pintype "passive"))
      (node (ref "L433") (pin "2") (pinfunction "K_2") (pintype "passive"))
      (node (ref "L434") (pin "2") (pinfunction "K_2") (pintype "passive"))
      (node (ref "L435") (pin "2") (pinfunction "K_2") (pintype "passive"))
      (node (ref "L436") (pin "2") (pinfunction "K_2") (pintype "passive"))
      (node (ref "L437") (pin "2") (pinfunction "K_2") (pintype "passive"))
      (node (ref "L438") (pin "2") (pinfunction "K_2") (pintype "passive"))
      (node (ref "L439") (pin "2") (pinfunction "K_2") (pintype "passive"))
      (node (ref "L44") (pin "2") (pinfunction "K_2") (pintype "passive"))
      (node (ref "L440") (pin "2") (pinfunction "K_2") (pintype "passive"))
      (node (ref "L441") (pin "2") (pinfunction "K_2") (pintype "passive"))
      (node (ref "L442") (pin "2") (pinfunction "K_2") (pintype "passive"))
      (node (ref "L443") (pin "2") (pinfunction "K_2") (pintype "passive"))
      (node (ref "L444") (pin "2") (pinfunction "K_2") (pintype "passive"))
      (node (ref "L445") (pin "2") (pinfunction "K_2") (pintype "passive"))
      (node (ref "L446") (pin "2") (pinfunction "K_2") (pintype "passive"))
      (node (ref "L447") (pin "2") (pinfunction "K_2") (pintype "passive"))
      (node (ref "L448") (pin "2") (pinfunction "K_2") (pintype "passive"))
      (node (ref "L449") (pin "2") (pinfunction "K_2") (pintype "passive"))
      (node (ref "L45") (pin "2") (pinfunction "K_2") (pintype "passive"))
      (node (ref "L450") (pin "2") (pinfunction "K_2") (pintype "passive"))
      (node (ref "L451") (pin "2") (pinfunction "K_2") (pintype "passive"))
      (node (ref "L452") (pin "2") (pinfunction "K_2") (pintype "passive"))
      (node (ref "L453") (pin "2") (pinfunction "K_2") (pintype "passive"))
      (node (ref "L454") (pin "2") (pinfunction "K_2") (pintype "passive"))
      (node (ref "L455") (pin "2") (pinfunction "K_2") (pintype "passive"))
      (node (ref "L456") (pin "2") (pinfunction "K_2") (pintype "passive"))
      (node (ref "L457") (pin "2") (pinfunction "K_2") (pintype "passive"))
      (node (ref "L458") (pin "2") (pinfunction "K_2") (pintype "passive"))
      (node (ref "L459") (pin "2") (pinfunction "K_2") (pintype "passive"))
      (node (ref "L46") (pin "2") (pinfunction "K_2") (pintype "passive"))
      (node (ref "L460") (pin "2") (pinfunction "K_2") (pintype "passive"))
      (node (ref "L461") (pin "2") (pinfunction "K_2") (pintype "passive"))
      (node (ref "L462") (pin "2") (pinfunction "K_2") (pintype "passive"))
      (node (ref "L463") (pin "2") (pinfunction "K_2") (pintype "passive"))
      (node (ref "L464") (pin "2") (pinfunction "K_2") (pintype "passive"))
      (node (ref "L465") (pin "2") (pinfunction "K_2") (pintype "passive"))
      (node (ref "L466") (pin "2") (pinfunction "K_2") (pintype "passive"))
      (node (ref "L467") (pin "2") (pinfunction "K_2") (pintype "passive"))
      (node (ref "L468") (pin "2") (pinfunction "K_2") (pintype "passive"))
      (node (ref "L469") (pin "2") (pinfunction "K_2") (pintype "passive"))
      (node (ref "L47") (pin "2") (pinfunction "K_2") (pintype "passive"))
      (node (ref "L470") (pin "2") (pinfunction "K_2") (pintype "passive"))
      (node (ref "L471") (pin "2") (pinfunction "K_2") (pintype "passive"))
      (node (ref "L472") (pin "2") (pinfunction "K_2") (pintype "passive"))
      (node (ref "L473") (pin "2") (pinfunction "K_2") (pintype "passive"))
      (node (ref "L474") (pin "2") (pinfunction "K_2") (pintype "passive"))
      (node (ref "L475") (pin "2") (pinfunction "K_2") (pintype "passive"))
      (node (ref "L476") (pin "2") (pinfunction "K_2") (pintype "passive"))
      (node (ref "L477") (pin "2") (pinfunction "K_2") (pintype "passive"))
      (node (ref "L478") (pin "2") (pinfunction "K_2") (pintype "passive"))
      (node (ref "L479") (pin "2") (pinfunction "K_2") (pintype "passive"))
      (node (ref "L48") (pin "2") (pinfunction "K_2") (pintype "passive"))
      (node (ref "L480") (pin "2") (pinfunction "K_2") (pintype "passive"))
      (node (ref "L481") (pin "2") (pinfunction "K_2") (pintype "passive"))
      (node (ref "L482") (pin "2") (pinfunction "K_2") (pintype "passive"))
      (node (ref "L483") (pin "2") (pinfunction "K_2") (pintype "passive"))
      (node (ref "L484") (pin "2") (pinfunction "K_2") (pintype "passive"))
      (node (ref "L485") (pin "2") (pinfunction "K_2") (pintype "passive"))
      (node (ref "L486") (pin "2") (pinfunction "K_2") (pintype "passive"))
      (node (ref "L487") (pin "2") (pinfunction "K_2") (pintype "passive"))
      (node (ref "L488") (pin "2") (pinfunction "K_2") (pintype "passive"))
      (node (ref "L489") (pin "2") (pinfunction "K_2") (pintype "passive"))
      (node (ref "L49") (pin "2") (pinfunction "K_2") (pintype "passive"))
      (node (ref "L490") (pin "2") (pinfunction "K_2") (pintype "passive"))
      (node (ref "L491") (pin "2") (pinfunction "K_2") (pintype "passive"))
      (node (ref "L492") (pin "2") (pinfunction "K_2") (pintype "passive"))
      (node (ref "L493") (pin "2") (pinfunction "K_2") (pintype "passive"))
      (node (ref "L494") (pin "2") (pinfunction "K_2") (pintype "passive"))
      (node (ref "L495") (pin "2") (pinfunction "K_2") (pintype "passive"))
      (node (ref "L496") (pin "2") (pinfunction "K_2") (pintype "passive"))
      (node (ref "L497") (pin "2") (pinfunction "K_2") (pintype "passive"))
      (node (ref "L498") (pin "2") (pinfunction "K_2") (pintype "passive"))
      (node (ref "L499") (pin "2") (pinfunction "K_2") (pintype "passive"))
      (node (ref "L5") (pin "2") (pinfunction "K_2") (pintype "passive"))
      (node (ref "L50") (pin "2") (pinfunction "K_2") (pintype "passive"))
      (node (ref "L500") (pin "2") (pinfunction "K_2") (pintype "passive"))
      (node (ref "L501") (pin "2") (pinfunction "K_2") (pintype "passive"))
      (node (ref "L502") (pin "2") (pinfunction "K_2") (pintype "passive"))
      (node (ref "L503") (pin "2") (pinfunction "K_2") (pintype "passive"))
      (node (ref "L504") (pin "2") (pinfunction "K_2") (pintype "passive"))
      (node (ref "L505") (pin "2") (pinfunction "K_2") (pintype "passive"))
      (node (ref "L506") (pin "2") (pinfunction "K_2") (pintype "passive"))
      (node (ref "L507") (pin "2") (pinfunction "K_2") (pintype "passive"))
      (node (ref "L508") (pin "2") (pinfunction "K_2") (pintype "passive"))
      (node (ref "L509") (pin "2") (pinfunction "K_2") (pintype "passive"))
      (node (ref "L51") (pin "2") (pinfunction "K_2") (pintype "passive"))
      (node (ref "L510") (pin "2") (pinfunction "K_2") (pintype "passive"))
      (node (ref "L511") (pin "2") (pinfunction "K_2") (pintype "passive"))
      (node (ref "L512") (pin "2") (pinfunction "K_2") (pintype "passive"))
      (node (ref "L513") (pin "2") (pinfunction "K_2") (pintype "passive"))
      (node (ref "L514") (pin "2") (pinfunction "K_2") (pintype "passive"))
      (node (ref "L515") (pin "2") (pinfunction "K_2") (pintype "passive"))
      (node (ref "L516") (pin "2") (pinfunction "K_2") (pintype "passive"))
      (node (ref "L517") (pin "2") (pinfunction "K_2") (pintype "passive"))
      (node (ref "L518") (pin "2") (pinfunction "K_2") (pintype "passive"))
      (node (ref "L519") (pin "2") (pinfunction "K_2") (pintype "passive"))
      (node (ref "L52") (pin "2") (pinfunction "K_2") (pintype "passive"))
      (node (ref "L520") (pin "2") (pinfunction "K_2") (pintype "passive"))
      (node (ref "L521") (pin "2") (pinfunction "K_2") (pintype "passive"))
      (node (ref "L522") (pin "2") (pinfunction "K_2") (pintype "passive"))
      (node (ref "L53") (pin "2") (pinfunction "K_2") (pintype "passive"))
      (node (ref "L54") (pin "2") (pinfunction "K_2") (pintype "passive"))
      (node (ref "L55") (pin "2") (pinfunction "K_2") (pintype "passive"))
      (node (ref "L56") (pin "2") (pinfunction "K_2") (pintype "passive"))
      (node (ref "L57") (pin "2") (pinfunction "K_2") (pintype "passive"))
      (node (ref "L58") (pin "2") (pinfunction "K_2") (pintype "passive"))
      (node (ref "L59") (pin "2") (pinfunction "K_2") (pintype "passive"))
      (node (ref "L6") (pin "2") (pinfunction "K_2") (pintype "passive"))
      (node (ref "L60") (pin "2") (pinfunction "K_2") (pintype "passive"))
      (node (ref "L61") (pin "2") (pinfunction "K_2") (pintype "passive"))
      (node (ref "L62") (pin "2") (pinfunction "K_2") (pintype "passive"))
      (node (ref "L63") (pin "2") (pinfunction "K_2") (pintype "passive"))
      (node (ref "L64") (pin "2") (pinfunction "K_2") (pintype "passive"))
      (node (ref "L66") (pin "2") (pinfunction "K_2") (pintype "passive"))
      (node (ref "L67") (pin "2") (pinfunction "K_2") (pintype "passive"))
      (node (ref "L68") (pin "2") (pinfunction "K_2") (pintype "passive"))
      (node (ref "L69") (pin "2") (pinfunction "K_2") (pintype "passive"))
      (node (ref "L7") (pin "2") (pinfunction "K_2") (pintype "passive"))
      (node (ref "L70") (pin "2") (pinfunction "K_2") (pintype "passive"))
      (node (ref "L72") (pin "2") (pinfunction "K_2") (pintype "passive"))
      (node (ref "L73") (pin "2") (pinfunction "K_2") (pintype "passive"))
      (node (ref "L74") (pin "2") (pinfunction "K_2") (pintype "passive"))
      (node (ref "L75") (pin "2") (pinfunction "K_2") (pintype "passive"))
      (node (ref "L76") (pin "2") (pinfunction "K_2") (pintype "passive"))
      (node (ref "L77") (pin "2") (pinfunction "K_2") (pintype "passive"))
      (node (ref "L78") (pin "2") (pinfunction "K_2") (pintype "passive"))
      (node (ref "L79") (pin "2") (pinfunction "K_2") (pintype "passive"))
      (node (ref "L8") (pin "2") (pinfunction "K_2") (pintype "passive"))
      (node (ref "L80") (pin "2") (pinfunction "K_2") (pintype "passive"))
      (node (ref "L81") (pin "2") (pinfunction "K_2") (pintype "passive"))
      (node (ref "L82") (pin "2") (pinfunction "K_2") (pintype "passive"))
      (node (ref "L83") (pin "2") (pinfunction "K_2") (pintype "passive"))
      (node (ref "L84") (pin "2") (pinfunction "K_2") (pintype "passive"))
      (node (ref "L85") (pin "2") (pinfunction "K_2") (pintype "passive"))
      (node (ref "L86") (pin "2") (pinfunction "K_2") (pintype "passive"))
      (node (ref "L87") (pin "2") (pinfunction "K_2") (pintype "passive"))
      (node (ref "L88") (pin "2") (pinfunction "K_2") (pintype "passive"))
      (node (ref "L89") (pin "2") (pinfunction "K_2") (pintype "passive"))
      (node (ref "L9") (pin "2") (pinfunction "K_2") (pintype "passive"))
      (node (ref "L90") (pin "2") (pinfunction "K_2") (pintype "passive"))
      (node (ref "L91") (pin "2") (pinfunction "K_2") (pintype "passive"))
      (node (ref "L92") (pin "2") (pinfunction "K_2") (pintype "passive"))
      (node (ref "L93") (pin "2") (pinfunction "K_2") (pintype "passive"))
      (node (ref "L94") (pin "2") (pinfunction "K_2") (pintype "passive"))
      (node (ref "L95") (pin "2") (pinfunction "K_2") (pintype "passive"))
      (node (ref "L96") (pin "2") (pinfunction "K_2") (pintype "passive"))
      (node (ref "L97") (pin "2") (pinfunction "K_2") (pintype "passive"))
      (node (ref "L98") (pin "2") (pinfunction "K_2") (pintype "passive"))
      (node (ref "L99") (pin "2") (pinfunction "K_2") (pintype "passive"))
    )
    (net (code "27") (name "Net-(L1-A)") (class "Default")
      (node (ref "L1") (pin "1") (pinfunction "A_1") (pintype "passive"))
      (node (ref "L2") (pin "1") (pinfunction "A_1") (pintype "passive"))
      (node (ref "L3") (pin "1") (pinfunction "A_1") (pintype "passive"))
    )
    (net (code "28") (name "Net-(L169-K)") (class "Default")
      (node (ref "L169") (pin "2") (pinfunction "K_2") (pintype "passive"))
      (node (ref "L170") (pin "2") (pinfunction "K_2") (pintype "passive"))
      (node (ref "L174") (pin "2") (pinfunction "K_2") (pintype "passive"))
    )
    (net (code "29") (name "unconnected-(L65-K-Pad2)") (class "Default")
      (node (ref "L65") (pin "2") (pinfunction "K_2") (pintype "passive"))
    )
    (net (code "30") (name "unconnected-(L71-K-Pad2)") (class "Default")
      (node (ref "L71") (pin "2") (pinfunction "K_2") (pintype "passive"))
    )
  )
)
